# Full.net
KiCad netlist of a schematic drawn in EAGLE
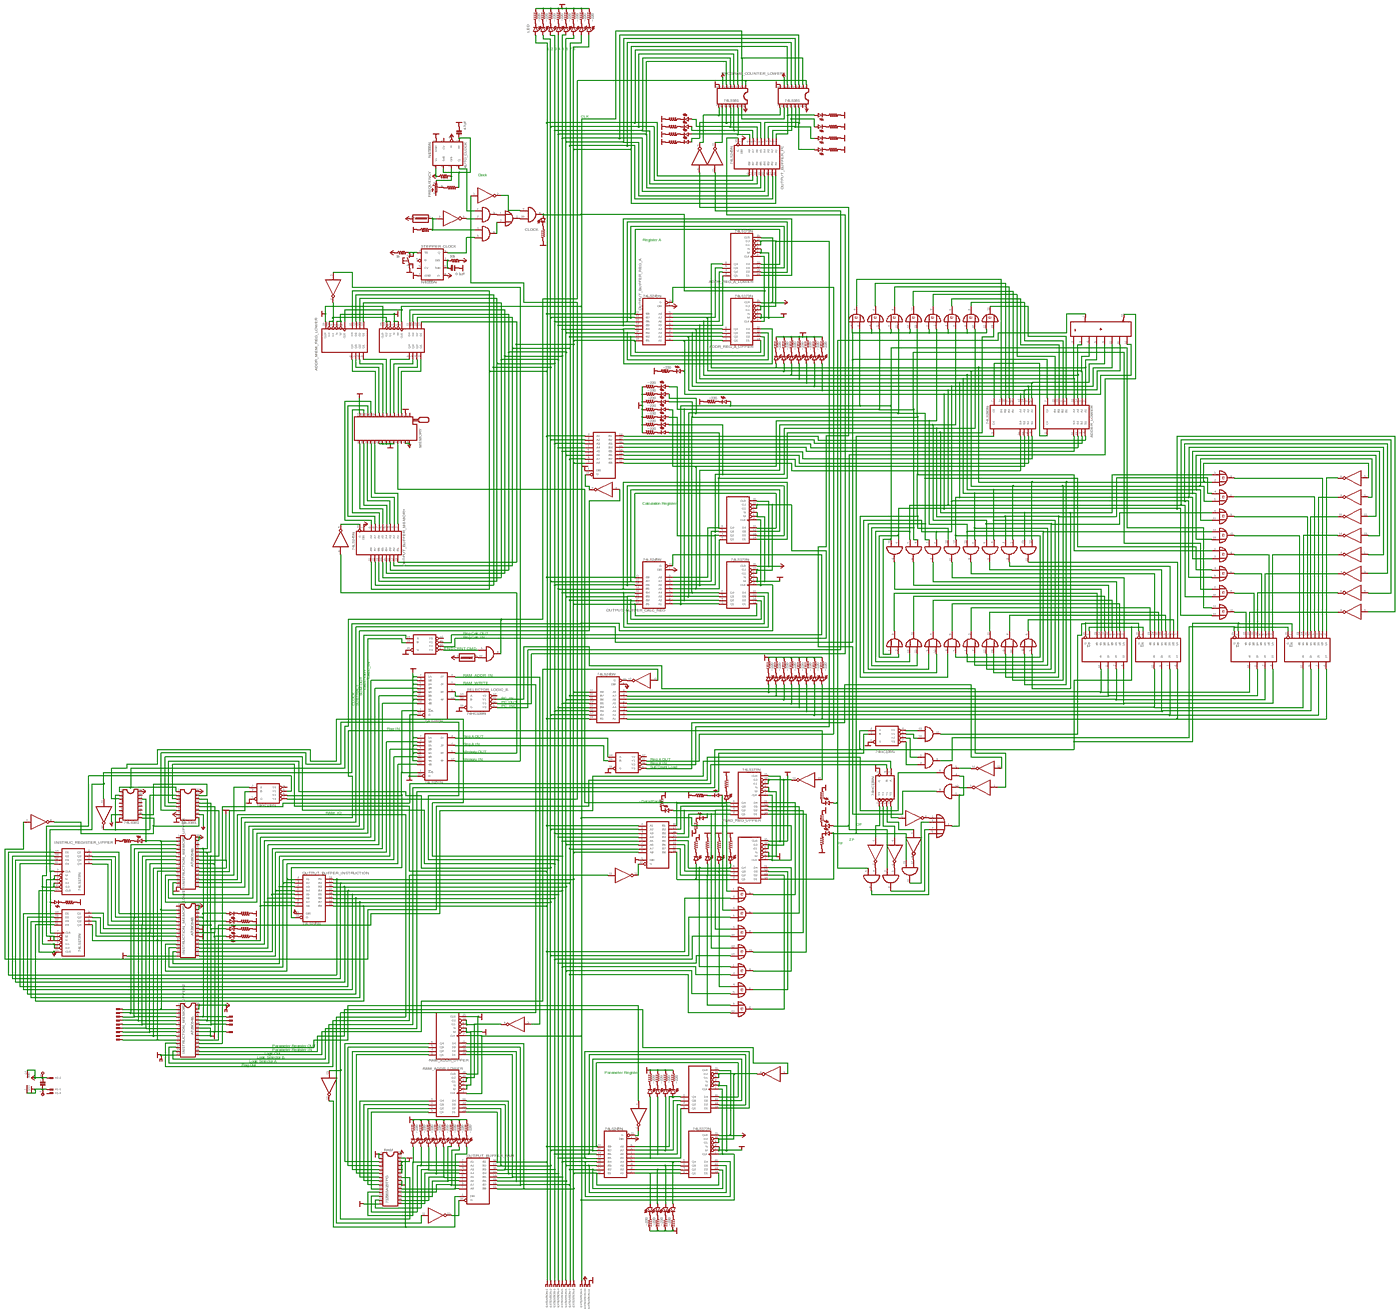
[diagram p0: schematic, sheet 1, overview]
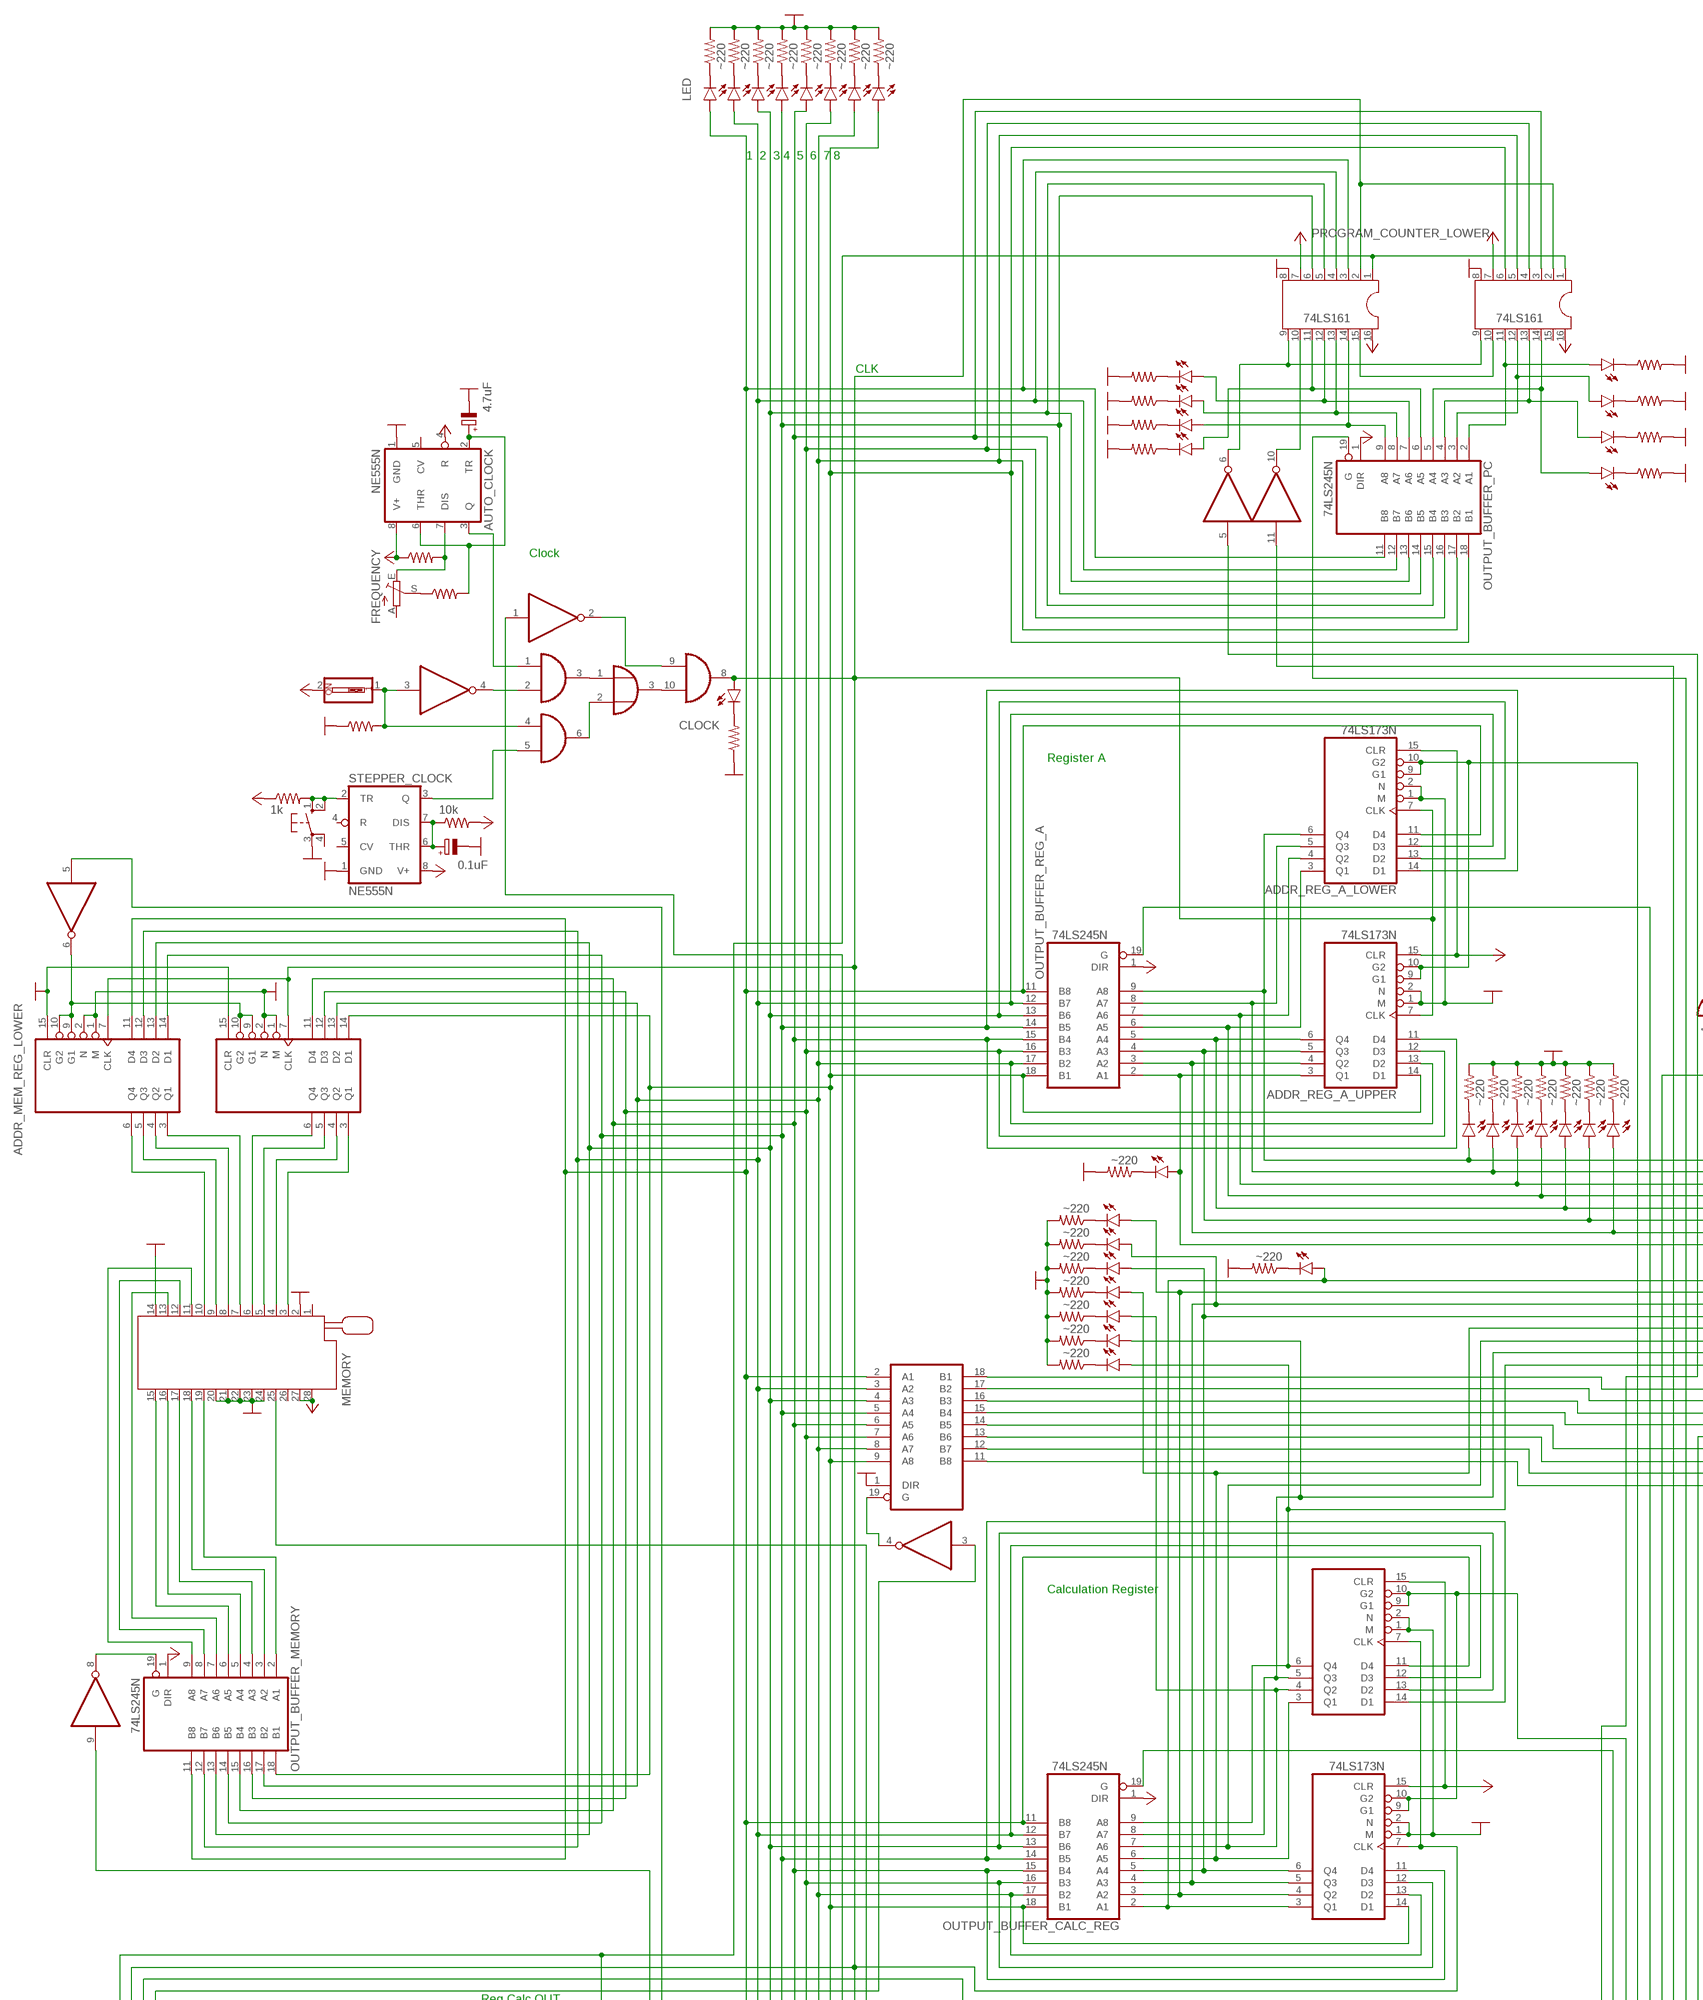
[diagram p1: schematic, sheet 1, part 1 of 4]
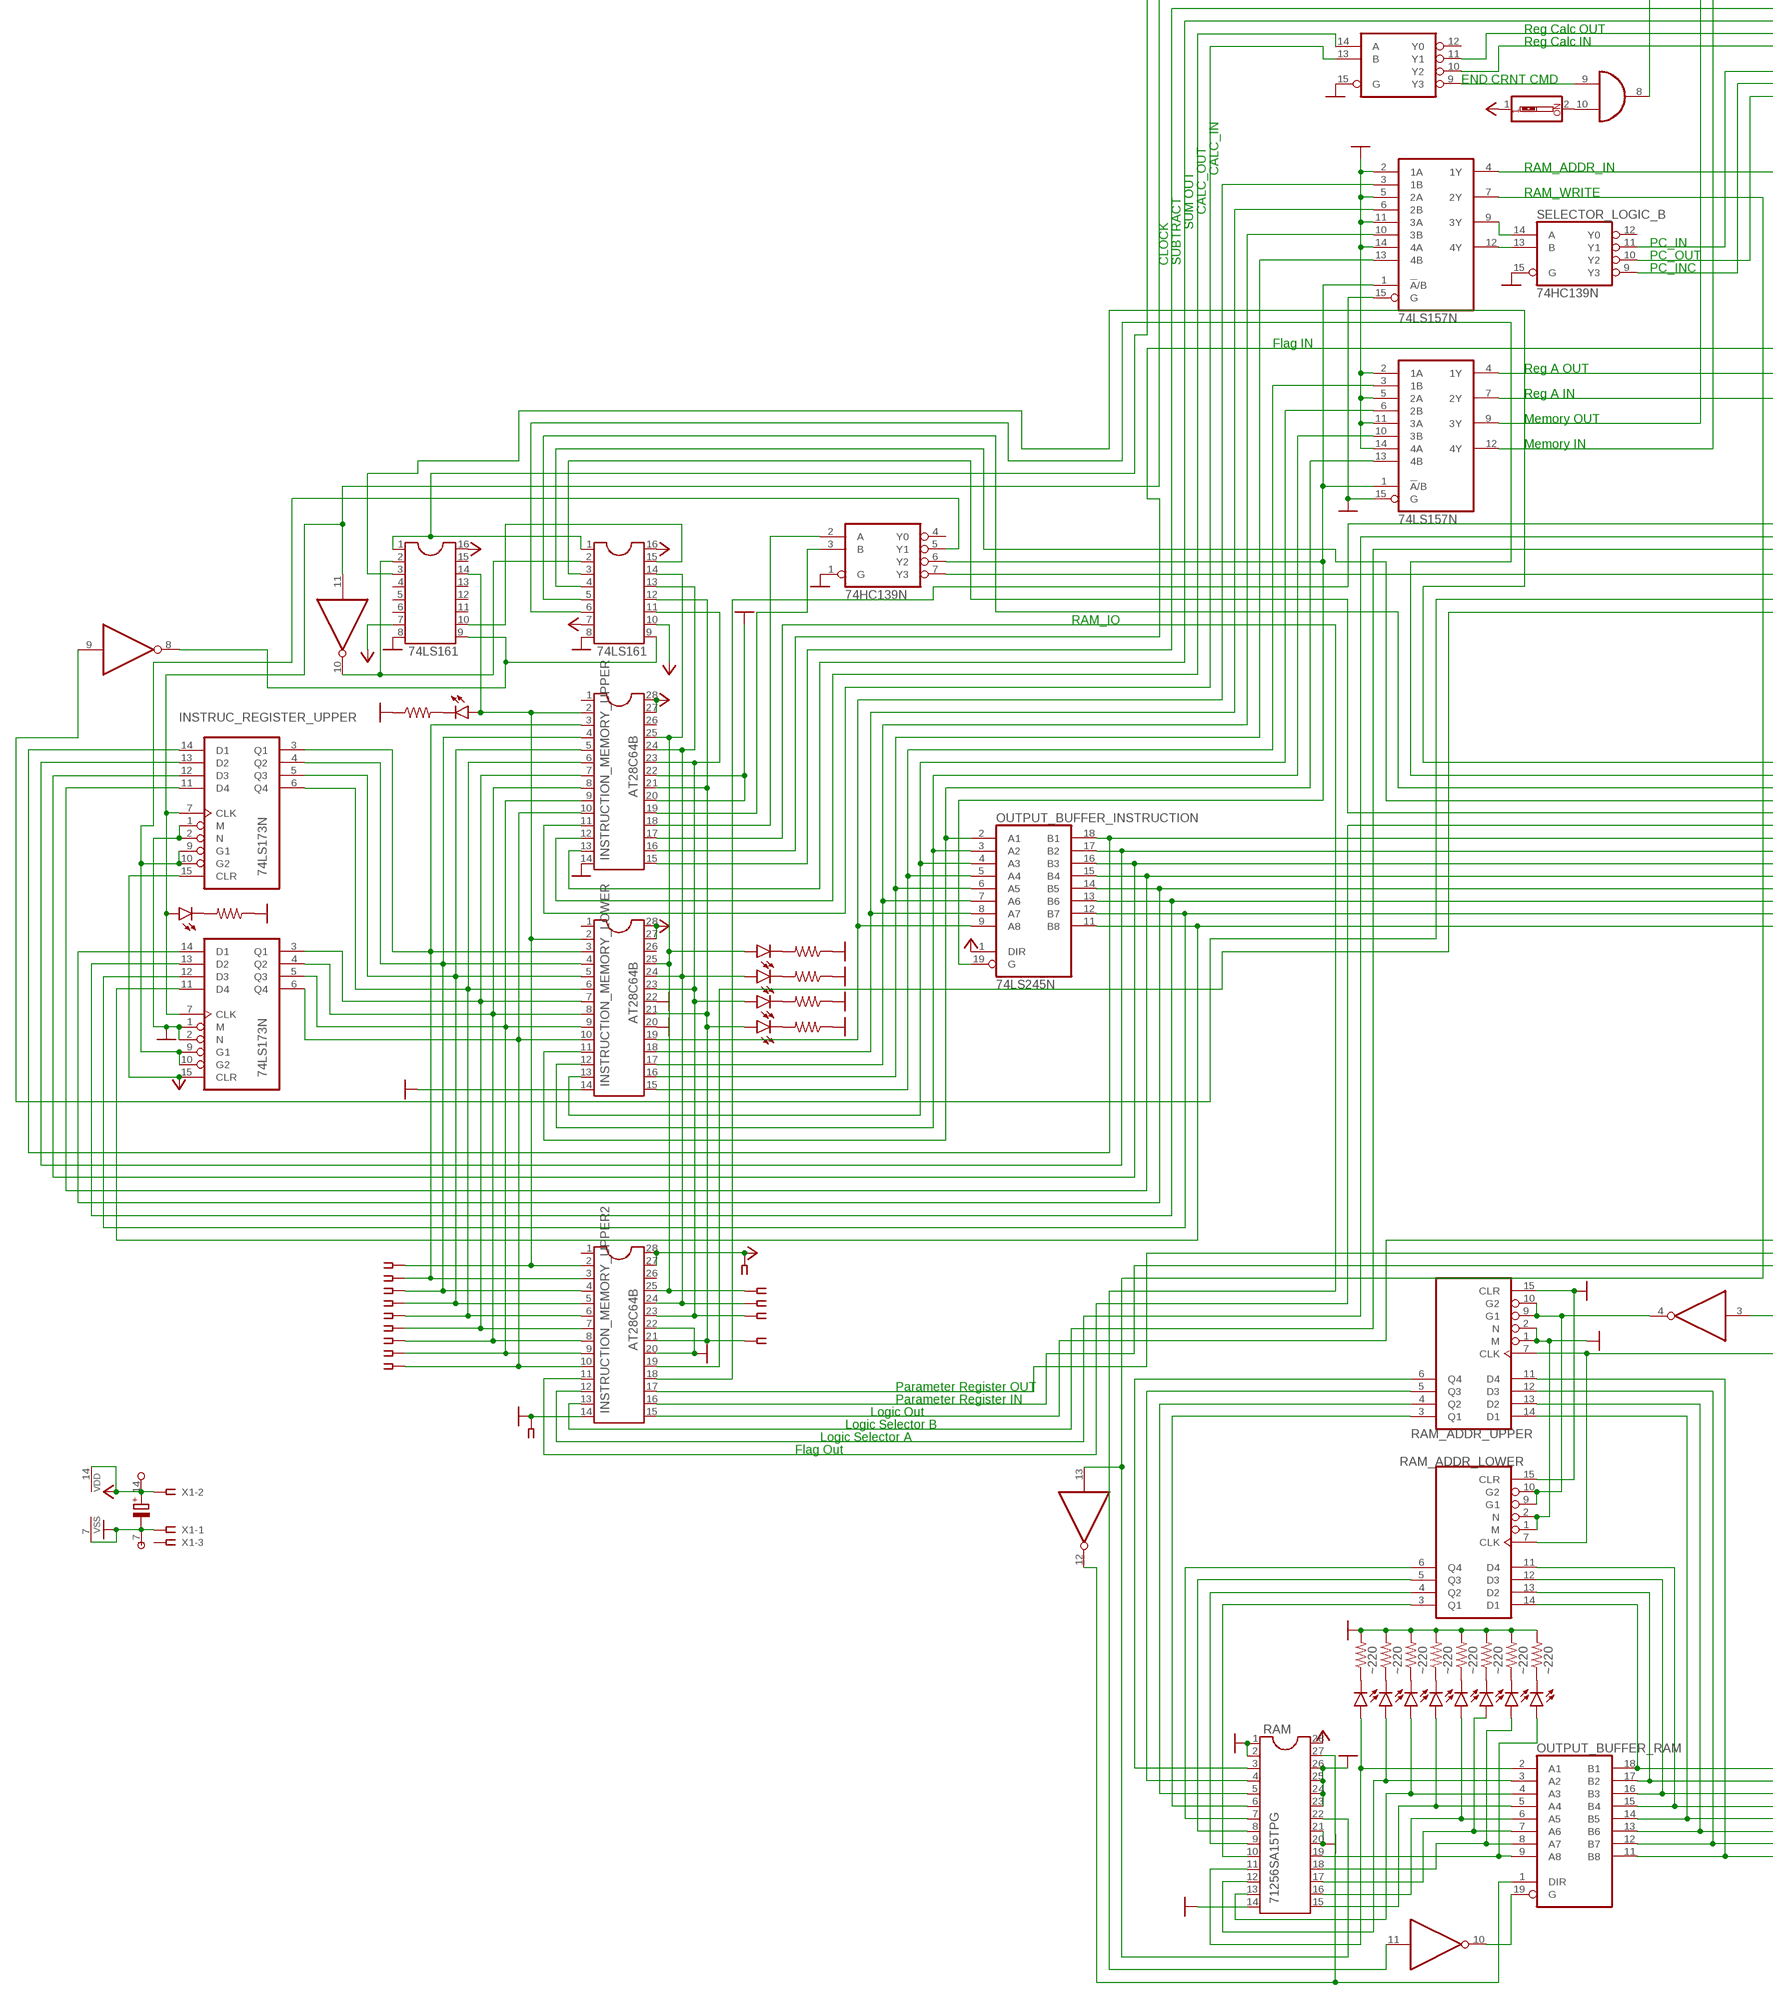
[diagram p2: schematic, sheet 1, part 2 of 4]
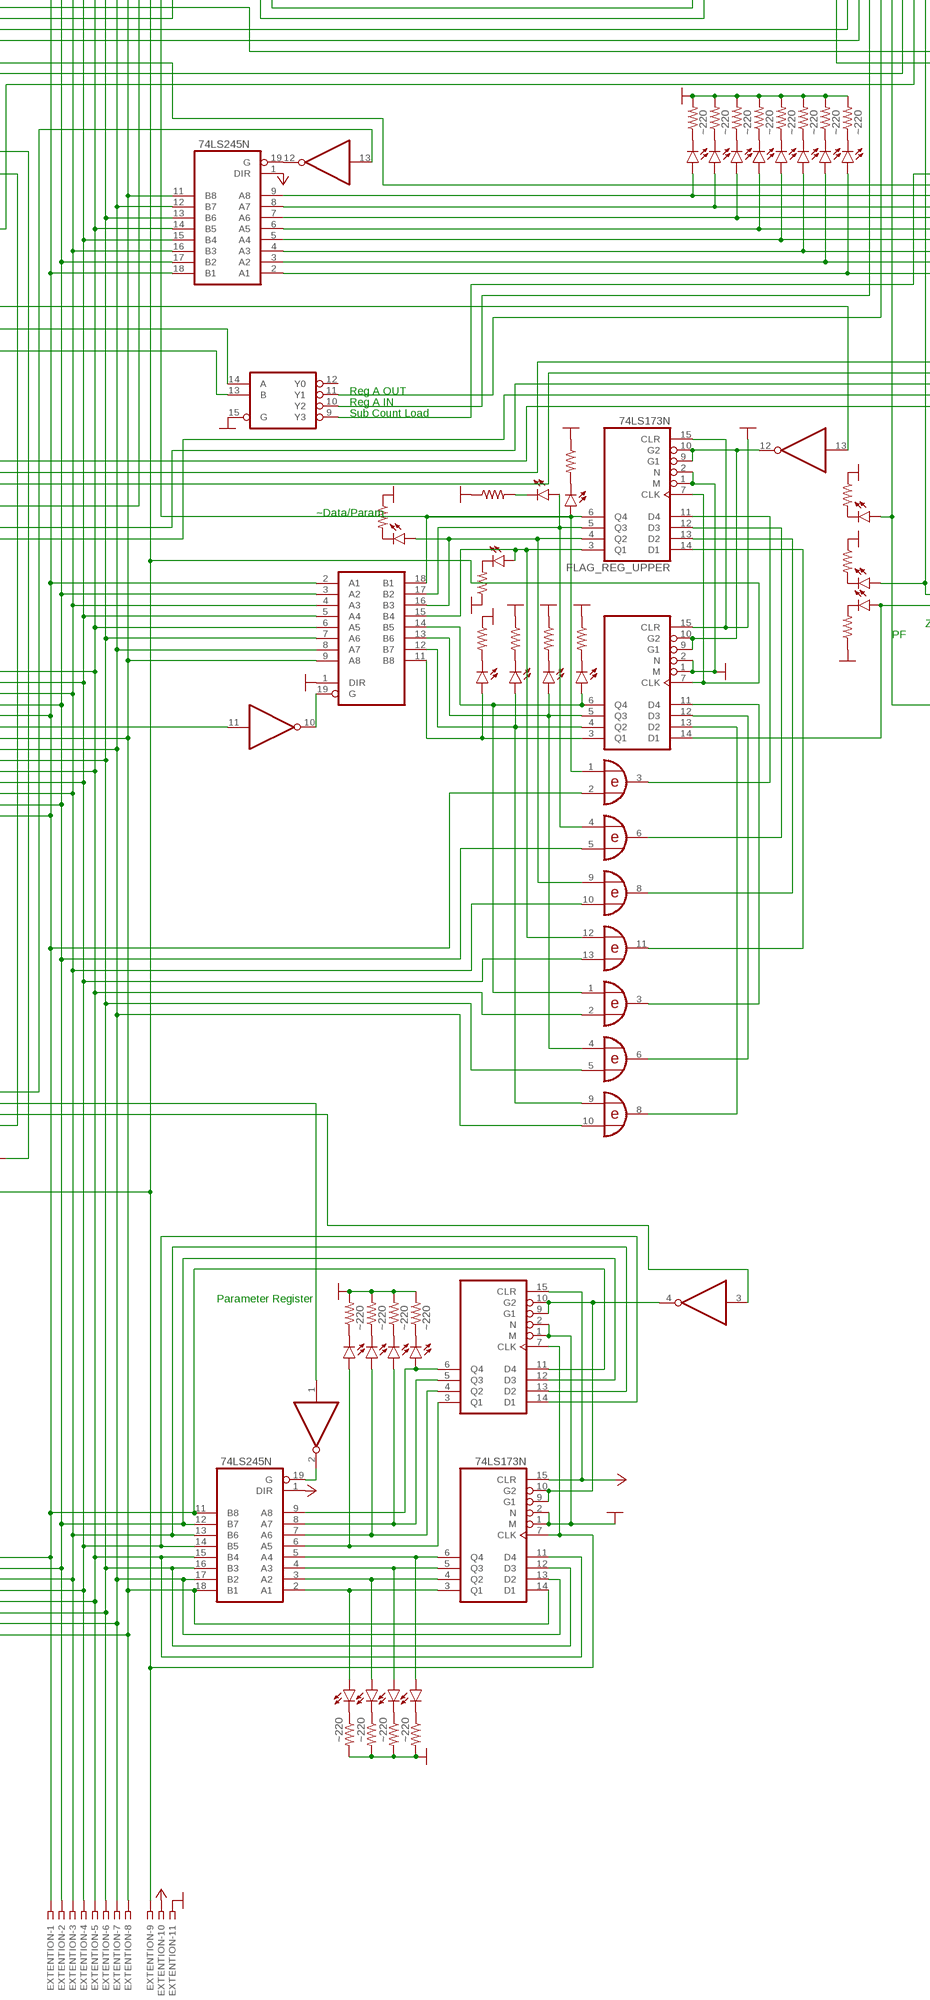
[diagram p3: schematic, sheet 1, part 3 of 4]
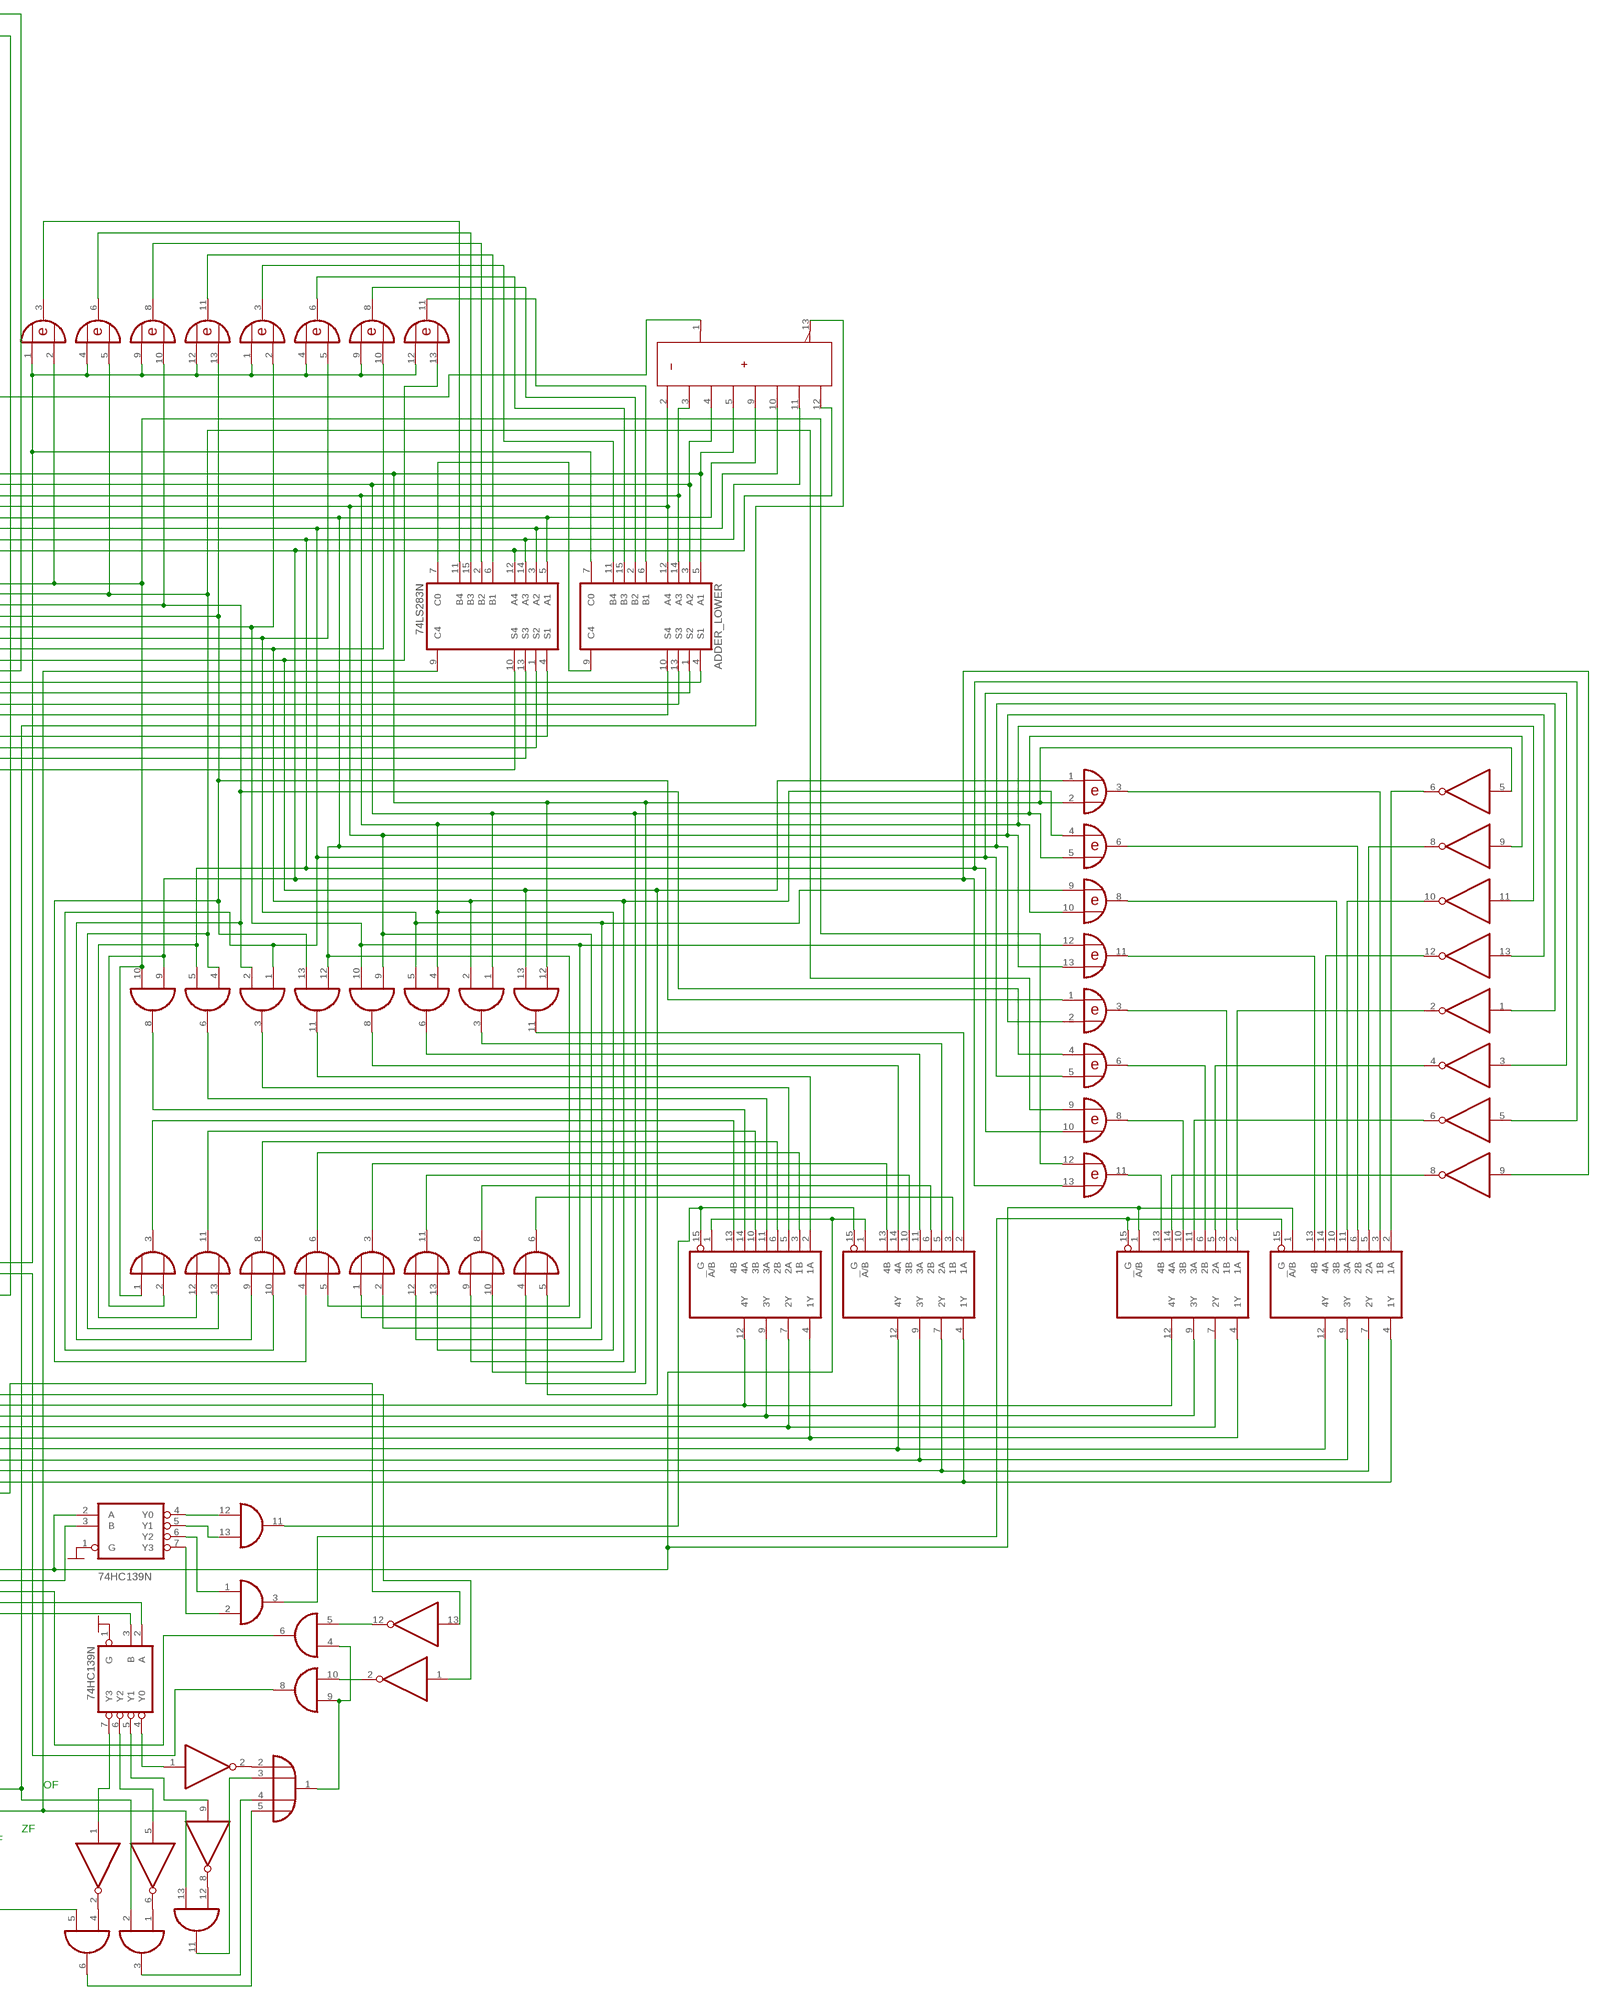
[diagram p4: schematic, sheet 1, part 4 of 4]

(export (version "E")
  (design (tool "Eeschema 10.0.6"))
  (components
    (comp (ref "4_INP_OR_GATE")
      (value "4072N")
      (footprint "eagle-import:DIL14")
      (libsource (lib "eagle-import") (part "4072N"))
    )
    (comp (ref "ADDER_LOWER")
      (value "74LS283N")
      (footprint "eagle-import:DIL16")
      (libsource (lib "eagle-import") (part "74283NLS"))
    )
    (comp (ref "ADDER_UPPER")
      (value "74LS283N")
      (footprint "eagle-import:DIL16")
      (libsource (lib "eagle-import") (part "74283NLS"))
    )
    (comp (ref "ADDR_MEM_REG_LOWER")
      (value "74LS173N")
      (footprint "eagle-import:DIL16")
      (libsource (lib "eagle-import") (part "74173NLS"))
    )
    (comp (ref "ADDR_MEM_REG_UPPER")
      (value "74LS173N")
      (footprint "eagle-import:DIL16")
      (libsource (lib "eagle-import") (part "74173NLS"))
    )
    (comp (ref "ADDR_REG_A_LOWER")
      (value "74LS173N")
      (footprint "eagle-import:DIL16")
      (libsource (lib "eagle-import") (part "74173NLS"))
    )
    (comp (ref "ADDR_REG_A_UPPER")
      (value "74LS173N")
      (footprint "eagle-import:DIL16")
      (libsource (lib "eagle-import") (part "74173NLS"))
    )
    (comp (ref "ADDR_REG_CALC_LOWER")
      (value "74LS173N")
      (footprint "eagle-import:DIL16")
      (libsource (lib "eagle-import") (part "74173NLS"))
    )
    (comp (ref "ADDR_REG_CALC_LOWER1")
      (value "74LS173N")
      (footprint "eagle-import:DIL16")
      (libsource (lib "eagle-import") (part "74173NLS"))
    )
    (comp (ref "ADDR_REG_CALC_UPPER")
      (value "74LS173N")
      (footprint "eagle-import:DIL16")
      (libsource (lib "eagle-import") (part "74173NLS"))
    )
    (comp (ref "ADDR_REG_PARAM_UPPER")
      (value "74LS173N")
      (footprint "eagle-import:DIL16")
      (libsource (lib "eagle-import") (part "74173NLS"))
    )
    (comp (ref "AND_GATE1_")
      (value "74LS08N")
      (footprint "eagle-import:DIL14")
      (libsource (lib "eagle-import") (part "7408NLS"))
    )
    (comp (ref "AND_GATE2_")
      (value "74LS08N")
      (footprint "eagle-import:DIL14")
      (libsource (lib "eagle-import") (part "7408NLS"))
    )
    (comp (ref "AND_GATE3_")
      (value "74LS08N")
      (footprint "eagle-import:DIL14")
      (libsource (lib "eagle-import") (part "7408NLS"))
    )
    (comp (ref "AND_GATE4_")
      (value "74LS08N")
      (footprint "eagle-import:DIL14")
      (libsource (lib "eagle-import") (part "7408NLS"))
    )
    (comp (ref "AND_GATE_")
      (value "74LS08N")
      (footprint "eagle-import:DIL14")
      (libsource (lib "eagle-import") (part "7408NLS"))
    )
    (comp (ref "AUTO_CLOCK")
      (value "NE555N")
      (footprint "eagle-import:DIL08")
      (libsource (lib "eagle-import") (part "555NNE"))
    )
    (comp (ref "BRANCH_SELECTOR")
      (value "74HC139N")
      (footprint "eagle-import:DIL16")
      (libsource (lib "eagle-import") (part "74139NHC"))
    )
    (comp (ref "C1")
      (value "4.7uF")
      (footprint "eagle-import:E2-5")
      (libsource (lib "eagle-import") (part "CPOL-EUE2-5"))
    )
    (comp (ref "C2")
      (value "0.1uF")
      (footprint "eagle-import:E2-5")
      (libsource (lib "eagle-import") (part "CPOL-EUE2-5"))
    )
    (comp (ref "C3")
      (value "0.1uF")
      (footprint "eagle-import:E2-5")
      (libsource (lib "eagle-import") (part "CPOL-EUE2-5"))
    )
    (comp (ref "CLK_MODE")
      (value "SW_DIP-1")
      (footprint "eagle-import:EDG-01")
      (libsource (lib "eagle-import") (part "SW_DIP-1"))
    )
    (comp (ref "CLK_TRIGGER")
      (value "10-XX")
      (footprint "eagle-import:B3F-10XX")
      (fields (field (name "MPN") "B3F-1000"))
      (libsource (lib "eagle-import") (part "10-XX"))
    )
    (comp (ref "CLOCK")
      (value "LED5MM")
      (footprint "eagle-import:LED5MM")
      (libsource (lib "eagle-import") (part "LED5MM"))
    )
    (comp (ref "DATABUS_1")
      (value "LED")
      (footprint "eagle-import:LED5MM")
      (libsource (lib "eagle-import") (part "LED5MM"))
    )
    (comp (ref "DATABUS_2")
      (value "LED5MM")
      (footprint "eagle-import:LED5MM")
      (libsource (lib "eagle-import") (part "LED5MM"))
    )
    (comp (ref "DATABUS_3")
      (value "LED5MM")
      (footprint "eagle-import:LED5MM")
      (libsource (lib "eagle-import") (part "LED5MM"))
    )
    (comp (ref "DATABUS_4")
      (value "LED5MM")
      (footprint "eagle-import:LED5MM")
      (libsource (lib "eagle-import") (part "LED5MM"))
    )
    (comp (ref "DATABUS_5")
      (value "LED5MM")
      (footprint "eagle-import:LED5MM")
      (libsource (lib "eagle-import") (part "LED5MM"))
    )
    (comp (ref "DATABUS_6")
      (value "LED5MM")
      (footprint "eagle-import:LED5MM")
      (libsource (lib "eagle-import") (part "LED5MM"))
    )
    (comp (ref "DATABUS_7")
      (value "LED5MM")
      (footprint "eagle-import:LED5MM")
      (libsource (lib "eagle-import") (part "LED5MM"))
    )
    (comp (ref "DATABUS_8")
      (value "LED5MM")
      (footprint "eagle-import:LED5MM")
      (libsource (lib "eagle-import") (part "LED5MM"))
    )
    (comp (ref "EXTENTION")
      (value "SSW-111-02-G-S")
      (footprint "eagle-import:SSW-111-02-G-S")
      (fields (field (name "MF") "Samtec Inc."))
      (libsource (lib "eagle-import") (part "SSW-111-02-G-S"))
    )
    (comp (ref "FLAG_1")
      (value "LED5MM")
      (footprint "eagle-import:LED5MM")
      (libsource (lib "eagle-import") (part "LED5MM"))
    )
    (comp (ref "FLAG_2")
      (value "LED5MM")
      (footprint "eagle-import:LED5MM")
      (libsource (lib "eagle-import") (part "LED5MM"))
    )
    (comp (ref "FLAG_3")
      (value "LED5MM")
      (footprint "eagle-import:LED5MM")
      (libsource (lib "eagle-import") (part "LED5MM"))
    )
    (comp (ref "FLAG_4")
      (value "LED5MM")
      (footprint "eagle-import:LED5MM")
      (libsource (lib "eagle-import") (part "LED5MM"))
    )
    (comp (ref "FLAG_5")
      (value "LED5MM")
      (footprint "eagle-import:LED5MM")
      (libsource (lib "eagle-import") (part "LED5MM"))
    )
    (comp (ref "FLAG_6")
      (value "LED5MM")
      (footprint "eagle-import:LED5MM")
      (libsource (lib "eagle-import") (part "LED5MM"))
    )
    (comp (ref "FLAG_7")
      (value "LED5MM")
      (footprint "eagle-import:LED5MM")
      (libsource (lib "eagle-import") (part "LED5MM"))
    )
    (comp (ref "FLAG_8")
      (value "LED5MM")
      (footprint "eagle-import:LED5MM")
      (libsource (lib "eagle-import") (part "LED5MM"))
    )
    (comp (ref "FLAG_REG_LOWER")
      (value "74LS173N")
      (footprint "eagle-import:DIL16")
      (libsource (lib "eagle-import") (part "74173NLS"))
    )
    (comp (ref "FLAG_REG_UPPER")
      (value "74LS173N")
      (footprint "eagle-import:DIL16")
      (libsource (lib "eagle-import") (part "74173NLS"))
    )
    (comp (ref "FREQUENCY")
      (value "100k")
      (footprint "eagle-import:RJ9W")
      (libsource (lib "eagle-import") (part "TRIM_EU-RJ9W"))
    )
    (comp (ref "INSRUCTION_REGISTER_SELECTOR_LOWER")
      (value "74LS157N")
      (footprint "eagle-import:DIL16")
      (libsource (lib "eagle-import") (part "74157NLS"))
    )
    (comp (ref "INSRUCTION_REGISTER_SELECTOR_UPPER")
      (value "74LS157N")
      (footprint "eagle-import:DIL16")
      (libsource (lib "eagle-import") (part "74157NLS"))
    )
    (comp (ref "INSTRUCTIONS_EXTENSION")
      (value "SSW-115-02-G-S")
      (footprint "eagle-import:SSW-115-02-G-S")
      (fields (field (name "MF") "Samtec Inc."))
      (libsource (lib "eagle-import") (part "SSW-115-02-G-S"))
    )
    (comp (ref "INSTRUCTION_MEMORY_LOWER")
      (value "AT28C64B")
      (footprint "eagle-import:DIL28-6")
      (libsource (lib "eagle-import") (part "DIL28"))
    )
    (comp (ref "INSTRUCTION_MEMORY_UPPER")
      (value "AT28C64B")
      (footprint "eagle-import:DIL28-6")
      (libsource (lib "eagle-import") (part "DIL28"))
    )
    (comp (ref "INSTRUCTION_MEMORY_UPPER2")
      (value "AT28C64B")
      (footprint "eagle-import:DIL28-6")
      (libsource (lib "eagle-import") (part "DIL28"))
    )
    (comp (ref "INSTRUC_REGISTER_LOWER")
      (value "74LS173N")
      (footprint "eagle-import:DIL16")
      (libsource (lib "eagle-import") (part "74173NLS"))
    )
    (comp (ref "INSTRUC_REGISTER_UPPER")
      (value "74LS173N")
      (footprint "eagle-import:DIL16")
      (libsource (lib "eagle-import") (part "74173NLS"))
    )
    (comp (ref "INVERTED_CLK_LED")
      (value "LED5MM")
      (footprint "eagle-import:LED5MM")
      (libsource (lib "eagle-import") (part "LED5MM"))
    )
    (comp (ref "KILL_SWITCH")
      (value "SW_DIP-1")
      (footprint "eagle-import:EDG-01")
      (libsource (lib "eagle-import") (part "SW_DIP-1"))
    )
    (comp (ref "LED_A_REG_1")
      (value "LED5MM")
      (footprint "eagle-import:LED5MM")
      (libsource (lib "eagle-import") (part "LED5MM"))
    )
    (comp (ref "LED_A_REG_2")
      (value "LED5MM")
      (footprint "eagle-import:LED5MM")
      (libsource (lib "eagle-import") (part "LED5MM"))
    )
    (comp (ref "LED_A_REG_3")
      (value "LED5MM")
      (footprint "eagle-import:LED5MM")
      (libsource (lib "eagle-import") (part "LED5MM"))
    )
    (comp (ref "LED_A_REG_4")
      (value "LED5MM")
      (footprint "eagle-import:LED5MM")
      (libsource (lib "eagle-import") (part "LED5MM"))
    )
    (comp (ref "LED_A_REG_5")
      (value "LED5MM")
      (footprint "eagle-import:LED5MM")
      (libsource (lib "eagle-import") (part "LED5MM"))
    )
    (comp (ref "LED_A_REG_6")
      (value "LED5MM")
      (footprint "eagle-import:LED5MM")
      (libsource (lib "eagle-import") (part "LED5MM"))
    )
    (comp (ref "LED_A_REG_7")
      (value "LED5MM")
      (footprint "eagle-import:LED5MM")
      (libsource (lib "eagle-import") (part "LED5MM"))
    )
    (comp (ref "LED_A_REG_8")
      (value "LED5MM")
      (footprint "eagle-import:LED5MM")
      (libsource (lib "eagle-import") (part "LED5MM"))
    )
    (comp (ref "LED_B_REG_1")
      (value "LED5MM")
      (footprint "eagle-import:LED5MM")
      (libsource (lib "eagle-import") (part "LED5MM"))
    )
    (comp (ref "LED_B_REG_2")
      (value "LED5MM")
      (footprint "eagle-import:LED5MM")
      (libsource (lib "eagle-import") (part "LED5MM"))
    )
    (comp (ref "LED_B_REG_3")
      (value "LED5MM")
      (footprint "eagle-import:LED5MM")
      (libsource (lib "eagle-import") (part "LED5MM"))
    )
    (comp (ref "LED_B_REG_4")
      (value "LED5MM")
      (footprint "eagle-import:LED5MM")
      (libsource (lib "eagle-import") (part "LED5MM"))
    )
    (comp (ref "LED_B_REG_5")
      (value "LED5MM")
      (footprint "eagle-import:LED5MM")
      (libsource (lib "eagle-import") (part "LED5MM"))
    )
    (comp (ref "LED_B_REG_6")
      (value "LED5MM")
      (footprint "eagle-import:LED5MM")
      (libsource (lib "eagle-import") (part "LED5MM"))
    )
    (comp (ref "LED_B_REG_7")
      (value "LED5MM")
      (footprint "eagle-import:LED5MM")
      (libsource (lib "eagle-import") (part "LED5MM"))
    )
    (comp (ref "LED_B_REG_8")
      (value "LED5MM")
      (footprint "eagle-import:LED5MM")
      (libsource (lib "eagle-import") (part "LED5MM"))
    )
    (comp (ref "LOGIC_LED_1")
      (value "LED3MM")
      (footprint "eagle-import:LED3MM")
      (libsource (lib "eagle-import") (part "LED3MM"))
    )
    (comp (ref "LOGIC_LED_2")
      (value "LED3MM")
      (footprint "eagle-import:LED3MM")
      (libsource (lib "eagle-import") (part "LED3MM"))
    )
    (comp (ref "LOGIC_LED_3")
      (value "LED3MM")
      (footprint "eagle-import:LED3MM")
      (libsource (lib "eagle-import") (part "LED3MM"))
    )
    (comp (ref "LOGIC_LED_4")
      (value "LED3MM")
      (footprint "eagle-import:LED3MM")
      (libsource (lib "eagle-import") (part "LED3MM"))
    )
    (comp (ref "LOGIC_LED_5")
      (value "LED3MM")
      (footprint "eagle-import:LED3MM")
      (libsource (lib "eagle-import") (part "LED3MM"))
    )
    (comp (ref "LOGIC_LED_6")
      (value "LED3MM")
      (footprint "eagle-import:LED3MM")
      (libsource (lib "eagle-import") (part "LED3MM"))
    )
    (comp (ref "LOGIC_LED_7")
      (value "LED3MM")
      (footprint "eagle-import:LED3MM")
      (libsource (lib "eagle-import") (part "LED3MM"))
    )
    (comp (ref "LOGIC_LED_8")
      (value "LED3MM")
      (footprint "eagle-import:LED3MM")
      (libsource (lib "eagle-import") (part "LED3MM"))
    )
    (comp (ref "LOGIC_SELECTOR-AND/OR_LOWER")
      (value "74LS157N")
      (footprint "eagle-import:DIL16")
      (libsource (lib "eagle-import") (part "74157NLS"))
    )
    (comp (ref "LOGIC_SELECTOR-AND/OR_UPPER")
      (value "74LS157N")
      (footprint "eagle-import:DIL16")
      (libsource (lib "eagle-import") (part "74157NLS"))
    )
    (comp (ref "LOGIC_SELECTOR-XOR/NOT_LOWER")
      (value "74LS157N")
      (footprint "eagle-import:DIL16")
      (libsource (lib "eagle-import") (part "74157NLS"))
    )
    (comp (ref "LOGIC_SELECTOR-XOR/NOT_UPPER")
      (value "74LS157N")
      (footprint "eagle-import:DIL16")
      (libsource (lib "eagle-import") (part "74157NLS"))
    )
    (comp (ref "MEMORY")
      (value "228-1277-00-0602J")
      (footprint "eagle-import:228-1277-00-0602J")
      (fields (field (name "MF") "3M"))
      (libsource (lib "eagle-import") (part "228-?00-0602J1277-"))
    )
    (comp (ref "MICRO_COUNTER_LOWER")
      (value "74LS161")
      (footprint "eagle-import:DIL16")
      (libsource (lib "eagle-import") (part "DIL16"))
    )
    (comp (ref "MICRO_COUNTER_UPPER")
      (value "74LS161")
      (footprint "eagle-import:DIL16")
      (libsource (lib "eagle-import") (part "DIL16"))
    )
    (comp (ref "NOT_GATE1")
      (value "74LS04N")
      (footprint "eagle-import:DIL14")
      (libsource (lib "eagle-import") (part "7404NLS"))
    )
    (comp (ref "NOT_GATE2_")
      (value "74LS04N")
      (footprint "eagle-import:DIL14")
      (libsource (lib "eagle-import") (part "7404NLS"))
    )
    (comp (ref "NOT_GATE3_")
      (value "74LS04N")
      (footprint "eagle-import:DIL14")
      (libsource (lib "eagle-import") (part "7404NLS"))
    )
    (comp (ref "NOT_GATE4_")
      (value "74LS04N")
      (footprint "eagle-import:DIL14")
      (fields (field (name "SPICEPREFIX") "B"))
      (libsource (lib "eagle-import") (part "7404NLS"))
    )
    (comp (ref "NOT_GATE5_")
      (value "74LS04N")
      (footprint "eagle-import:DIL14")
      (libsource (lib "eagle-import") (part "7404NLS"))
    )
    (comp (ref "NOT_GATE_")
      (value "74LS04N")
      (footprint "eagle-import:DIL14")
      (libsource (lib "eagle-import") (part "7404NLS"))
    )
    (comp (ref "OR_GATE")
      (value "74LS32N")
      (footprint "eagle-import:DIL14")
      (libsource (lib "eagle-import") (part "7432NLS"))
    )
    (comp (ref "OR_GATE1")
      (value "74LS32N")
      (footprint "eagle-import:DIL14")
      (libsource (lib "eagle-import") (part "7432NLS"))
    )
    (comp (ref "OR_GATE_2")
      (value "74LS32N")
      (footprint "eagle-import:DIL14")
      (libsource (lib "eagle-import") (part "7432NLS"))
    )
    (comp (ref "OUTPUT_BUFFER_ALU")
      (value "74LS245N")
      (footprint "eagle-import:DIL20")
      (libsource (lib "eagle-import") (part "74245NLS"))
    )
    (comp (ref "OUTPUT_BUFFER_CALC_REG")
      (value "74LS245N")
      (footprint "eagle-import:DIL20")
      (libsource (lib "eagle-import") (part "74245NLS"))
    )
    (comp (ref "OUTPUT_BUFFER_FLAGS")
      (value "74HC245N")
      (footprint "eagle-import:DIL20")
      (libsource (lib "eagle-import") (part "74245NHC"))
    )
    (comp (ref "OUTPUT_BUFFER_INSTRUCTION")
      (value "74LS245N")
      (footprint "eagle-import:DIL20")
      (libsource (lib "eagle-import") (part "74xx-us_88_74245NLS"))
    )
    (comp (ref "OUTPUT_BUFFER_LOGIC")
      (value "74LS245N")
      (footprint "eagle-import:DIL20")
      (libsource (lib "eagle-import") (part "74245NLS"))
    )
    (comp (ref "OUTPUT_BUFFER_MEMORY")
      (value "74LS245N")
      (footprint "eagle-import:DIL20")
      (libsource (lib "eagle-import") (part "74245NLS"))
    )
    (comp (ref "OUTPUT_BUFFER_PARAM_REG")
      (value "74LS245N")
      (footprint "eagle-import:DIL20")
      (libsource (lib "eagle-import") (part "74245NLS"))
    )
    (comp (ref "OUTPUT_BUFFER_PC")
      (value "74LS245N")
      (footprint "eagle-import:DIL20")
      (libsource (lib "eagle-import") (part "74245NLS"))
    )
    (comp (ref "OUTPUT_BUFFER_RAM")
      (value "74HC245N")
      (footprint "eagle-import:DIL20")
      (libsource (lib "eagle-import") (part "74245NHC"))
    )
    (comp (ref "OUTPUT_BUFFER_REG_A")
      (value "74LS245N")
      (footprint "eagle-import:DIL20")
      (libsource (lib "eagle-import") (part "74245NLS"))
    )
    (comp (ref "OVERFLOW_FLAG")
      (value "LED5MM")
      (footprint "eagle-import:LED5MM")
      (libsource (lib "eagle-import") (part "LED5MM"))
    )
    (comp (ref "PARAM_LED_1")
      (value "LED3MM")
      (footprint "eagle-import:LED3MM")
      (libsource (lib "eagle-import") (part "LED3MM"))
    )
    (comp (ref "PARAM_LED_2")
      (value "LED3MM")
      (footprint "eagle-import:LED3MM")
      (libsource (lib "eagle-import") (part "LED3MM"))
    )
    (comp (ref "PARAM_LED_3")
      (value "LED3MM")
      (footprint "eagle-import:LED3MM")
      (libsource (lib "eagle-import") (part "LED3MM"))
    )
    (comp (ref "PARAM_LED_4")
      (value "LED3MM")
      (footprint "eagle-import:LED3MM")
      (libsource (lib "eagle-import") (part "LED3MM"))
    )
    (comp (ref "PARAM_LED_5")
      (value "LED3MM")
      (footprint "eagle-import:LED3MM")
      (libsource (lib "eagle-import") (part "LED3MM"))
    )
    (comp (ref "PARAM_LED_6")
      (value "LED3MM")
      (footprint "eagle-import:LED3MM")
      (libsource (lib "eagle-import") (part "LED3MM"))
    )
    (comp (ref "PARAM_LED_7")
      (value "LED3MM")
      (footprint "eagle-import:LED3MM")
      (libsource (lib "eagle-import") (part "LED3MM"))
    )
    (comp (ref "PARAM_LED_8")
      (value "LED3MM")
      (footprint "eagle-import:LED3MM")
      (libsource (lib "eagle-import") (part "LED3MM"))
    )
    (comp (ref "PC_1")
      (value "LED5MM")
      (footprint "eagle-import:LED5MM")
      (libsource (lib "eagle-import") (part "LED5MM"))
    )
    (comp (ref "PC_2")
      (value "LED5MM")
      (footprint "eagle-import:LED5MM")
      (libsource (lib "eagle-import") (part "LED5MM"))
    )
    (comp (ref "PC_3")
      (value "LED5MM")
      (footprint "eagle-import:LED5MM")
      (libsource (lib "eagle-import") (part "LED5MM"))
    )
    (comp (ref "PC_4")
      (value "LED5MM")
      (footprint "eagle-import:LED5MM")
      (libsource (lib "eagle-import") (part "LED5MM"))
    )
    (comp (ref "PC_5")
      (value "LED5MM")
      (footprint "eagle-import:LED5MM")
      (libsource (lib "eagle-import") (part "LED5MM"))
    )
    (comp (ref "PC_6")
      (value "LED5MM")
      (footprint "eagle-import:LED5MM")
      (libsource (lib "eagle-import") (part "LED5MM"))
    )
    (comp (ref "PC_7")
      (value "LED5MM")
      (footprint "eagle-import:LED5MM")
      (libsource (lib "eagle-import") (part "LED5MM"))
    )
    (comp (ref "PC_8")
      (value "LED5MM")
      (footprint "eagle-import:LED5MM")
      (libsource (lib "eagle-import") (part "LED5MM"))
    )
    (comp (ref "POSITIVE_FLAG")
      (value "LED5MM")
      (footprint "eagle-import:LED5MM")
      (libsource (lib "eagle-import") (part "LED5MM"))
    )
    (comp (ref "PROGRAM_COUNTER_LOWER")
      (value "74LS161")
      (footprint "eagle-import:DIL16")
      (libsource (lib "eagle-import") (part "DIL16"))
    )
    (comp (ref "PROGRAM_COUNTER_UPPER")
      (value "74LS161")
      (footprint "eagle-import:DIL16")
      (libsource (lib "eagle-import") (part "DIL16"))
    )
    (comp (ref "R1")
      (value "1k")
      (footprint "eagle-import:0204_7")
      (libsource (lib "eagle-import") (part "R-US_0204/7"))
    )
    (comp (ref "R2")
      (value "1k")
      (footprint "eagle-import:0204_7")
      (libsource (lib "eagle-import") (part "R-US_0204/7"))
    )
    (comp (ref "R3")
      (value "10k")
      (footprint "eagle-import:0204_7")
      (libsource (lib "eagle-import") (part "R-US_0204/7"))
    )
    (comp (ref "R4")
      (value "220")
      (footprint "eagle-import:0204_7")
      (libsource (lib "eagle-import") (part "R-US_0204/7"))
    )
    (comp (ref "R5")
      (value "~220")
      (footprint "eagle-import:0204_7")
      (libsource (lib "eagle-import") (part "R-US_0204/7"))
    )
    (comp (ref "R6")
      (value "~220")
      (footprint "eagle-import:0204_7")
      (libsource (lib "eagle-import") (part "R-US_0204/7"))
    )
    (comp (ref "R7")
      (value "220")
      (footprint "eagle-import:0204_7")
      (libsource (lib "eagle-import") (part "R-US_0204/7"))
    )
    (comp (ref "R8")
      (value "~220")
      (footprint "eagle-import:0204_7")
      (libsource (lib "eagle-import") (part "R-US_0204/7"))
    )
    (comp (ref "R9")
      (value "~220")
      (footprint "eagle-import:0204_7")
      (libsource (lib "eagle-import") (part "R-US_0204/7"))
    )
    (comp (ref "R10")
      (value "~220")
      (footprint "eagle-import:0204_7")
      (libsource (lib "eagle-import") (part "R-US_0204/7"))
    )
    (comp (ref "R11")
      (value "~220")
      (footprint "eagle-import:0204_7")
      (libsource (lib "eagle-import") (part "R-US_0204/7"))
    )
    (comp (ref "R12")
      (value "~220")
      (footprint "eagle-import:0204_7")
      (libsource (lib "eagle-import") (part "R-US_0204/7"))
    )
    (comp (ref "R13")
      (value "~220")
      (footprint "eagle-import:0204_7")
      (libsource (lib "eagle-import") (part "R-US_0204/7"))
    )
    (comp (ref "R14")
      (value "~220")
      (footprint "eagle-import:0204_7")
      (libsource (lib "eagle-import") (part "R-US_0204/7"))
    )
    (comp (ref "R15")
      (value "~220")
      (footprint "eagle-import:0204_7")
      (libsource (lib "eagle-import") (part "R-US_0204/7"))
    )
    (comp (ref "R16")
      (value "~220")
      (footprint "eagle-import:0204_7")
      (libsource (lib "eagle-import") (part "R-US_0204/7"))
    )
    (comp (ref "R17")
      (value "~220")
      (footprint "eagle-import:0204_7")
      (libsource (lib "eagle-import") (part "R-US_0204/7"))
    )
    (comp (ref "R18")
      (value "~220")
      (footprint "eagle-import:0204_7")
      (libsource (lib "eagle-import") (part "R-US_0204/7"))
    )
    (comp (ref "R19")
      (value "~220")
      (footprint "eagle-import:0204_7")
      (libsource (lib "eagle-import") (part "R-US_0204/7"))
    )
    (comp (ref "R20")
      (value "~220")
      (footprint "eagle-import:0204_7")
      (libsource (lib "eagle-import") (part "R-US_0204/7"))
    )
    (comp (ref "R21")
      (value "~220")
      (footprint "eagle-import:0204_7")
      (libsource (lib "eagle-import") (part "R-US_0204/7"))
    )
    (comp (ref "R22")
      (value "~220")
      (footprint "eagle-import:0204_7")
      (libsource (lib "eagle-import") (part "R-US_0204/7"))
    )
    (comp (ref "R23")
      (value "~220")
      (footprint "eagle-import:0204_7")
      (libsource (lib "eagle-import") (part "R-US_0204/7"))
    )
    (comp (ref "R24")
      (value "~220")
      (footprint "eagle-import:0204_7")
      (libsource (lib "eagle-import") (part "R-US_0204/7"))
    )
    (comp (ref "R25")
      (value "~220")
      (footprint "eagle-import:0204_7")
      (libsource (lib "eagle-import") (part "R-US_0204/7"))
    )
    (comp (ref "R26")
      (value "~220")
      (footprint "eagle-import:0204_7")
      (libsource (lib "eagle-import") (part "R-US_0204/7"))
    )
    (comp (ref "R27")
      (value "~220")
      (footprint "eagle-import:0204_7")
      (libsource (lib "eagle-import") (part "R-US_0204/7"))
    )
    (comp (ref "R28")
      (value "~220")
      (footprint "eagle-import:0204_7")
      (libsource (lib "eagle-import") (part "R-US_0204/7"))
    )
    (comp (ref "R29")
      (value "~220")
      (footprint "eagle-import:0204_7")
      (libsource (lib "eagle-import") (part "R-US_0204/7"))
    )
    (comp (ref "R30")
      (value "~220")
      (footprint "eagle-import:0204_7")
      (libsource (lib "eagle-import") (part "R-US_0204/7"))
    )
    (comp (ref "R31")
      (value "~220")
      (footprint "eagle-import:0204_7")
      (libsource (lib "eagle-import") (part "R-US_0204/7"))
    )
    (comp (ref "R32")
      (value "~220")
      (footprint "eagle-import:0204_7")
      (libsource (lib "eagle-import") (part "R-US_0204/7"))
    )
    (comp (ref "R33")
      (value "~220")
      (footprint "eagle-import:0204_7")
      (libsource (lib "eagle-import") (part "R-US_0204/7"))
    )
    (comp (ref "R34")
      (value "~220")
      (footprint "eagle-import:0204_7")
      (libsource (lib "eagle-import") (part "R-US_0204/7"))
    )
    (comp (ref "R35")
      (value "~220")
      (footprint "eagle-import:0204_7")
      (libsource (lib "eagle-import") (part "R-US_0204/7"))
    )
    (comp (ref "R36")
      (value "~220")
      (footprint "eagle-import:0204_7")
      (libsource (lib "eagle-import") (part "R-US_0204/7"))
    )
    (comp (ref "R37")
      (value "~220")
      (footprint "eagle-import:0204_7")
      (libsource (lib "eagle-import") (part "R-US_0204/7"))
    )
    (comp (ref "R38")
      (value "~220")
      (footprint "eagle-import:0204_7")
      (libsource (lib "eagle-import") (part "R-US_0204/7"))
    )
    (comp (ref "R39")
      (value "~220")
      (footprint "eagle-import:0204_7")
      (libsource (lib "eagle-import") (part "R-US_0204/7"))
    )
    (comp (ref "R40")
      (value "~220")
      (footprint "eagle-import:0204_7")
      (libsource (lib "eagle-import") (part "R-US_0204/7"))
    )
    (comp (ref "R41")
      (value "~220")
      (footprint "eagle-import:0204_7")
      (libsource (lib "eagle-import") (part "R-US_0204/7"))
    )
    (comp (ref "R42")
      (value "~220")
      (footprint "eagle-import:0204_7")
      (libsource (lib "eagle-import") (part "R-US_0204/7"))
    )
    (comp (ref "R43")
      (value "~220")
      (footprint "eagle-import:0204_7")
      (libsource (lib "eagle-import") (part "R-US_0204/7"))
    )
    (comp (ref "R44")
      (value "~220")
      (footprint "eagle-import:0204_7")
      (libsource (lib "eagle-import") (part "R-US_0204/7"))
    )
    (comp (ref "R45")
      (value "~220")
      (footprint "eagle-import:0204_7")
      (libsource (lib "eagle-import") (part "R-US_0204/7"))
    )
    (comp (ref "R46")
      (value "~220")
      (footprint "eagle-import:0204_7")
      (libsource (lib "eagle-import") (part "R-US_0204/7"))
    )
    (comp (ref "R47")
      (value "~220")
      (footprint "eagle-import:0204_7")
      (libsource (lib "eagle-import") (part "R-US_0204/7"))
    )
    (comp (ref "R48")
      (value "~220")
      (footprint "eagle-import:0204_7")
      (libsource (lib "eagle-import") (part "R-US_0204/7"))
    )
    (comp (ref "R49")
      (value "~220")
      (footprint "eagle-import:0204_7")
      (libsource (lib "eagle-import") (part "R-US_0204/7"))
    )
    (comp (ref "R50")
      (value "~220")
      (footprint "eagle-import:0204_7")
      (libsource (lib "eagle-import") (part "R-US_0204/7"))
    )
    (comp (ref "R51")
      (value "~220")
      (footprint "eagle-import:0204_7")
      (libsource (lib "eagle-import") (part "R-US_0204/7"))
    )
    (comp (ref "R52")
      (value "~220")
      (footprint "eagle-import:0204_7")
      (libsource (lib "eagle-import") (part "R-US_0204/7"))
    )
    (comp (ref "R53")
      (value "~220")
      (footprint "eagle-import:0204_7")
      (libsource (lib "eagle-import") (part "R-US_0204/7"))
    )
    (comp (ref "R54")
      (value "~220")
      (footprint "eagle-import:0204_7")
      (libsource (lib "eagle-import") (part "R-US_0204/7"))
    )
    (comp (ref "R55")
      (value "~220")
      (footprint "eagle-import:0204_7")
      (libsource (lib "eagle-import") (part "R-US_0204/7"))
    )
    (comp (ref "R56")
      (value "~220")
      (footprint "eagle-import:0204_7")
      (libsource (lib "eagle-import") (part "R-US_0204/7"))
    )
    (comp (ref "R57")
      (value "~220")
      (footprint "eagle-import:0204_7")
      (libsource (lib "eagle-import") (part "R-US_0204/7"))
    )
    (comp (ref "R58")
      (value "~220")
      (footprint "eagle-import:0204_7")
      (libsource (lib "eagle-import") (part "R-US_0204/7"))
    )
    (comp (ref "R59")
      (value "~220")
      (footprint "eagle-import:0204_7")
      (libsource (lib "eagle-import") (part "R-US_0204/7"))
    )
    (comp (ref "R60")
      (value "~220")
      (footprint "eagle-import:0204_7")
      (libsource (lib "eagle-import") (part "R-US_0204/7"))
    )
    (comp (ref "R61")
      (value "~220")
      (footprint "eagle-import:0204_7")
      (libsource (lib "eagle-import") (part "R-US_0204/7"))
    )
    (comp (ref "R62")
      (value "~220")
      (footprint "eagle-import:0204_7")
      (libsource (lib "eagle-import") (part "R-US_0204/7"))
    )
    (comp (ref "R63")
      (value "~220")
      (footprint "eagle-import:0204_7")
      (libsource (lib "eagle-import") (part "R-US_0204/7"))
    )
    (comp (ref "R64")
      (value "~220")
      (footprint "eagle-import:0204_7")
      (libsource (lib "eagle-import") (part "R-US_0204/7"))
    )
    (comp (ref "R65")
      (value "~220")
      (footprint "eagle-import:0204_7")
      (libsource (lib "eagle-import") (part "R-US_0204/7"))
    )
    (comp (ref "R66")
      (value "~220")
      (footprint "eagle-import:0204_7")
      (libsource (lib "eagle-import") (part "R-US_0204/7"))
    )
    (comp (ref "R67")
      (value "~220")
      (footprint "eagle-import:0204_7")
      (libsource (lib "eagle-import") (part "R-US_0204/7"))
    )
    (comp (ref "R68")
      (value "~220")
      (footprint "eagle-import:0204_7")
      (libsource (lib "eagle-import") (part "R-US_0204/7"))
    )
    (comp (ref "R69")
      (value "~220")
      (footprint "eagle-import:0204_7")
      (libsource (lib "eagle-import") (part "R-US_0204/7"))
    )
    (comp (ref "R70")
      (value "~220")
      (footprint "eagle-import:0204_7")
      (libsource (lib "eagle-import") (part "R-US_0204/7"))
    )
    (comp (ref "R71")
      (value "~220")
      (footprint "eagle-import:0204_7")
      (libsource (lib "eagle-import") (part "R-US_0204/7"))
    )
    (comp (ref "R72")
      (value "~220")
      (footprint "eagle-import:0204_7")
      (libsource (lib "eagle-import") (part "R-US_0204/7"))
    )
    (comp (ref "R73")
      (value "~220")
      (footprint "eagle-import:0204_7")
      (libsource (lib "eagle-import") (part "R-US_0204/7"))
    )
    (comp (ref "R74")
      (value "~220")
      (footprint "eagle-import:0204_7")
      (libsource (lib "eagle-import") (part "R-US_0204/7"))
    )
    (comp (ref "R75")
      (value "~220")
      (footprint "eagle-import:0204_7")
      (libsource (lib "eagle-import") (part "R-US_0204/7"))
    )
    (comp (ref "R76")
      (value "~220")
      (footprint "eagle-import:0204_7")
      (libsource (lib "eagle-import") (part "R-US_0204/7"))
    )
    (comp (ref "R77")
      (value "~220")
      (footprint "eagle-import:0204_7")
      (libsource (lib "eagle-import") (part "R-US_0204/7"))
    )
    (comp (ref "R78")
      (value "~220")
      (footprint "eagle-import:0204_7")
      (libsource (lib "eagle-import") (part "R-US_0204/7"))
    )
    (comp (ref "R79")
      (value "~220")
      (footprint "eagle-import:0204_7")
      (libsource (lib "eagle-import") (part "R-US_0204/7"))
    )
    (comp (ref "RAM")
      (value "71256SA15TPG")
      (footprint "eagle-import:DIL28-4")
      (libsource (lib "eagle-import") (part "DIL28-4"))
    )
    (comp (ref "RAM_ADDR_LOWER")
      (value "74LS173N")
      (footprint "eagle-import:DIL16")
      (libsource (lib "eagle-import") (part "74173NLS"))
    )
    (comp (ref "RAM_ADDR_UPPER")
      (value "74LS173N")
      (footprint "eagle-import:DIL16")
      (libsource (lib "eagle-import") (part "74173NLS"))
    )
    (comp (ref "RAM_LED_1")
      (value "LED3MM")
      (footprint "eagle-import:LED3MM")
      (libsource (lib "eagle-import") (part "LED3MM"))
    )
    (comp (ref "RAM_LED_2")
      (value "LED3MM")
      (footprint "eagle-import:LED3MM")
      (libsource (lib "eagle-import") (part "LED3MM"))
    )
    (comp (ref "RAM_LED_3")
      (value "LED3MM")
      (footprint "eagle-import:LED3MM")
      (libsource (lib "eagle-import") (part "LED3MM"))
    )
    (comp (ref "RAM_LED_4")
      (value "LED3MM")
      (footprint "eagle-import:LED3MM")
      (libsource (lib "eagle-import") (part "LED3MM"))
    )
    (comp (ref "RAM_LED_5")
      (value "LED3MM")
      (footprint "eagle-import:LED3MM")
      (libsource (lib "eagle-import") (part "LED3MM"))
    )
    (comp (ref "RAM_LED_6")
      (value "LED3MM")
      (footprint "eagle-import:LED3MM")
      (libsource (lib "eagle-import") (part "LED3MM"))
    )
    (comp (ref "RAM_LED_7")
      (value "LED3MM")
      (footprint "eagle-import:LED3MM")
      (libsource (lib "eagle-import") (part "LED3MM"))
    )
    (comp (ref "RAM_LED_8")
      (value "LED3MM")
      (footprint "eagle-import:LED3MM")
      (libsource (lib "eagle-import") (part "LED3MM"))
    )
    (comp (ref "SELECTOR_LOGIC2_")
      (value "74HC139N")
      (footprint "eagle-import:DIL16")
      (libsource (lib "eagle-import") (part "74139NHC"))
    )
    (comp (ref "SELECTOR_LOGIC_")
      (value "74HC139N")
      (footprint "eagle-import:DIL16")
      (libsource (lib "eagle-import") (part "74139NHC"))
    )
    (comp (ref "STEPPER_CLOCK")
      (value "NE555N")
      (footprint "eagle-import:DIL08")
      (libsource (lib "eagle-import") (part "555NNE"))
    )
    (comp (ref "SUBTRACT_INVRTR_LOWER_")
      (value "74LS86N")
      (footprint "eagle-import:DIL14")
      (libsource (lib "eagle-import") (part "7486NLS"))
    )
    (comp (ref "SUBTRACT_INVRTR_LOWER_1")
      (value "74LS86N")
      (footprint "eagle-import:DIL14")
      (libsource (lib "eagle-import") (part "7486NLS"))
    )
    (comp (ref "SUBTRACT_INVRTR_UPPER_")
      (value "74LS86N")
      (footprint "eagle-import:DIL14")
      (libsource (lib "eagle-import") (part "7486NLS"))
    )
    (comp (ref "SUBTRACT_INVRTR_UPPER_1")
      (value "74LS86N")
      (footprint "eagle-import:DIL14")
      (libsource (lib "eagle-import") (part "7486NLS"))
    )
    (comp (ref "USTEP_1")
      (value "LED5MM")
      (footprint "eagle-import:LED5MM")
      (libsource (lib "eagle-import") (part "LED5MM"))
    )
    (comp (ref "USTEP_2")
      (value "LED5MM")
      (footprint "eagle-import:LED5MM")
      (libsource (lib "eagle-import") (part "LED5MM"))
    )
    (comp (ref "USTEP_3")
      (value "LED5MM")
      (footprint "eagle-import:LED5MM")
      (libsource (lib "eagle-import") (part "LED5MM"))
    )
    (comp (ref "USTEP_4")
      (value "LED5MM")
      (footprint "eagle-import:LED5MM")
      (libsource (lib "eagle-import") (part "LED5MM"))
    )
    (comp (ref "USTEP_5")
      (value "LED5MM")
      (footprint "eagle-import:LED5MM")
      (libsource (lib "eagle-import") (part "LED5MM"))
    )
    (comp (ref "X1")
      (value "SSW-103-02-G-S")
      (footprint "eagle-import:SSW-103-02-G-S")
      (fields (field (name "MF") "Samtec Inc."))
      (libsource (lib "eagle-import") (part "SSW-103-02-G-S"))
    )
    (comp (ref "XOR_GATE_1")
      (value "74LS86N")
      (footprint "eagle-import:DIL14")
      (libsource (lib "eagle-import") (part "7486NLS"))
    )
    (comp (ref "XOR_GATE_2")
      (value "74LS86N")
      (footprint "eagle-import:DIL14")
      (libsource (lib "eagle-import") (part "7486NLS"))
    )
    (comp (ref "ZERO_FLAG")
      (value "LED5MM")
      (footprint "eagle-import:LED5MM")
      (libsource (lib "eagle-import") (part "LED5MM"))
    )
    (comp (ref "ZERO_POS_FLAG_IDENTIFIER")
      (value "744078N")
      (footprint "eagle-import:DIL14")
      (libsource (lib "eagle-import") (part "744078N"))
    )
  )
  (nets
    (net (code "1") (name "GND") (class "Default")
      (node (ref "4_INP_OR_GATE") (pin "7") (pinfunction "VSS_7") (pintype "power_in"))
      (node (ref "ADDR_MEM_REG_LOWER") (pin "1") (pinfunction "M_1") (pintype "input"))
      (node (ref "ADDR_MEM_REG_LOWER") (pin "15") (pinfunction "CLR_15") (pintype "input"))
      (node (ref "ADDR_MEM_REG_LOWER") (pin "2") (pinfunction "N_2") (pintype "input"))
      (node (ref "ADDR_MEM_REG_UPPER") (pin "1") (pinfunction "M_1") (pintype "input"))
      (node (ref "ADDR_MEM_REG_UPPER") (pin "15") (pinfunction "CLR_15") (pintype "input"))
      (node (ref "ADDR_MEM_REG_UPPER") (pin "2") (pinfunction "N_2") (pintype "input"))
      (node (ref "ADDR_REG_A_LOWER") (pin "1") (pinfunction "M_1") (pintype "input"))
      (node (ref "ADDR_REG_A_LOWER") (pin "2") (pinfunction "N_2") (pintype "input"))
      (node (ref "ADDR_REG_A_UPPER") (pin "1") (pinfunction "M_1") (pintype "input"))
      (node (ref "ADDR_REG_A_UPPER") (pin "2") (pinfunction "N_2") (pintype "input"))
      (node (ref "ADDR_REG_CALC_LOWER") (pin "1") (pinfunction "M_1") (pintype "input"))
      (node (ref "ADDR_REG_CALC_LOWER") (pin "2") (pinfunction "N_2") (pintype "input"))
      (node (ref "ADDR_REG_CALC_LOWER1") (pin "1") (pinfunction "M_1") (pintype "input"))
      (node (ref "ADDR_REG_CALC_LOWER1") (pin "2") (pinfunction "N_2") (pintype "input"))
      (node (ref "ADDR_REG_CALC_UPPER") (pin "1") (pinfunction "M_1") (pintype "input"))
      (node (ref "ADDR_REG_CALC_UPPER") (pin "2") (pinfunction "N_2") (pintype "input"))
      (node (ref "ADDR_REG_PARAM_UPPER") (pin "1") (pinfunction "M_1") (pintype "input"))
      (node (ref "ADDR_REG_PARAM_UPPER") (pin "2") (pinfunction "N_2") (pintype "input"))
      (node (ref "AUTO_CLOCK") (pin "1") (pinfunction "GND_1") (pintype "power_in"))
      (node (ref "BRANCH_SELECTOR") (pin "1") (pinfunction "G_1") (pintype "input"))
      (node (ref "BRANCH_SELECTOR") (pin "15") (pinfunction "G_15") (pintype "input"))
      (node (ref "C1") (pin "-") (pinfunction "-_-") (pintype "passive"))
      (node (ref "C2") (pin "-") (pinfunction "-_-") (pintype "passive"))
      (node (ref "C3") (pin "-") (pinfunction "-_-") (pintype "passive"))
      (node (ref "CLK_TRIGGER") (pin "3") (pinfunction "P_3") (pintype "passive"))
      (node (ref "EXTENTION") (pin "11") (pinfunction "1_11") (pintype "passive"))
      (node (ref "FLAG_REG_LOWER") (pin "1") (pinfunction "M_1") (pintype "input"))
      (node (ref "FLAG_REG_LOWER") (pin "15") (pinfunction "CLR_15") (pintype "input"))
      (node (ref "FLAG_REG_LOWER") (pin "2") (pinfunction "N_2") (pintype "input"))
      (node (ref "FLAG_REG_UPPER") (pin "1") (pinfunction "M_1") (pintype "input"))
      (node (ref "FLAG_REG_UPPER") (pin "15") (pinfunction "CLR_15") (pintype "input"))
      (node (ref "FLAG_REG_UPPER") (pin "2") (pinfunction "N_2") (pintype "input"))
      (node (ref "INSRUCTION_REGISTER_SELECTOR_LOWER") (pin "11") (pinfunction "3A_11") (pintype "input"))
      (node (ref "INSRUCTION_REGISTER_SELECTOR_LOWER") (pin "14") (pinfunction "4A_14") (pintype "input"))
      (node (ref "INSRUCTION_REGISTER_SELECTOR_LOWER") (pin "15") (pinfunction "G_15") (pintype "input"))
      (node (ref "INSRUCTION_REGISTER_SELECTOR_LOWER") (pin "2") (pinfunction "1A_2") (pintype "input"))
      (node (ref "INSRUCTION_REGISTER_SELECTOR_LOWER") (pin "5") (pinfunction "2A_5") (pintype "input"))
      (node (ref "INSRUCTION_REGISTER_SELECTOR_UPPER") (pin "11") (pinfunction "3A_11") (pintype "input"))
      (node (ref "INSRUCTION_REGISTER_SELECTOR_UPPER") (pin "14") (pinfunction "4A_14") (pintype "input"))
      (node (ref "INSRUCTION_REGISTER_SELECTOR_UPPER") (pin "15") (pinfunction "G_15") (pintype "input"))
      (node (ref "INSRUCTION_REGISTER_SELECTOR_UPPER") (pin "2") (pinfunction "1A_2") (pintype "input"))
      (node (ref "INSRUCTION_REGISTER_SELECTOR_UPPER") (pin "5") (pinfunction "2A_5") (pintype "input"))
      (node (ref "INSTRUCTIONS_EXTENSION") (pin "15") (pinfunction "1_15") (pintype "passive"))
      (node (ref "INSTRUCTION_MEMORY_LOWER") (pin "14") (pinfunction "14_14") (pintype "passive"))
      (node (ref "INSTRUCTION_MEMORY_LOWER") (pin "20") (pinfunction "20_20") (pintype "passive"))
      (node (ref "INSTRUCTION_MEMORY_LOWER") (pin "22") (pinfunction "22_22") (pintype "passive"))
      (node (ref "INSTRUCTION_MEMORY_UPPER") (pin "14") (pinfunction "14_14") (pintype "passive"))
      (node (ref "INSTRUCTION_MEMORY_UPPER") (pin "20") (pinfunction "20_20") (pintype "passive"))
      (node (ref "INSTRUCTION_MEMORY_UPPER") (pin "22") (pinfunction "22_22") (pintype "passive"))
      (node (ref "INSTRUCTION_MEMORY_UPPER2") (pin "14") (pinfunction "14_14") (pintype "passive"))
      (node (ref "INSTRUCTION_MEMORY_UPPER2") (pin "20") (pinfunction "20_20") (pintype "passive"))
      (node (ref "INSTRUCTION_MEMORY_UPPER2") (pin "22") (pinfunction "22_22") (pintype "passive"))
      (node (ref "INSTRUC_REGISTER_LOWER") (pin "1") (pinfunction "M_1") (pintype "input"))
      (node (ref "INSTRUC_REGISTER_LOWER") (pin "2") (pinfunction "N_2") (pintype "input"))
      (node (ref "INSTRUC_REGISTER_UPPER") (pin "1") (pinfunction "M_1") (pintype "input"))
      (node (ref "INSTRUC_REGISTER_UPPER") (pin "2") (pinfunction "N_2") (pintype "input"))
      (node (ref "MEMORY") (pin "14") (pinfunction "14_14") (pintype "passive"))
      (node (ref "MEMORY") (pin "2") (pinfunction "2_2") (pintype "passive"))
      (node (ref "MEMORY") (pin "20") (pinfunction "20_20") (pintype "passive"))
      (node (ref "MEMORY") (pin "21") (pinfunction "21_21") (pintype "passive"))
      (node (ref "MEMORY") (pin "22") (pinfunction "22_22") (pintype "passive"))
      (node (ref "MEMORY") (pin "23") (pinfunction "23_23") (pintype "passive"))
      (node (ref "MEMORY") (pin "24") (pinfunction "24_24") (pintype "passive"))
      (node (ref "MICRO_COUNTER_LOWER") (pin "8") (pinfunction "8_8") (pintype "passive"))
      (node (ref "MICRO_COUNTER_UPPER") (pin "8") (pinfunction "8_8") (pintype "passive"))
      (node (ref "OUTPUT_BUFFER_ALU") (pin "1") (pinfunction "DIR_1") (pintype "input"))
      (node (ref "OUTPUT_BUFFER_FLAGS") (pin "1") (pinfunction "DIR_1") (pintype "input"))
      (node (ref "PROGRAM_COUNTER_LOWER") (pin "8") (pinfunction "8_8") (pintype "passive"))
      (node (ref "PROGRAM_COUNTER_UPPER") (pin "8") (pinfunction "8_8") (pintype "passive"))
      (node (ref "R10") (pin "1") (pinfunction "1_1") (pintype "passive"))
      (node (ref "R11") (pin "1") (pinfunction "1_1") (pintype "passive"))
      (node (ref "R12") (pin "1") (pinfunction "1_1") (pintype "passive"))
      (node (ref "R13") (pin "1") (pinfunction "1_1") (pintype "passive"))
      (node (ref "R14") (pin "1") (pinfunction "1_1") (pintype "passive"))
      (node (ref "R15") (pin "1") (pinfunction "1_1") (pintype "passive"))
      (node (ref "R16") (pin "2") (pinfunction "2_2") (pintype "passive"))
      (node (ref "R17") (pin "2") (pinfunction "2_2") (pintype "passive"))
      (node (ref "R18") (pin "2") (pinfunction "2_2") (pintype "passive"))
      (node (ref "R19") (pin "2") (pinfunction "2_2") (pintype "passive"))
      (node (ref "R20") (pin "2") (pinfunction "2_2") (pintype "passive"))
      (node (ref "R21") (pin "2") (pinfunction "2_2") (pintype "passive"))
      (node (ref "R22") (pin "2") (pinfunction "2_2") (pintype "passive"))
      (node (ref "R23") (pin "2") (pinfunction "2_2") (pintype "passive"))
      (node (ref "R24") (pin "2") (pinfunction "2_2") (pintype "passive"))
      (node (ref "R25") (pin "2") (pinfunction "2_2") (pintype "passive"))
      (node (ref "R26") (pin "2") (pinfunction "2_2") (pintype "passive"))
      (node (ref "R27") (pin "2") (pinfunction "2_2") (pintype "passive"))
      (node (ref "R28") (pin "2") (pinfunction "2_2") (pintype "passive"))
      (node (ref "R29") (pin "2") (pinfunction "2_2") (pintype "passive"))
      (node (ref "R30") (pin "2") (pinfunction "2_2") (pintype "passive"))
      (node (ref "R31") (pin "2") (pinfunction "2_2") (pintype "passive"))
      (node (ref "R32") (pin "2") (pinfunction "2_2") (pintype "passive"))
      (node (ref "R33") (pin "2") (pinfunction "2_2") (pintype "passive"))
      (node (ref "R34") (pin "2") (pinfunction "2_2") (pintype "passive"))
      (node (ref "R35") (pin "2") (pinfunction "2_2") (pintype "passive"))
      (node (ref "R36") (pin "2") (pinfunction "2_2") (pintype "passive"))
      (node (ref "R37") (pin "2") (pinfunction "2_2") (pintype "passive"))
      (node (ref "R38") (pin "2") (pinfunction "2_2") (pintype "passive"))
      (node (ref "R39") (pin "2") (pinfunction "2_2") (pintype "passive"))
      (node (ref "R4") (pin "1") (pinfunction "1_1") (pintype "passive"))
      (node (ref "R40") (pin "1") (pinfunction "1_1") (pintype "passive"))
      (node (ref "R41") (pin "1") (pinfunction "1_1") (pintype "passive"))
      (node (ref "R42") (pin "1") (pinfunction "1_1") (pintype "passive"))
      (node (ref "R43") (pin "1") (pinfunction "1_1") (pintype "passive"))
      (node (ref "R44") (pin "1") (pinfunction "1_1") (pintype "passive"))
      (node (ref "R45") (pin "1") (pinfunction "1_1") (pintype "passive"))
      (node (ref "R46") (pin "2") (pinfunction "2_2") (pintype "passive"))
      (node (ref "R47") (pin "2") (pinfunction "2_2") (pintype "passive"))
      (node (ref "R48") (pin "2") (pinfunction "2_2") (pintype "passive"))
      (node (ref "R49") (pin "2") (pinfunction "2_2") (pintype "passive"))
      (node (ref "R5") (pin "1") (pinfunction "1_1") (pintype "passive"))
      (node (ref "R50") (pin "2") (pinfunction "2_2") (pintype "passive"))
      (node (ref "R51") (pin "2") (pinfunction "2_2") (pintype "passive"))
      (node (ref "R52") (pin "2") (pinfunction "2_2") (pintype "passive"))
      (node (ref "R53") (pin "2") (pinfunction "2_2") (pintype "passive"))
      (node (ref "R54") (pin "2") (pinfunction "2_2") (pintype "passive"))
      (node (ref "R55") (pin "2") (pinfunction "2_2") (pintype "passive"))
      (node (ref "R56") (pin "2") (pinfunction "2_2") (pintype "passive"))
      (node (ref "R57") (pin "2") (pinfunction "2_2") (pintype "passive"))
      (node (ref "R58") (pin "2") (pinfunction "2_2") (pintype "passive"))
      (node (ref "R59") (pin "2") (pinfunction "2_2") (pintype "passive"))
      (node (ref "R6") (pin "2") (pinfunction "2_2") (pintype "passive"))
      (node (ref "R60") (pin "2") (pinfunction "2_2") (pintype "passive"))
      (node (ref "R61") (pin "2") (pinfunction "2_2") (pintype "passive"))
      (node (ref "R62") (pin "2") (pinfunction "2_2") (pintype "passive"))
      (node (ref "R63") (pin "2") (pinfunction "2_2") (pintype "passive"))
      (node (ref "R64") (pin "2") (pinfunction "2_2") (pintype "passive"))
      (node (ref "R65") (pin "2") (pinfunction "2_2") (pintype "passive"))
      (node (ref "R66") (pin "2") (pinfunction "2_2") (pintype "passive"))
      (node (ref "R67") (pin "2") (pinfunction "2_2") (pintype "passive"))
      (node (ref "R68") (pin "2") (pinfunction "2_2") (pintype "passive"))
      (node (ref "R69") (pin "2") (pinfunction "2_2") (pintype "passive"))
      (node (ref "R70") (pin "2") (pinfunction "2_2") (pintype "passive"))
      (node (ref "R71") (pin "2") (pinfunction "2_2") (pintype "passive"))
      (node (ref "R72") (pin "2") (pinfunction "2_2") (pintype "passive"))
      (node (ref "R73") (pin "2") (pinfunction "2_2") (pintype "passive"))
      (node (ref "R74") (pin "2") (pinfunction "2_2") (pintype "passive"))
      (node (ref "R75") (pin "2") (pinfunction "2_2") (pintype "passive"))
      (node (ref "R76") (pin "2") (pinfunction "2_2") (pintype "passive"))
      (node (ref "R77") (pin "1") (pinfunction "1_1") (pintype "passive"))
      (node (ref "R78") (pin "1") (pinfunction "1_1") (pintype "passive"))
      (node (ref "R79") (pin "1") (pinfunction "1_1") (pintype "passive"))
      (node (ref "R8") (pin "1") (pinfunction "1_1") (pintype "passive"))
      (node (ref "R9") (pin "1") (pinfunction "1_1") (pintype "passive"))
      (node (ref "RAM") (pin "1") (pinfunction "1_1") (pintype "passive"))
      (node (ref "RAM") (pin "14") (pinfunction "14_14") (pintype "passive"))
      (node (ref "RAM") (pin "2") (pinfunction "2_2") (pintype "passive"))
      (node (ref "RAM") (pin "20") (pinfunction "20_20") (pintype "passive"))
      (node (ref "RAM") (pin "21") (pinfunction "21_21") (pintype "passive"))
      (node (ref "RAM") (pin "23") (pinfunction "23_23") (pintype "passive"))
      (node (ref "RAM") (pin "24") (pinfunction "24_24") (pintype "passive"))
      (node (ref "RAM") (pin "25") (pinfunction "25_25") (pintype "passive"))
      (node (ref "RAM") (pin "26") (pinfunction "26_26") (pintype "passive"))
      (node (ref "RAM_ADDR_LOWER") (pin "1") (pinfunction "M_1") (pintype "input"))
      (node (ref "RAM_ADDR_LOWER") (pin "15") (pinfunction "CLR_15") (pintype "input"))
      (node (ref "RAM_ADDR_LOWER") (pin "2") (pinfunction "N_2") (pintype "input"))
      (node (ref "RAM_ADDR_UPPER") (pin "1") (pinfunction "M_1") (pintype "input"))
      (node (ref "RAM_ADDR_UPPER") (pin "15") (pinfunction "CLR_15") (pintype "input"))
      (node (ref "RAM_ADDR_UPPER") (pin "2") (pinfunction "N_2") (pintype "input"))
      (node (ref "SELECTOR_LOGIC2_") (pin "1") (pinfunction "G_1") (pintype "input"))
      (node (ref "SELECTOR_LOGIC2_") (pin "15") (pinfunction "G_15") (pintype "input"))
      (node (ref "SELECTOR_LOGIC_") (pin "1") (pinfunction "G_1") (pintype "input"))
      (node (ref "SELECTOR_LOGIC_") (pin "15") (pinfunction "G_15") (pintype "input"))
      (node (ref "STEPPER_CLOCK") (pin "1") (pinfunction "GND_1") (pintype "power_in"))
      (node (ref "X1") (pin "1") (pinfunction "1_1") (pintype "passive"))
      (node (ref "ZERO_POS_FLAG_IDENTIFIER") (pin "7") (pinfunction "-UB_7") (pintype "power_in"))
    )
    (net (code "2") (name "Net-(4_INP_OR_GATEA-I0)") (class "Default")
      (node (ref "4_INP_OR_GATE") (pin "2") (pinfunction "I0_2") (pintype "input"))
      (node (ref "NOT_GATE4_") (pin "2") (pinfunction "O_2") (pintype "output"))
    )
    (net (code "3") (name "Net-(4_INP_OR_GATEA-I1)") (class "Default")
      (node (ref "4_INP_OR_GATE") (pin "3") (pinfunction "I1_3") (pintype "input"))
      (node (ref "AND_GATE3_") (pin "11") (pinfunction "O_11") (pintype "output"))
    )
    (net (code "4") (name "Net-(4_INP_OR_GATEA-I2)") (class "Default")
      (node (ref "4_INP_OR_GATE") (pin "4") (pinfunction "I2_4") (pintype "input"))
      (node (ref "AND_GATE4_") (pin "3") (pinfunction "O_3") (pintype "output"))
    )
    (net (code "5") (name "Net-(4_INP_OR_GATEA-I3)") (class "Default")
      (node (ref "4_INP_OR_GATE") (pin "5") (pinfunction "I3_5") (pintype "input"))
      (node (ref "AND_GATE4_") (pin "6") (pinfunction "O_6") (pintype "output"))
    )
    (net (code "6") (name "Net-(4_INP_OR_GATEA-O)") (class "Default")
      (node (ref "4_INP_OR_GATE") (pin "1") (pinfunction "O_1") (pintype "output"))
      (node (ref "AND_GATE3_") (pin "4") (pinfunction "I0_4") (pintype "input"))
      (node (ref "AND_GATE3_") (pin "9") (pinfunction "I0_9") (pintype "input"))
    )
    (net (code "7") (name "Net-(ADDER_LOWERA-A1)") (class "Default")
      (node (ref "ADDER_LOWER") (pin "5") (pinfunction "A1_5") (pintype "input"))
      (node (ref "ADDR_REG_A_LOWER") (pin "6") (pinfunction "Q4_6") (pintype "tri_state"))
      (node (ref "AND_GATE_") (pin "12") (pinfunction "I0_12") (pintype "input"))
      (node (ref "LED_A_REG_1") (pin "A") (pinfunction "A_A") (pintype "passive"))
      (node (ref "NOT_GATE3_") (pin "5") (pinfunction "I_5") (pintype "input"))
      (node (ref "OR_GATE1") (pin "4") (pinfunction "I0_4") (pintype "input"))
      (node (ref "OUTPUT_BUFFER_REG_A") (pin "9") (pinfunction "A8_9") (pintype "bidirectional"))
      (node (ref "SUBTRACT_INVRTR_UPPER_1") (pin "2") (pinfunction "I1_2") (pintype "input"))
      (node (ref "ZERO_POS_FLAG_IDENTIFIER") (pin "5") (pinfunction "D_5") (pintype "input"))
    )
    (net (code "8") (name "Net-(ADDER_LOWERA-A2)") (class "Default")
      (node (ref "ADDER_LOWER") (pin "3") (pinfunction "A2_3") (pintype "input"))
      (node (ref "ADDR_REG_A_LOWER") (pin "5") (pinfunction "Q3_5") (pintype "tri_state"))
      (node (ref "AND_GATE1_") (pin "1") (pinfunction "I0_1") (pintype "input"))
      (node (ref "LED_A_REG_2") (pin "A") (pinfunction "A_A") (pintype "passive"))
      (node (ref "NOT_GATE3_") (pin "9") (pinfunction "I_9") (pintype "input"))
      (node (ref "OR_GATE1") (pin "10") (pinfunction "I1_10") (pintype "input"))
      (node (ref "OUTPUT_BUFFER_REG_A") (pin "8") (pinfunction "A7_8") (pintype "bidirectional"))
      (node (ref "SUBTRACT_INVRTR_UPPER_1") (pin "5") (pinfunction "I1_5") (pintype "input"))
      (node (ref "ZERO_POS_FLAG_IDENTIFIER") (pin "4") (pinfunction "C_4") (pintype "input"))
    )
    (net (code "9") (name "Net-(ADDER_LOWERA-A3)") (class "Default")
      (node (ref "ADDER_LOWER") (pin "14") (pinfunction "A3_14") (pintype "input"))
      (node (ref "ADDR_REG_A_LOWER") (pin "4") (pinfunction "Q2_4") (pintype "tri_state"))
      (node (ref "AND_GATE1_") (pin "4") (pinfunction "I0_4") (pintype "input"))
      (node (ref "LED_A_REG_3") (pin "A") (pinfunction "A_A") (pintype "passive"))
      (node (ref "NOT_GATE3_") (pin "11") (pinfunction "I_11") (pintype "input"))
      (node (ref "OR_GATE1") (pin "13") (pinfunction "I1_13") (pintype "input"))
      (node (ref "OUTPUT_BUFFER_REG_A") (pin "7") (pinfunction "A6_7") (pintype "bidirectional"))
      (node (ref "SUBTRACT_INVRTR_UPPER_1") (pin "10") (pinfunction "I1_10") (pintype "input"))
      (node (ref "ZERO_POS_FLAG_IDENTIFIER") (pin "3") (pinfunction "B_3") (pintype "input"))
    )
    (net (code "10") (name "Net-(ADDER_LOWERA-A4)") (class "Default")
      (node (ref "ADDER_LOWER") (pin "12") (pinfunction "A4_12") (pintype "input"))
      (node (ref "ADDR_REG_A_LOWER") (pin "3") (pinfunction "Q1_3") (pintype "tri_state"))
      (node (ref "AND_GATE1_") (pin "9") (pinfunction "I0_9") (pintype "input"))
      (node (ref "LED_A_REG_4") (pin "A") (pinfunction "A_A") (pintype "passive"))
      (node (ref "NOT_GATE3_") (pin "13") (pinfunction "I_13") (pintype "input"))
      (node (ref "OR_GATE") (pin "2") (pinfunction "I1_2") (pintype "input"))
      (node (ref "OUTPUT_BUFFER_REG_A") (pin "6") (pinfunction "A5_6") (pintype "bidirectional"))
      (node (ref "SUBTRACT_INVRTR_UPPER_1") (pin "13") (pinfunction "I1_13") (pintype "input"))
      (node (ref "ZERO_POS_FLAG_IDENTIFIER") (pin "2") (pinfunction "A_2") (pintype "input"))
    )
    (net (code "11") (name "Net-(ADDER_LOWERA-B1)") (class "Default")
      (node (ref "ADDER_LOWER") (pin "6") (pinfunction "B1_6") (pintype "input"))
      (node (ref "SUBTRACT_INVRTR_LOWER_") (pin "11") (pinfunction "O_11") (pintype "output"))
    )
    (net (code "12") (name "Net-(ADDER_LOWERA-B2)") (class "Default")
      (node (ref "ADDER_LOWER") (pin "2") (pinfunction "B2_2") (pintype "input"))
      (node (ref "SUBTRACT_INVRTR_LOWER_") (pin "8") (pinfunction "O_8") (pintype "output"))
    )
    (net (code "13") (name "Net-(ADDER_LOWERA-B3)") (class "Default")
      (node (ref "ADDER_LOWER") (pin "15") (pinfunction "B3_15") (pintype "input"))
      (node (ref "SUBTRACT_INVRTR_LOWER_") (pin "6") (pinfunction "O_6") (pintype "output"))
    )
    (net (code "14") (name "Net-(ADDER_LOWERA-B4)") (class "Default")
      (node (ref "ADDER_LOWER") (pin "11") (pinfunction "B4_11") (pintype "input"))
      (node (ref "SUBTRACT_INVRTR_LOWER_") (pin "3") (pinfunction "O_3") (pintype "output"))
    )
    (net (code "15") (name "Net-(ADDER_LOWERA-C0)") (class "Default")
      (node (ref "ADDER_LOWER") (pin "7") (pinfunction "C0_7") (pintype "input"))
      (node (ref "INSTRUCTION_MEMORY_UPPER") (pin "15") (pinfunction "15_15") (pintype "passive"))
      (node (ref "SUBTRACT_INVRTR_LOWER_") (pin "1") (pinfunction "I0_1") (pintype "input"))
      (node (ref "SUBTRACT_INVRTR_LOWER_") (pin "12") (pinfunction "I0_12") (pintype "input"))
      (node (ref "SUBTRACT_INVRTR_LOWER_") (pin "4") (pinfunction "I0_4") (pintype "input"))
      (node (ref "SUBTRACT_INVRTR_LOWER_") (pin "9") (pinfunction "I0_9") (pintype "input"))
      (node (ref "SUBTRACT_INVRTR_UPPER_") (pin "1") (pinfunction "I0_1") (pintype "input"))
      (node (ref "SUBTRACT_INVRTR_UPPER_") (pin "12") (pinfunction "I0_12") (pintype "input"))
      (node (ref "SUBTRACT_INVRTR_UPPER_") (pin "4") (pinfunction "I0_4") (pintype "input"))
      (node (ref "SUBTRACT_INVRTR_UPPER_") (pin "9") (pinfunction "I0_9") (pintype "input"))
    )
    (net (code "16") (name "Net-(ADDER_LOWERA-C4)") (class "Default")
      (node (ref "ADDER_LOWER") (pin "9") (pinfunction "C4_9") (pintype "output"))
      (node (ref "ADDER_UPPER") (pin "7") (pinfunction "C0_7") (pintype "input"))
    )
    (net (code "17") (name "Net-(ADDER_LOWERA-S1)") (class "Default")
      (node (ref "ADDER_LOWER") (pin "4") (pinfunction "S1_4") (pintype "output"))
      (node (ref "OUTPUT_BUFFER_ALU") (pin "18") (pinfunction "B1_18") (pintype "bidirectional"))
    )
    (net (code "18") (name "Net-(ADDER_LOWERA-S2)") (class "Default")
      (node (ref "ADDER_LOWER") (pin "1") (pinfunction "S2_1") (pintype "output"))
      (node (ref "OUTPUT_BUFFER_ALU") (pin "17") (pinfunction "B2_17") (pintype "bidirectional"))
    )
    (net (code "19") (name "Net-(ADDER_LOWERA-S3)") (class "Default")
      (node (ref "ADDER_LOWER") (pin "13") (pinfunction "S3_13") (pintype "output"))
      (node (ref "OUTPUT_BUFFER_ALU") (pin "16") (pinfunction "B3_16") (pintype "bidirectional"))
    )
    (net (code "20") (name "Net-(ADDER_LOWERA-S4)") (class "Default")
      (node (ref "ADDER_LOWER") (pin "10") (pinfunction "S4_10") (pintype "output"))
      (node (ref "OUTPUT_BUFFER_ALU") (pin "15") (pinfunction "B4_15") (pintype "bidirectional"))
    )
    (net (code "21") (name "Net-(ADDER_UPPERA-A1)") (class "Default")
      (node (ref "ADDER_UPPER") (pin "5") (pinfunction "A1_5") (pintype "input"))
      (node (ref "ADDR_REG_A_UPPER") (pin "6") (pinfunction "Q4_6") (pintype "tri_state"))
      (node (ref "AND_GATE1_") (pin "12") (pinfunction "I0_12") (pintype "input"))
      (node (ref "LED_A_REG_5") (pin "A") (pinfunction "A_A") (pintype "passive"))
      (node (ref "NOT_GATE_") (pin "1") (pinfunction "I_1") (pintype "input"))
      (node (ref "OR_GATE") (pin "5") (pinfunction "I1_5") (pintype "input"))
      (node (ref "OUTPUT_BUFFER_REG_A") (pin "5") (pinfunction "A4_5") (pintype "bidirectional"))
      (node (ref "SUBTRACT_INVRTR_LOWER_1") (pin "2") (pinfunction "I1_2") (pintype "input"))
      (node (ref "ZERO_POS_FLAG_IDENTIFIER") (pin "9") (pinfunction "E_9") (pintype "input"))
    )
    (net (code "22") (name "Net-(ADDER_UPPERA-A2)") (class "Default")
      (node (ref "ADDER_UPPER") (pin "3") (pinfunction "A2_3") (pintype "input"))
      (node (ref "ADDR_REG_A_UPPER") (pin "5") (pinfunction "Q3_5") (pintype "tri_state"))
      (node (ref "AND_GATE2_") (pin "1") (pinfunction "I0_1") (pintype "input"))
      (node (ref "LED_A_REG_6") (pin "A") (pinfunction "A_A") (pintype "passive"))
      (node (ref "NOT_GATE_") (pin "3") (pinfunction "I_3") (pintype "input"))
      (node (ref "OR_GATE") (pin "10") (pinfunction "I1_10") (pintype "input"))
      (node (ref "OUTPUT_BUFFER_REG_A") (pin "4") (pinfunction "A3_4") (pintype "bidirectional"))
      (node (ref "SUBTRACT_INVRTR_LOWER_1") (pin "5") (pinfunction "I1_5") (pintype "input"))
      (node (ref "ZERO_POS_FLAG_IDENTIFIER") (pin "10") (pinfunction "F_10") (pintype "input"))
    )
    (net (code "23") (name "Net-(ADDER_UPPERA-A3)") (class "Default")
      (node (ref "ADDER_UPPER") (pin "14") (pinfunction "A3_14") (pintype "input"))
      (node (ref "ADDR_REG_A_UPPER") (pin "4") (pinfunction "Q2_4") (pintype "tri_state"))
      (node (ref "AND_GATE2_") (pin "5") (pinfunction "I1_5") (pintype "input"))
      (node (ref "LED_A_REG_7") (pin "A") (pinfunction "A_A") (pintype "passive"))
      (node (ref "NOT_GATE_") (pin "5") (pinfunction "I_5") (pintype "input"))
      (node (ref "OR_GATE") (pin "12") (pinfunction "I0_12") (pintype "input"))
      (node (ref "OUTPUT_BUFFER_REG_A") (pin "3") (pinfunction "A2_3") (pintype "bidirectional"))
      (node (ref "SUBTRACT_INVRTR_LOWER_1") (pin "10") (pinfunction "I1_10") (pintype "input"))
      (node (ref "ZERO_POS_FLAG_IDENTIFIER") (pin "11") (pinfunction "G_11") (pintype "input"))
    )
    (net (code "24") (name "Net-(ADDER_UPPERA-A4)") (class "Default")
      (node (ref "ADDER_UPPER") (pin "12") (pinfunction "A4_12") (pintype "input"))
      (node (ref "ADDR_REG_A_UPPER") (pin "3") (pinfunction "Q1_3") (pintype "tri_state"))
      (node (ref "AND_GATE2_") (pin "9") (pinfunction "I0_9") (pintype "input"))
      (node (ref "LED_A_REG_8") (pin "A") (pinfunction "A_A") (pintype "passive"))
      (node (ref "NOT_GATE_") (pin "9") (pinfunction "I_9") (pintype "input"))
      (node (ref "OR_GATE_2") (pin "2") (pinfunction "I1_2") (pintype "input"))
      (node (ref "OUTPUT_BUFFER_REG_A") (pin "2") (pinfunction "A1_2") (pintype "bidirectional"))
      (node (ref "SUBTRACT_INVRTR_LOWER_1") (pin "13") (pinfunction "I1_13") (pintype "input"))
      (node (ref "ZERO_POS_FLAG_IDENTIFIER") (pin "12") (pinfunction "H_12") (pintype "input"))
    )
    (net (code "25") (name "Net-(ADDER_UPPERA-B1)") (class "Default")
      (node (ref "ADDER_UPPER") (pin "6") (pinfunction "B1_6") (pintype "input"))
      (node (ref "SUBTRACT_INVRTR_UPPER_") (pin "11") (pinfunction "O_11") (pintype "output"))
    )
    (net (code "26") (name "Net-(ADDER_UPPERA-B2)") (class "Default")
      (node (ref "ADDER_UPPER") (pin "2") (pinfunction "B2_2") (pintype "input"))
      (node (ref "SUBTRACT_INVRTR_UPPER_") (pin "8") (pinfunction "O_8") (pintype "output"))
    )
    (net (code "27") (name "Net-(ADDER_UPPERA-B3)") (class "Default")
      (node (ref "ADDER_UPPER") (pin "15") (pinfunction "B3_15") (pintype "input"))
      (node (ref "SUBTRACT_INVRTR_UPPER_") (pin "6") (pinfunction "O_6") (pintype "output"))
    )
    (net (code "28") (name "Net-(ADDER_UPPERA-B4)") (class "Default")
      (node (ref "ADDER_UPPER") (pin "11") (pinfunction "B4_11") (pintype "input"))
      (node (ref "SUBTRACT_INVRTR_UPPER_") (pin "3") (pinfunction "O_3") (pintype "output"))
    )
    (net (code "29") (name "Net-(ADDER_UPPERA-C4)") (class "Default")
      (node (ref "ADDER_UPPER") (pin "9") (pinfunction "C4_9") (pintype "output"))
      (node (ref "AND_GATE3_") (pin "13") (pinfunction "I1_13") (pintype "input"))
      (node (ref "FLAG_REG_LOWER") (pin "14") (pinfunction "D1_14") (pintype "input"))
      (node (ref "OVERFLOW_FLAG") (pin "A") (pinfunction "A_A") (pintype "passive"))
    )
    (net (code "30") (name "Net-(ADDER_UPPERA-S1)") (class "Default")
      (node (ref "ADDER_UPPER") (pin "4") (pinfunction "S1_4") (pintype "output"))
      (node (ref "OUTPUT_BUFFER_ALU") (pin "14") (pinfunction "B5_14") (pintype "bidirectional"))
    )
    (net (code "31") (name "Net-(ADDER_UPPERA-S2)") (class "Default")
      (node (ref "ADDER_UPPER") (pin "1") (pinfunction "S2_1") (pintype "output"))
      (node (ref "OUTPUT_BUFFER_ALU") (pin "13") (pinfunction "B6_13") (pintype "bidirectional"))
    )
    (net (code "32") (name "Net-(ADDER_UPPERA-S3)") (class "Default")
      (node (ref "ADDER_UPPER") (pin "13") (pinfunction "S3_13") (pintype "output"))
      (node (ref "OUTPUT_BUFFER_ALU") (pin "12") (pinfunction "B7_12") (pintype "bidirectional"))
    )
    (net (code "33") (name "Net-(ADDER_UPPERA-S4)") (class "Default")
      (node (ref "ADDER_UPPER") (pin "10") (pinfunction "S4_10") (pintype "output"))
      (node (ref "OUTPUT_BUFFER_ALU") (pin "11") (pinfunction "B8_11") (pintype "bidirectional"))
    )
    (net (code "34") (name "Net-(ADDR_MEM_REG_LOWERA-CLK)") (class "Default")
      (node (ref "ADDR_MEM_REG_LOWER") (pin "7") (pinfunction "CLK_7") (pintype "input"))
      (node (ref "ADDR_MEM_REG_UPPER") (pin "7") (pinfunction "CLK_7") (pintype "input"))
      (node (ref "ADDR_REG_A_LOWER") (pin "7") (pinfunction "CLK_7") (pintype "input"))
      (node (ref "ADDR_REG_A_UPPER") (pin "7") (pinfunction "CLK_7") (pintype "input"))
      (node (ref "ADDR_REG_CALC_LOWER") (pin "7") (pinfunction "CLK_7") (pintype "input"))
      (node (ref "ADDR_REG_CALC_LOWER1") (pin "7") (pinfunction "CLK_7") (pintype "input"))
      (node (ref "ADDR_REG_CALC_UPPER") (pin "7") (pinfunction "CLK_7") (pintype "input"))
      (node (ref "ADDR_REG_PARAM_UPPER") (pin "7") (pinfunction "CLK_7") (pintype "input"))
      (node (ref "AND_GATE_") (pin "8") (pinfunction "O_8") (pintype "output"))
      (node (ref "CLOCK") (pin "A") (pinfunction "A_A") (pintype "passive"))
      (node (ref "EXTENTION") (pin "9") (pinfunction "1_9") (pintype "passive"))
      (node (ref "FLAG_REG_LOWER") (pin "7") (pinfunction "CLK_7") (pintype "input"))
      (node (ref "FLAG_REG_UPPER") (pin "7") (pinfunction "CLK_7") (pintype "input"))
      (node (ref "INSTRUC_REGISTER_LOWER") (pin "7") (pinfunction "CLK_7") (pintype "input"))
      (node (ref "INSTRUC_REGISTER_UPPER") (pin "7") (pinfunction "CLK_7") (pintype "input"))
      (node (ref "INVERTED_CLK_LED") (pin "A") (pinfunction "A_A") (pintype "passive"))
      (node (ref "NOT_GATE1") (pin "11") (pinfunction "I_11") (pintype "input"))
      (node (ref "PROGRAM_COUNTER_LOWER") (pin "2") (pinfunction "2_2") (pintype "passive"))
      (node (ref "PROGRAM_COUNTER_UPPER") (pin "2") (pinfunction "2_2") (pintype "passive"))
      (node (ref "RAM_ADDR_LOWER") (pin "7") (pinfunction "CLK_7") (pintype "input"))
      (node (ref "RAM_ADDR_UPPER") (pin "7") (pinfunction "CLK_7") (pintype "input"))
    )
    (net (code "35") (name "Net-(ADDR_MEM_REG_LOWERA-D1)") (class "Default")
      (node (ref "ADDR_MEM_REG_LOWER") (pin "14") (pinfunction "D1_14") (pintype "input"))
      (node (ref "ADDR_REG_A_LOWER") (pin "14") (pinfunction "D1_14") (pintype "input"))
      (node (ref "ADDR_REG_CALC_LOWER") (pin "14") (pinfunction "D1_14") (pintype "input"))
      (node (ref "ADDR_REG_CALC_LOWER1") (pin "14") (pinfunction "D1_14") (pintype "input"))
      (node (ref "DATABUS_4") (pin "A") (pinfunction "A_A") (pintype "passive"))
      (node (ref "EXTENTION") (pin "4") (pinfunction "1_4") (pintype "passive"))
      (node (ref "INSTRUC_REGISTER_LOWER") (pin "14") (pinfunction "D1_14") (pintype "input"))
      (node (ref "MICRO_COUNTER_LOWER") (pin "6") (pinfunction "6_6") (pintype "passive"))
      (node (ref "OUTPUT_BUFFER_ALU") (pin "5") (pinfunction "A4_5") (pintype "bidirectional"))
      (node (ref "OUTPUT_BUFFER_CALC_REG") (pin "14") (pinfunction "B5_14") (pintype "bidirectional"))
      (node (ref "OUTPUT_BUFFER_FLAGS") (pin "5") (pinfunction "A4_5") (pintype "bidirectional"))
      (node (ref "OUTPUT_BUFFER_INSTRUCTION") (pin "14") (pinfunction "B5_14") (pintype "bidirectional"))
      (node (ref "OUTPUT_BUFFER_LOGIC") (pin "15") (pinfunction "B4_15") (pintype "bidirectional"))
      (node (ref "OUTPUT_BUFFER_MEMORY") (pin "14") (pinfunction "B5_14") (pintype "bidirectional"))
      (node (ref "OUTPUT_BUFFER_PARAM_REG") (pin "14") (pinfunction "B5_14") (pintype "bidirectional"))
      (node (ref "OUTPUT_BUFFER_PC") (pin "14") (pinfunction "B5_14") (pintype "bidirectional"))
      (node (ref "OUTPUT_BUFFER_RAM") (pin "15") (pinfunction "B4_15") (pintype "bidirectional"))
      (node (ref "OUTPUT_BUFFER_REG_A") (pin "14") (pinfunction "B5_14") (pintype "bidirectional"))
      (node (ref "PROGRAM_COUNTER_LOWER") (pin "6") (pinfunction "6_6") (pintype "passive"))
      (node (ref "RAM_ADDR_LOWER") (pin "11") (pinfunction "D4_11") (pintype "input"))
      (node (ref "XOR_GATE_1") (pin "13") (pinfunction "I1_13") (pintype "input"))
    )
    (net (code "36") (name "Net-(ADDR_MEM_REG_LOWERA-D2)") (class "Default")
      (node (ref "ADDR_MEM_REG_LOWER") (pin "13") (pinfunction "D2_13") (pintype "input"))
      (node (ref "ADDR_REG_A_LOWER") (pin "13") (pinfunction "D2_13") (pintype "input"))
      (node (ref "ADDR_REG_CALC_LOWER") (pin "13") (pinfunction "D2_13") (pintype "input"))
      (node (ref "ADDR_REG_CALC_LOWER1") (pin "13") (pinfunction "D2_13") (pintype "input"))
      (node (ref "DATABUS_3") (pin "A") (pinfunction "A_A") (pintype "passive"))
      (node (ref "EXTENTION") (pin "3") (pinfunction "1_3") (pintype "passive"))
      (node (ref "INSTRUC_REGISTER_LOWER") (pin "13") (pinfunction "D2_13") (pintype "input"))
      (node (ref "MICRO_COUNTER_LOWER") (pin "5") (pinfunction "5_5") (pintype "passive"))
      (node (ref "OUTPUT_BUFFER_ALU") (pin "4") (pinfunction "A3_4") (pintype "bidirectional"))
      (node (ref "OUTPUT_BUFFER_CALC_REG") (pin "13") (pinfunction "B6_13") (pintype "bidirectional"))
      (node (ref "OUTPUT_BUFFER_FLAGS") (pin "4") (pinfunction "A3_4") (pintype "bidirectional"))
      (node (ref "OUTPUT_BUFFER_INSTRUCTION") (pin "13") (pinfunction "B6_13") (pintype "bidirectional"))
      (node (ref "OUTPUT_BUFFER_LOGIC") (pin "16") (pinfunction "B3_16") (pintype "bidirectional"))
      (node (ref "OUTPUT_BUFFER_MEMORY") (pin "13") (pinfunction "B6_13") (pintype "bidirectional"))
      (node (ref "OUTPUT_BUFFER_PARAM_REG") (pin "13") (pinfunction "B6_13") (pintype "bidirectional"))
      (node (ref "OUTPUT_BUFFER_PC") (pin "13") (pinfunction "B6_13") (pintype "bidirectional"))
      (node (ref "OUTPUT_BUFFER_RAM") (pin "16") (pinfunction "B3_16") (pintype "bidirectional"))
      (node (ref "OUTPUT_BUFFER_REG_A") (pin "13") (pinfunction "B6_13") (pintype "bidirectional"))
      (node (ref "PROGRAM_COUNTER_LOWER") (pin "5") (pinfunction "5_5") (pintype "passive"))
      (node (ref "RAM_ADDR_LOWER") (pin "12") (pinfunction "D3_12") (pintype "input"))
      (node (ref "XOR_GATE_1") (pin "10") (pinfunction "I1_10") (pintype "input"))
    )
    (net (code "37") (name "Net-(ADDR_MEM_REG_LOWERA-D3)") (class "Default")
      (node (ref "ADDR_MEM_REG_LOWER") (pin "12") (pinfunction "D3_12") (pintype "input"))
      (node (ref "ADDR_REG_A_LOWER") (pin "12") (pinfunction "D3_12") (pintype "input"))
      (node (ref "ADDR_REG_CALC_LOWER") (pin "12") (pinfunction "D3_12") (pintype "input"))
      (node (ref "ADDR_REG_CALC_LOWER1") (pin "12") (pinfunction "D3_12") (pintype "input"))
      (node (ref "DATABUS_2") (pin "A") (pinfunction "A_A") (pintype "passive"))
      (node (ref "EXTENTION") (pin "2") (pinfunction "1_2") (pintype "passive"))
      (node (ref "INSTRUC_REGISTER_LOWER") (pin "12") (pinfunction "D3_12") (pintype "input"))
      (node (ref "MICRO_COUNTER_LOWER") (pin "4") (pinfunction "4_4") (pintype "passive"))
      (node (ref "OUTPUT_BUFFER_ALU") (pin "3") (pinfunction "A2_3") (pintype "bidirectional"))
      (node (ref "OUTPUT_BUFFER_CALC_REG") (pin "12") (pinfunction "B7_12") (pintype "bidirectional"))
      (node (ref "OUTPUT_BUFFER_FLAGS") (pin "3") (pinfunction "A2_3") (pintype "bidirectional"))
      (node (ref "OUTPUT_BUFFER_INSTRUCTION") (pin "12") (pinfunction "B7_12") (pintype "bidirectional"))
      (node (ref "OUTPUT_BUFFER_LOGIC") (pin "17") (pinfunction "B2_17") (pintype "bidirectional"))
      (node (ref "OUTPUT_BUFFER_MEMORY") (pin "12") (pinfunction "B7_12") (pintype "bidirectional"))
      (node (ref "OUTPUT_BUFFER_PARAM_REG") (pin "12") (pinfunction "B7_12") (pintype "bidirectional"))
      (node (ref "OUTPUT_BUFFER_PC") (pin "12") (pinfunction "B7_12") (pintype "bidirectional"))
      (node (ref "OUTPUT_BUFFER_RAM") (pin "17") (pinfunction "B2_17") (pintype "bidirectional"))
      (node (ref "OUTPUT_BUFFER_REG_A") (pin "12") (pinfunction "B7_12") (pintype "bidirectional"))
      (node (ref "PROGRAM_COUNTER_LOWER") (pin "4") (pinfunction "4_4") (pintype "passive"))
      (node (ref "RAM_ADDR_LOWER") (pin "13") (pinfunction "D2_13") (pintype "input"))
      (node (ref "XOR_GATE_1") (pin "5") (pinfunction "I1_5") (pintype "input"))
    )
    (net (code "38") (name "Net-(ADDR_MEM_REG_LOWERA-D4)") (class "Default")
      (node (ref "ADDR_MEM_REG_LOWER") (pin "11") (pinfunction "D4_11") (pintype "input"))
      (node (ref "ADDR_REG_A_LOWER") (pin "11") (pinfunction "D4_11") (pintype "input"))
      (node (ref "ADDR_REG_CALC_LOWER") (pin "11") (pinfunction "D4_11") (pintype "input"))
      (node (ref "ADDR_REG_CALC_LOWER1") (pin "11") (pinfunction "D4_11") (pintype "input"))
      (node (ref "DATABUS_1") (pin "A") (pinfunction "A_A") (pintype "passive"))
      (node (ref "EXTENTION") (pin "1") (pinfunction "1_1") (pintype "passive"))
      (node (ref "INSTRUC_REGISTER_LOWER") (pin "11") (pinfunction "D4_11") (pintype "input"))
      (node (ref "MICRO_COUNTER_LOWER") (pin "3") (pinfunction "3_3") (pintype "passive"))
      (node (ref "OUTPUT_BUFFER_ALU") (pin "2") (pinfunction "A1_2") (pintype "bidirectional"))
      (node (ref "OUTPUT_BUFFER_CALC_REG") (pin "11") (pinfunction "B8_11") (pintype "bidirectional"))
      (node (ref "OUTPUT_BUFFER_FLAGS") (pin "2") (pinfunction "A1_2") (pintype "bidirectional"))
      (node (ref "OUTPUT_BUFFER_INSTRUCTION") (pin "11") (pinfunction "B8_11") (pintype "bidirectional"))
      (node (ref "OUTPUT_BUFFER_LOGIC") (pin "18") (pinfunction "B1_18") (pintype "bidirectional"))
      (node (ref "OUTPUT_BUFFER_MEMORY") (pin "11") (pinfunction "B8_11") (pintype "bidirectional"))
      (node (ref "OUTPUT_BUFFER_PARAM_REG") (pin "11") (pinfunction "B8_11") (pintype "bidirectional"))
      (node (ref "OUTPUT_BUFFER_PC") (pin "11") (pinfunction "B8_11") (pintype "bidirectional"))
      (node (ref "OUTPUT_BUFFER_RAM") (pin "18") (pinfunction "B1_18") (pintype "bidirectional"))
      (node (ref "OUTPUT_BUFFER_REG_A") (pin "11") (pinfunction "B8_11") (pintype "bidirectional"))
      (node (ref "PROGRAM_COUNTER_LOWER") (pin "3") (pinfunction "3_3") (pintype "passive"))
      (node (ref "RAM_ADDR_LOWER") (pin "14") (pinfunction "D1_14") (pintype "input"))
      (node (ref "XOR_GATE_1") (pin "2") (pinfunction "I1_2") (pintype "input"))
    )
    (net (code "39") (name "Net-(ADDR_MEM_REG_LOWERA-G1)") (class "Default")
      (node (ref "ADDR_MEM_REG_LOWER") (pin "10") (pinfunction "G2_10") (pintype "input"))
      (node (ref "ADDR_MEM_REG_LOWER") (pin "9") (pinfunction "G1_9") (pintype "input"))
      (node (ref "ADDR_MEM_REG_UPPER") (pin "10") (pinfunction "G2_10") (pintype "input"))
      (node (ref "ADDR_MEM_REG_UPPER") (pin "9") (pinfunction "G1_9") (pintype "input"))
      (node (ref "NOT_GATE1") (pin "6") (pinfunction "O_6") (pintype "output"))
    )
    (net (code "40") (name "Net-(ADDR_MEM_REG_LOWERA-Q1)") (class "Default")
      (node (ref "ADDR_MEM_REG_LOWER") (pin "3") (pinfunction "Q1_3") (pintype "tri_state"))
      (node (ref "MEMORY") (pin "7") (pinfunction "7_7") (pintype "passive"))
    )
    (net (code "41") (name "Net-(ADDR_MEM_REG_LOWERA-Q2)") (class "Default")
      (node (ref "ADDR_MEM_REG_LOWER") (pin "4") (pinfunction "Q2_4") (pintype "tri_state"))
      (node (ref "MEMORY") (pin "8") (pinfunction "8_8") (pintype "passive"))
    )
    (net (code "42") (name "Net-(ADDR_MEM_REG_LOWERA-Q3)") (class "Default")
      (node (ref "ADDR_MEM_REG_LOWER") (pin "5") (pinfunction "Q3_5") (pintype "tri_state"))
      (node (ref "MEMORY") (pin "9") (pinfunction "9_9") (pintype "passive"))
    )
    (net (code "43") (name "Net-(ADDR_MEM_REG_LOWERA-Q4)") (class "Default")
      (node (ref "ADDR_MEM_REG_LOWER") (pin "6") (pinfunction "Q4_6") (pintype "tri_state"))
      (node (ref "MEMORY") (pin "10") (pinfunction "10_10") (pintype "passive"))
    )
    (net (code "44") (name "Net-(ADDR_MEM_REG_UPPERA-D1)") (class "Default")
      (node (ref "ADDR_MEM_REG_UPPER") (pin "14") (pinfunction "D1_14") (pintype "input"))
      (node (ref "ADDR_REG_A_UPPER") (pin "14") (pinfunction "D1_14") (pintype "input"))
      (node (ref "ADDR_REG_CALC_UPPER") (pin "14") (pinfunction "D1_14") (pintype "input"))
      (node (ref "ADDR_REG_PARAM_UPPER") (pin "14") (pinfunction "D1_14") (pintype "input"))
      (node (ref "DATABUS_8") (pin "A") (pinfunction "A_A") (pintype "passive"))
      (node (ref "EXTENTION") (pin "8") (pinfunction "1_8") (pintype "passive"))
      (node (ref "INSTRUC_REGISTER_UPPER") (pin "14") (pinfunction "D1_14") (pintype "input"))
      (node (ref "OUTPUT_BUFFER_ALU") (pin "9") (pinfunction "A8_9") (pintype "bidirectional"))
      (node (ref "OUTPUT_BUFFER_CALC_REG") (pin "18") (pinfunction "B1_18") (pintype "bidirectional"))
      (node (ref "OUTPUT_BUFFER_FLAGS") (pin "9") (pinfunction "A8_9") (pintype "bidirectional"))
      (node (ref "OUTPUT_BUFFER_INSTRUCTION") (pin "18") (pinfunction "B1_18") (pintype "bidirectional"))
      (node (ref "OUTPUT_BUFFER_LOGIC") (pin "11") (pinfunction "B8_11") (pintype "bidirectional"))
      (node (ref "OUTPUT_BUFFER_MEMORY") (pin "18") (pinfunction "B1_18") (pintype "bidirectional"))
      (node (ref "OUTPUT_BUFFER_PARAM_REG") (pin "18") (pinfunction "B1_18") (pintype "bidirectional"))
      (node (ref "OUTPUT_BUFFER_PC") (pin "18") (pinfunction "B1_18") (pintype "bidirectional"))
      (node (ref "OUTPUT_BUFFER_RAM") (pin "11") (pinfunction "B8_11") (pintype "bidirectional"))
      (node (ref "OUTPUT_BUFFER_REG_A") (pin "18") (pinfunction "B1_18") (pintype "bidirectional"))
      (node (ref "PROGRAM_COUNTER_UPPER") (pin "6") (pinfunction "6_6") (pintype "passive"))
      (node (ref "RAM_ADDR_UPPER") (pin "11") (pinfunction "D4_11") (pintype "input"))
    )
    (net (code "45") (name "Net-(ADDR_MEM_REG_UPPERA-D2)") (class "Default")
      (node (ref "ADDR_MEM_REG_UPPER") (pin "13") (pinfunction "D2_13") (pintype "input"))
      (node (ref "ADDR_REG_A_UPPER") (pin "13") (pinfunction "D2_13") (pintype "input"))
      (node (ref "ADDR_REG_CALC_UPPER") (pin "13") (pinfunction "D2_13") (pintype "input"))
      (node (ref "ADDR_REG_PARAM_UPPER") (pin "13") (pinfunction "D2_13") (pintype "input"))
      (node (ref "DATABUS_7") (pin "A") (pinfunction "A_A") (pintype "passive"))
      (node (ref "EXTENTION") (pin "7") (pinfunction "1_7") (pintype "passive"))
      (node (ref "INSTRUC_REGISTER_UPPER") (pin "13") (pinfunction "D2_13") (pintype "input"))
      (node (ref "OUTPUT_BUFFER_ALU") (pin "8") (pinfunction "A7_8") (pintype "bidirectional"))
      (node (ref "OUTPUT_BUFFER_CALC_REG") (pin "17") (pinfunction "B2_17") (pintype "bidirectional"))
      (node (ref "OUTPUT_BUFFER_FLAGS") (pin "8") (pinfunction "A7_8") (pintype "bidirectional"))
      (node (ref "OUTPUT_BUFFER_INSTRUCTION") (pin "17") (pinfunction "B2_17") (pintype "bidirectional"))
      (node (ref "OUTPUT_BUFFER_LOGIC") (pin "12") (pinfunction "B7_12") (pintype "bidirectional"))
      (node (ref "OUTPUT_BUFFER_MEMORY") (pin "17") (pinfunction "B2_17") (pintype "bidirectional"))
      (node (ref "OUTPUT_BUFFER_PARAM_REG") (pin "17") (pinfunction "B2_17") (pintype "bidirectional"))
      (node (ref "OUTPUT_BUFFER_PC") (pin "17") (pinfunction "B2_17") (pintype "bidirectional"))
      (node (ref "OUTPUT_BUFFER_RAM") (pin "12") (pinfunction "B7_12") (pintype "bidirectional"))
      (node (ref "OUTPUT_BUFFER_REG_A") (pin "17") (pinfunction "B2_17") (pintype "bidirectional"))
      (node (ref "PROGRAM_COUNTER_UPPER") (pin "5") (pinfunction "5_5") (pintype "passive"))
      (node (ref "RAM_ADDR_UPPER") (pin "12") (pinfunction "D3_12") (pintype "input"))
      (node (ref "XOR_GATE_2") (pin "10") (pinfunction "I1_10") (pintype "input"))
    )
    (net (code "46") (name "Net-(ADDR_MEM_REG_UPPERA-D3)") (class "Default")
      (node (ref "ADDR_MEM_REG_UPPER") (pin "12") (pinfunction "D3_12") (pintype "input"))
      (node (ref "ADDR_REG_A_UPPER") (pin "12") (pinfunction "D3_12") (pintype "input"))
      (node (ref "ADDR_REG_CALC_UPPER") (pin "12") (pinfunction "D3_12") (pintype "input"))
      (node (ref "ADDR_REG_PARAM_UPPER") (pin "12") (pinfunction "D3_12") (pintype "input"))
      (node (ref "DATABUS_6") (pin "A") (pinfunction "A_A") (pintype "passive"))
      (node (ref "EXTENTION") (pin "6") (pinfunction "1_6") (pintype "passive"))
      (node (ref "INSTRUC_REGISTER_UPPER") (pin "12") (pinfunction "D3_12") (pintype "input"))
      (node (ref "OUTPUT_BUFFER_ALU") (pin "7") (pinfunction "A6_7") (pintype "bidirectional"))
      (node (ref "OUTPUT_BUFFER_CALC_REG") (pin "16") (pinfunction "B3_16") (pintype "bidirectional"))
      (node (ref "OUTPUT_BUFFER_FLAGS") (pin "7") (pinfunction "A6_7") (pintype "bidirectional"))
      (node (ref "OUTPUT_BUFFER_INSTRUCTION") (pin "16") (pinfunction "B3_16") (pintype "bidirectional"))
      (node (ref "OUTPUT_BUFFER_LOGIC") (pin "13") (pinfunction "B6_13") (pintype "bidirectional"))
      (node (ref "OUTPUT_BUFFER_MEMORY") (pin "16") (pinfunction "B3_16") (pintype "bidirectional"))
      (node (ref "OUTPUT_BUFFER_PARAM_REG") (pin "16") (pinfunction "B3_16") (pintype "bidirectional"))
      (node (ref "OUTPUT_BUFFER_PC") (pin "16") (pinfunction "B3_16") (pintype "bidirectional"))
      (node (ref "OUTPUT_BUFFER_RAM") (pin "13") (pinfunction "B6_13") (pintype "bidirectional"))
      (node (ref "OUTPUT_BUFFER_REG_A") (pin "16") (pinfunction "B3_16") (pintype "bidirectional"))
      (node (ref "PROGRAM_COUNTER_UPPER") (pin "4") (pinfunction "4_4") (pintype "passive"))
      (node (ref "RAM_ADDR_UPPER") (pin "13") (pinfunction "D2_13") (pintype "input"))
      (node (ref "XOR_GATE_2") (pin "5") (pinfunction "I1_5") (pintype "input"))
    )
    (net (code "47") (name "Net-(ADDR_MEM_REG_UPPERA-D4)") (class "Default")
      (node (ref "ADDR_MEM_REG_UPPER") (pin "11") (pinfunction "D4_11") (pintype "input"))
      (node (ref "ADDR_REG_A_UPPER") (pin "11") (pinfunction "D4_11") (pintype "input"))
      (node (ref "ADDR_REG_CALC_UPPER") (pin "11") (pinfunction "D4_11") (pintype "input"))
      (node (ref "ADDR_REG_PARAM_UPPER") (pin "11") (pinfunction "D4_11") (pintype "input"))
      (node (ref "DATABUS_5") (pin "A") (pinfunction "A_A") (pintype "passive"))
      (node (ref "EXTENTION") (pin "5") (pinfunction "1_5") (pintype "passive"))
      (node (ref "INSTRUC_REGISTER_UPPER") (pin "11") (pinfunction "D4_11") (pintype "input"))
      (node (ref "MICRO_COUNTER_UPPER") (pin "3") (pinfunction "3_3") (pintype "passive"))
      (node (ref "OUTPUT_BUFFER_ALU") (pin "6") (pinfunction "A5_6") (pintype "bidirectional"))
      (node (ref "OUTPUT_BUFFER_CALC_REG") (pin "15") (pinfunction "B4_15") (pintype "bidirectional"))
      (node (ref "OUTPUT_BUFFER_FLAGS") (pin "6") (pinfunction "A5_6") (pintype "bidirectional"))
      (node (ref "OUTPUT_BUFFER_INSTRUCTION") (pin "15") (pinfunction "B4_15") (pintype "bidirectional"))
      (node (ref "OUTPUT_BUFFER_LOGIC") (pin "14") (pinfunction "B5_14") (pintype "bidirectional"))
      (node (ref "OUTPUT_BUFFER_MEMORY") (pin "15") (pinfunction "B4_15") (pintype "bidirectional"))
      (node (ref "OUTPUT_BUFFER_PARAM_REG") (pin "15") (pinfunction "B4_15") (pintype "bidirectional"))
      (node (ref "OUTPUT_BUFFER_PC") (pin "15") (pinfunction "B4_15") (pintype "bidirectional"))
      (node (ref "OUTPUT_BUFFER_RAM") (pin "14") (pinfunction "B5_14") (pintype "bidirectional"))
      (node (ref "OUTPUT_BUFFER_REG_A") (pin "15") (pinfunction "B4_15") (pintype "bidirectional"))
      (node (ref "PROGRAM_COUNTER_UPPER") (pin "3") (pinfunction "3_3") (pintype "passive"))
      (node (ref "RAM_ADDR_UPPER") (pin "14") (pinfunction "D1_14") (pintype "input"))
      (node (ref "XOR_GATE_2") (pin "2") (pinfunction "I1_2") (pintype "input"))
    )
    (net (code "48") (name "Net-(ADDR_MEM_REG_UPPERA-Q1)") (class "Default")
      (node (ref "ADDR_MEM_REG_UPPER") (pin "3") (pinfunction "Q1_3") (pintype "tri_state"))
      (node (ref "MEMORY") (pin "3") (pinfunction "3_3") (pintype "passive"))
    )
    (net (code "49") (name "Net-(ADDR_MEM_REG_UPPERA-Q2)") (class "Default")
      (node (ref "ADDR_MEM_REG_UPPER") (pin "4") (pinfunction "Q2_4") (pintype "tri_state"))
      (node (ref "MEMORY") (pin "4") (pinfunction "4_4") (pintype "passive"))
    )
    (net (code "50") (name "Net-(ADDR_MEM_REG_UPPERA-Q3)") (class "Default")
      (node (ref "ADDR_MEM_REG_UPPER") (pin "5") (pinfunction "Q3_5") (pintype "tri_state"))
      (node (ref "MEMORY") (pin "5") (pinfunction "5_5") (pintype "passive"))
    )
    (net (code "51") (name "Net-(ADDR_MEM_REG_UPPERA-Q4)") (class "Default")
      (node (ref "ADDR_MEM_REG_UPPER") (pin "6") (pinfunction "Q4_6") (pintype "tri_state"))
      (node (ref "MEMORY") (pin "6") (pinfunction "6_6") (pintype "passive"))
    )
    (net (code "52") (name "Net-(ADDR_REG_A_LOWERA-G1)") (class "Default")
      (node (ref "ADDR_REG_A_LOWER") (pin "10") (pinfunction "G2_10") (pintype "input"))
      (node (ref "ADDR_REG_A_LOWER") (pin "9") (pinfunction "G1_9") (pintype "input"))
      (node (ref "ADDR_REG_A_UPPER") (pin "10") (pinfunction "G2_10") (pintype "input"))
      (node (ref "ADDR_REG_A_UPPER") (pin "9") (pinfunction "G1_9") (pintype "input"))
      (node (ref "BRANCH_SELECTOR") (pin "10") (pinfunction "Y2_10") (pintype "output"))
    )
    (net (code "53") (name "Net-(ADDR_REG_CALC_LOWER1A-G1)") (class "Default")
      (node (ref "ADDR_REG_CALC_LOWER1") (pin "10") (pinfunction "G2_10") (pintype "input"))
      (node (ref "ADDR_REG_CALC_LOWER1") (pin "9") (pinfunction "G1_9") (pintype "input"))
      (node (ref "ADDR_REG_PARAM_UPPER") (pin "10") (pinfunction "G2_10") (pintype "input"))
      (node (ref "ADDR_REG_PARAM_UPPER") (pin "9") (pinfunction "G1_9") (pintype "input"))
      (node (ref "NOT_GATE2_") (pin "4") (pinfunction "O_4") (pintype "output"))
    )
    (net (code "54") (name "Net-(ADDR_REG_CALC_LOWER1A-Q1)") (class "Default")
      (node (ref "ADDR_REG_CALC_LOWER1") (pin "3") (pinfunction "Q1_3") (pintype "tri_state"))
      (node (ref "OUTPUT_BUFFER_PARAM_REG") (pin "6") (pinfunction "A5_6") (pintype "bidirectional"))
      (node (ref "PARAM_LED_4") (pin "A") (pinfunction "A_A") (pintype "passive"))
    )
    (net (code "55") (name "Net-(ADDR_REG_CALC_LOWER1A-Q2)") (class "Default")
      (node (ref "ADDR_REG_CALC_LOWER1") (pin "4") (pinfunction "Q2_4") (pintype "tri_state"))
      (node (ref "OUTPUT_BUFFER_PARAM_REG") (pin "7") (pinfunction "A6_7") (pintype "bidirectional"))
      (node (ref "PARAM_LED_3") (pin "A") (pinfunction "A_A") (pintype "passive"))
    )
    (net (code "56") (name "Net-(ADDR_REG_CALC_LOWER1A-Q3)") (class "Default")
      (node (ref "ADDR_REG_CALC_LOWER1") (pin "5") (pinfunction "Q3_5") (pintype "tri_state"))
      (node (ref "OUTPUT_BUFFER_PARAM_REG") (pin "8") (pinfunction "A7_8") (pintype "bidirectional"))
      (node (ref "PARAM_LED_2") (pin "A") (pinfunction "A_A") (pintype "passive"))
    )
    (net (code "57") (name "Net-(ADDR_REG_CALC_LOWER1A-Q4)") (class "Default")
      (node (ref "ADDR_REG_CALC_LOWER1") (pin "6") (pinfunction "Q4_6") (pintype "tri_state"))
      (node (ref "OUTPUT_BUFFER_PARAM_REG") (pin "9") (pinfunction "A8_9") (pintype "bidirectional"))
      (node (ref "PARAM_LED_1") (pin "A") (pinfunction "A_A") (pintype "passive"))
    )
    (net (code "58") (name "Net-(ADDR_REG_CALC_LOWERA-G1)") (class "Default")
      (node (ref "ADDR_REG_CALC_LOWER") (pin "10") (pinfunction "G2_10") (pintype "input"))
      (node (ref "ADDR_REG_CALC_LOWER") (pin "9") (pinfunction "G1_9") (pintype "input"))
      (node (ref "ADDR_REG_CALC_UPPER") (pin "10") (pinfunction "G2_10") (pintype "input"))
      (node (ref "ADDR_REG_CALC_UPPER") (pin "9") (pinfunction "G1_9") (pintype "input"))
      (node (ref "SELECTOR_LOGIC2_") (pin "10") (pinfunction "Y2_10") (pintype "output"))
    )
    (net (code "59") (name "Net-(ADDR_REG_CALC_LOWERA-Q1)") (class "Default")
      (node (ref "ADDR_REG_CALC_LOWER") (pin "3") (pinfunction "Q1_3") (pintype "tri_state"))
      (node (ref "AND_GATE1_") (pin "10") (pinfunction "I1_10") (pintype "input"))
      (node (ref "LED_B_REG_4") (pin "A") (pinfunction "A_A") (pintype "passive"))
      (node (ref "OR_GATE") (pin "1") (pinfunction "I0_1") (pintype "input"))
      (node (ref "OUTPUT_BUFFER_CALC_REG") (pin "6") (pinfunction "A5_6") (pintype "bidirectional"))
      (node (ref "SUBTRACT_INVRTR_LOWER_") (pin "2") (pinfunction "I1_2") (pintype "input"))
      (node (ref "SUBTRACT_INVRTR_UPPER_1") (pin "12") (pinfunction "I0_12") (pintype "input"))
    )
    (net (code "60") (name "Net-(ADDR_REG_CALC_LOWERA-Q2)") (class "Default")
      (node (ref "ADDR_REG_CALC_LOWER") (pin "4") (pinfunction "Q2_4") (pintype "tri_state"))
      (node (ref "AND_GATE1_") (pin "5") (pinfunction "I1_5") (pintype "input"))
      (node (ref "LED_B_REG_3") (pin "A") (pinfunction "A_A") (pintype "passive"))
      (node (ref "OR_GATE1") (pin "12") (pinfunction "I0_12") (pintype "input"))
      (node (ref "OUTPUT_BUFFER_CALC_REG") (pin "7") (pinfunction "A6_7") (pintype "bidirectional"))
      (node (ref "SUBTRACT_INVRTR_LOWER_") (pin "5") (pinfunction "I1_5") (pintype "input"))
      (node (ref "SUBTRACT_INVRTR_UPPER_1") (pin "9") (pinfunction "I0_9") (pintype "input"))
    )
    (net (code "61") (name "Net-(ADDR_REG_CALC_LOWERA-Q3)") (class "Default")
      (node (ref "ADDR_REG_CALC_LOWER") (pin "5") (pinfunction "Q3_5") (pintype "tri_state"))
      (node (ref "AND_GATE1_") (pin "2") (pinfunction "I1_2") (pintype "input"))
      (node (ref "LED_B_REG_2") (pin "A") (pinfunction "A_A") (pintype "passive"))
      (node (ref "OR_GATE1") (pin "9") (pinfunction "I0_9") (pintype "input"))
      (node (ref "OUTPUT_BUFFER_CALC_REG") (pin "8") (pinfunction "A7_8") (pintype "bidirectional"))
      (node (ref "SUBTRACT_INVRTR_LOWER_") (pin "10") (pinfunction "I1_10") (pintype "input"))
      (node (ref "SUBTRACT_INVRTR_UPPER_1") (pin "4") (pinfunction "I0_4") (pintype "input"))
    )
    (net (code "62") (name "Net-(ADDR_REG_CALC_LOWERA-Q4)") (class "Default")
      (node (ref "ADDR_REG_CALC_LOWER") (pin "6") (pinfunction "Q4_6") (pintype "tri_state"))
      (node (ref "AND_GATE_") (pin "13") (pinfunction "I1_13") (pintype "input"))
      (node (ref "LED_B_REG_1") (pin "A") (pinfunction "A_A") (pintype "passive"))
      (node (ref "OR_GATE1") (pin "5") (pinfunction "I1_5") (pintype "input"))
      (node (ref "OUTPUT_BUFFER_CALC_REG") (pin "9") (pinfunction "A8_9") (pintype "bidirectional"))
      (node (ref "SUBTRACT_INVRTR_LOWER_") (pin "13") (pinfunction "I1_13") (pintype "input"))
      (node (ref "SUBTRACT_INVRTR_UPPER_1") (pin "1") (pinfunction "I0_1") (pintype "input"))
    )
    (net (code "63") (name "Net-(ADDR_REG_CALC_UPPERA-Q1)") (class "Default")
      (node (ref "ADDR_REG_CALC_UPPER") (pin "3") (pinfunction "Q1_3") (pintype "tri_state"))
      (node (ref "AND_GATE2_") (pin "10") (pinfunction "I1_10") (pintype "input"))
      (node (ref "LED_B_REG_8") (pin "A") (pinfunction "A_A") (pintype "passive"))
      (node (ref "OR_GATE_2") (pin "1") (pinfunction "I0_1") (pintype "input"))
      (node (ref "OUTPUT_BUFFER_CALC_REG") (pin "2") (pinfunction "A1_2") (pintype "bidirectional"))
      (node (ref "SUBTRACT_INVRTR_LOWER_1") (pin "12") (pinfunction "I0_12") (pintype "input"))
      (node (ref "SUBTRACT_INVRTR_UPPER_") (pin "2") (pinfunction "I1_2") (pintype "input"))
    )
    (net (code "64") (name "Net-(ADDR_REG_CALC_UPPERA-Q2)") (class "Default")
      (node (ref "ADDR_REG_CALC_UPPER") (pin "4") (pinfunction "Q2_4") (pintype "tri_state"))
      (node (ref "AND_GATE2_") (pin "4") (pinfunction "I0_4") (pintype "input"))
      (node (ref "LED_B_REG_7") (pin "A") (pinfunction "A_A") (pintype "passive"))
      (node (ref "OR_GATE") (pin "13") (pinfunction "I1_13") (pintype "input"))
      (node (ref "OUTPUT_BUFFER_CALC_REG") (pin "3") (pinfunction "A2_3") (pintype "bidirectional"))
      (node (ref "SUBTRACT_INVRTR_LOWER_1") (pin "9") (pinfunction "I0_9") (pintype "input"))
      (node (ref "SUBTRACT_INVRTR_UPPER_") (pin "5") (pinfunction "I1_5") (pintype "input"))
    )
    (net (code "65") (name "Net-(ADDR_REG_CALC_UPPERA-Q3)") (class "Default")
      (node (ref "ADDR_REG_CALC_UPPER") (pin "5") (pinfunction "Q3_5") (pintype "tri_state"))
      (node (ref "AND_GATE2_") (pin "2") (pinfunction "I1_2") (pintype "input"))
      (node (ref "LED_B_REG_6") (pin "A") (pinfunction "A_A") (pintype "passive"))
      (node (ref "OR_GATE") (pin "9") (pinfunction "I0_9") (pintype "input"))
      (node (ref "OUTPUT_BUFFER_CALC_REG") (pin "4") (pinfunction "A3_4") (pintype "bidirectional"))
      (node (ref "SUBTRACT_INVRTR_LOWER_1") (pin "4") (pinfunction "I0_4") (pintype "input"))
      (node (ref "SUBTRACT_INVRTR_UPPER_") (pin "10") (pinfunction "I1_10") (pintype "input"))
    )
    (net (code "66") (name "Net-(ADDR_REG_CALC_UPPERA-Q4)") (class "Default")
      (node (ref "ADDR_REG_CALC_UPPER") (pin "6") (pinfunction "Q4_6") (pintype "tri_state"))
      (node (ref "AND_GATE1_") (pin "13") (pinfunction "I1_13") (pintype "input"))
      (node (ref "LED_B_REG_5") (pin "A") (pinfunction "A_A") (pintype "passive"))
      (node (ref "OR_GATE") (pin "4") (pinfunction "I0_4") (pintype "input"))
      (node (ref "OUTPUT_BUFFER_CALC_REG") (pin "5") (pinfunction "A4_5") (pintype "bidirectional"))
      (node (ref "SUBTRACT_INVRTR_LOWER_1") (pin "1") (pinfunction "I0_1") (pintype "input"))
      (node (ref "SUBTRACT_INVRTR_UPPER_") (pin "13") (pinfunction "I1_13") (pintype "input"))
    )
    (net (code "67") (name "Net-(ADDR_REG_PARAM_UPPERA-Q1)") (class "Default")
      (node (ref "ADDR_REG_PARAM_UPPER") (pin "3") (pinfunction "Q1_3") (pintype "tri_state"))
      (node (ref "OUTPUT_BUFFER_PARAM_REG") (pin "2") (pinfunction "A1_2") (pintype "bidirectional"))
      (node (ref "PARAM_LED_8") (pin "A") (pinfunction "A_A") (pintype "passive"))
    )
    (net (code "68") (name "Net-(ADDR_REG_PARAM_UPPERA-Q2)") (class "Default")
      (node (ref "ADDR_REG_PARAM_UPPER") (pin "4") (pinfunction "Q2_4") (pintype "tri_state"))
      (node (ref "OUTPUT_BUFFER_PARAM_REG") (pin "3") (pinfunction "A2_3") (pintype "bidirectional"))
      (node (ref "PARAM_LED_7") (pin "A") (pinfunction "A_A") (pintype "passive"))
    )
    (net (code "69") (name "Net-(ADDR_REG_PARAM_UPPERA-Q3)") (class "Default")
      (node (ref "ADDR_REG_PARAM_UPPER") (pin "5") (pinfunction "Q3_5") (pintype "tri_state"))
      (node (ref "OUTPUT_BUFFER_PARAM_REG") (pin "4") (pinfunction "A3_4") (pintype "bidirectional"))
      (node (ref "PARAM_LED_6") (pin "A") (pinfunction "A_A") (pintype "passive"))
    )
    (net (code "70") (name "Net-(ADDR_REG_PARAM_UPPERA-Q4)") (class "Default")
      (node (ref "ADDR_REG_PARAM_UPPER") (pin "6") (pinfunction "Q4_6") (pintype "tri_state"))
      (node (ref "OUTPUT_BUFFER_PARAM_REG") (pin "5") (pinfunction "A4_5") (pintype "bidirectional"))
      (node (ref "PARAM_LED_5") (pin "A") (pinfunction "A_A") (pintype "passive"))
    )
    (net (code "71") (name "Net-(AND_GATE1_A-O)") (class "Default")
      (node (ref "AND_GATE1_") (pin "3") (pinfunction "O_3") (pintype "output"))
      (node (ref "LOGIC_SELECTOR-AND/OR_LOWER") (pin "5") (pinfunction "2A_5") (pintype "input"))
    )
    (net (code "72") (name "Net-(AND_GATE1_B-O)") (class "Default")
      (node (ref "AND_GATE1_") (pin "6") (pinfunction "O_6") (pintype "output"))
      (node (ref "LOGIC_SELECTOR-AND/OR_LOWER") (pin "11") (pinfunction "3A_11") (pintype "input"))
    )
    (net (code "73") (name "Net-(AND_GATE1_C-O)") (class "Default")
      (node (ref "AND_GATE1_") (pin "8") (pinfunction "O_8") (pintype "output"))
      (node (ref "LOGIC_SELECTOR-AND/OR_LOWER") (pin "14") (pinfunction "4A_14") (pintype "input"))
    )
    (net (code "74") (name "Net-(AND_GATE1_D-O)") (class "Default")
      (node (ref "AND_GATE1_") (pin "11") (pinfunction "O_11") (pintype "output"))
      (node (ref "LOGIC_SELECTOR-AND/OR_UPPER") (pin "2") (pinfunction "1A_2") (pintype "input"))
    )
    (net (code "75") (name "Net-(AND_GATE2_A-O)") (class "Default")
      (node (ref "AND_GATE2_") (pin "3") (pinfunction "O_3") (pintype "output"))
      (node (ref "LOGIC_SELECTOR-AND/OR_UPPER") (pin "5") (pinfunction "2A_5") (pintype "input"))
    )
    (net (code "76") (name "Net-(AND_GATE2_B-O)") (class "Default")
      (node (ref "AND_GATE2_") (pin "6") (pinfunction "O_6") (pintype "output"))
      (node (ref "LOGIC_SELECTOR-AND/OR_UPPER") (pin "11") (pinfunction "3A_11") (pintype "input"))
    )
    (net (code "77") (name "Net-(AND_GATE2_C-O)") (class "Default")
      (node (ref "AND_GATE2_") (pin "8") (pinfunction "O_8") (pintype "output"))
      (node (ref "LOGIC_SELECTOR-AND/OR_UPPER") (pin "14") (pinfunction "4A_14") (pintype "input"))
    )
    (net (code "78") (name "Net-(AND_GATE2_D-I0)") (class "Default")
      (node (ref "AND_GATE2_") (pin "12") (pinfunction "I0_12") (pintype "input"))
      (node (ref "SELECTOR_LOGIC_") (pin "4") (pinfunction "Y0_4") (pintype "output"))
    )
    (net (code "79") (name "Net-(AND_GATE2_D-I1)") (class "Default")
      (node (ref "AND_GATE2_") (pin "13") (pinfunction "I1_13") (pintype "input"))
      (node (ref "SELECTOR_LOGIC_") (pin "5") (pinfunction "Y1_5") (pintype "output"))
    )
    (net (code "80") (name "Net-(AND_GATE2_D-O)") (class "Default")
      (node (ref "AND_GATE2_") (pin "11") (pinfunction "O_11") (pintype "output"))
      (node (ref "LOGIC_SELECTOR-AND/OR_LOWER") (pin "15") (pinfunction "G_15") (pintype "input"))
      (node (ref "LOGIC_SELECTOR-AND/OR_UPPER") (pin "15") (pinfunction "G_15") (pintype "input"))
    )
    (net (code "81") (name "Net-(AND_GATE3_A-I0)") (class "Default")
      (node (ref "AND_GATE3_") (pin "1") (pinfunction "I0_1") (pintype "input"))
      (node (ref "SELECTOR_LOGIC_") (pin "6") (pinfunction "Y2_6") (pintype "output"))
    )
    (net (code "82") (name "Net-(AND_GATE3_A-I1)") (class "Default")
      (node (ref "AND_GATE3_") (pin "2") (pinfunction "I1_2") (pintype "input"))
      (node (ref "SELECTOR_LOGIC_") (pin "7") (pinfunction "Y3_7") (pintype "output"))
    )
    (net (code "83") (name "Net-(AND_GATE3_A-O)") (class "Default")
      (node (ref "AND_GATE3_") (pin "3") (pinfunction "O_3") (pintype "output"))
      (node (ref "LOGIC_SELECTOR-XOR/NOT_LOWER") (pin "15") (pinfunction "G_15") (pintype "input"))
      (node (ref "LOGIC_SELECTOR-XOR/NOT_UPPER") (pin "15") (pinfunction "G_15") (pintype "input"))
    )
    (net (code "84") (name "Net-(AND_GATE3_B-I1)") (class "Default")
      (node (ref "AND_GATE3_") (pin "5") (pinfunction "I1_5") (pintype "input"))
      (node (ref "NOT_GATE4_") (pin "12") (pinfunction "O_12") (pintype "output"))
    )
    (net (code "85") (name "Net-(AND_GATE3_B-O)") (class "Default")
      (node (ref "AND_GATE3_") (pin "6") (pinfunction "O_6") (pintype "output"))
      (node (ref "NOT_GATE4_") (pin "9") (pinfunction "I_9") (pintype "input"))
    )
    (net (code "86") (name "Net-(AND_GATE3_C-I1)") (class "Default")
      (node (ref "AND_GATE3_") (pin "10") (pinfunction "I1_10") (pintype "input"))
      (node (ref "NOT_GATE5_") (pin "2") (pinfunction "O_2") (pintype "output"))
    )
    (net (code "87") (name "Net-(AND_GATE3_C-O)") (class "Default")
      (node (ref "AND_GATE3_") (pin "8") (pinfunction "O_8") (pintype "output"))
      (node (ref "NOT_GATE4_") (pin "5") (pinfunction "I_5") (pintype "input"))
    )
    (net (code "88") (name "Net-(AND_GATE3_D-I0)") (class "Default")
      (node (ref "AND_GATE3_") (pin "12") (pinfunction "I0_12") (pintype "input"))
      (node (ref "NOT_GATE2_") (pin "8") (pinfunction "O_8") (pintype "output"))
    )
    (net (code "89") (name "Net-(AND_GATE4_A-I0)") (class "Default")
      (node (ref "AND_GATE4_") (pin "1") (pinfunction "I0_1") (pintype "input"))
      (node (ref "NOT_GATE2_") (pin "6") (pinfunction "O_6") (pintype "output"))
    )
    (net (code "90") (name "Net-(AND_GATE4_A-I1)") (class "Default")
      (node (ref "AND_GATE4_") (pin "2") (pinfunction "I1_2") (pintype "input"))
      (node (ref "ZERO_FLAG") (pin "A") (pinfunction "A_A") (pintype "passive"))
      (node (ref "ZERO_POS_FLAG_IDENTIFIER") (pin "13") (pinfunction "W_13") (pintype "output"))
    )
    (net (code "91") (name "Net-(AND_GATE4_B-I0)") (class "Default")
      (node (ref "AND_GATE4_") (pin "4") (pinfunction "I0_4") (pintype "input"))
      (node (ref "NOT_GATE3_") (pin "2") (pinfunction "O_2") (pintype "output"))
    )
    (net (code "92") (name "Net-(AND_GATE4_B-I1)") (class "Default")
      (node (ref "AND_GATE4_") (pin "5") (pinfunction "I1_5") (pintype "input"))
      (node (ref "POSITIVE_FLAG") (pin "A") (pinfunction "A_A") (pintype "passive"))
      (node (ref "ZERO_POS_FLAG_IDENTIFIER") (pin "1") (pinfunction "Y_1") (pintype "output"))
    )
    (net (code "93") (name "Net-(AND_GATE4_C-I0)") (class "Default")
      (node (ref "AND_GATE4_") (pin "9") (pinfunction "I0_9") (pintype "input"))
      (node (ref "SELECTOR_LOGIC2_") (pin "9") (pinfunction "Y3_9") (pintype "output"))
    )
    (net (code "94") (name "Net-(AND_GATE4_C-I1)") (class "Default")
      (node (ref "AND_GATE4_") (pin "10") (pinfunction "I1_10") (pintype "input"))
      (node (ref "KILL_SWITCH") (pin "2") (pinfunction "2_2") (pintype "passive"))
    )
    (net (code "95") (name "Net-(AND_GATE4_C-O)") (class "Default")
      (node (ref "AND_GATE4_") (pin "8") (pinfunction "O_8") (pintype "output"))
      (node (ref "MICRO_COUNTER_LOWER") (pin "1") (pinfunction "1_1") (pintype "passive"))
      (node (ref "MICRO_COUNTER_UPPER") (pin "1") (pinfunction "1_1") (pintype "passive"))
      (node (ref "PROGRAM_COUNTER_LOWER") (pin "1") (pinfunction "1_1") (pintype "passive"))
      (node (ref "PROGRAM_COUNTER_UPPER") (pin "1") (pinfunction "1_1") (pintype "passive"))
    )
    (net (code "96") (name "Net-(AND_GATE_A-I0)") (class "Default")
      (node (ref "AND_GATE_") (pin "1") (pinfunction "I0_1") (pintype "input"))
      (node (ref "AUTO_CLOCK") (pin "3") (pinfunction "Q_3") (pintype "output"))
    )
    (net (code "97") (name "Net-(AND_GATE_A-I1)") (class "Default")
      (node (ref "AND_GATE_") (pin "2") (pinfunction "I1_2") (pintype "input"))
      (node (ref "NOT_GATE1") (pin "4") (pinfunction "O_4") (pintype "output"))
    )
    (net (code "98") (name "Net-(AND_GATE_A-O)") (class "Default")
      (node (ref "AND_GATE_") (pin "3") (pinfunction "O_3") (pintype "output"))
      (node (ref "OR_GATE1") (pin "1") (pinfunction "I0_1") (pintype "input"))
    )
    (net (code "99") (name "Net-(AND_GATE_B-I0)") (class "Default")
      (node (ref "AND_GATE_") (pin "4") (pinfunction "I0_4") (pintype "input"))
      (node (ref "CLK_MODE") (pin "1") (pinfunction "1_1") (pintype "passive"))
      (node (ref "NOT_GATE1") (pin "3") (pinfunction "I_3") (pintype "input"))
      (node (ref "R4") (pin "2") (pinfunction "2_2") (pintype "passive"))
    )
    (net (code "100") (name "Net-(AND_GATE_B-I1)") (class "Default")
      (node (ref "AND_GATE_") (pin "5") (pinfunction "I1_5") (pintype "input"))
      (node (ref "STEPPER_CLOCK") (pin "3") (pinfunction "Q_3") (pintype "output"))
    )
    (net (code "101") (name "Net-(AND_GATE_B-O)") (class "Default")
      (node (ref "AND_GATE_") (pin "6") (pinfunction "O_6") (pintype "output"))
      (node (ref "OR_GATE1") (pin "2") (pinfunction "I1_2") (pintype "input"))
    )
    (net (code "102") (name "Net-(AND_GATE_C-I0)") (class "Default")
      (node (ref "AND_GATE_") (pin "9") (pinfunction "I0_9") (pintype "input"))
      (node (ref "NOT_GATE1") (pin "2") (pinfunction "O_2") (pintype "output"))
    )
    (net (code "103") (name "Net-(AND_GATE_C-I1)") (class "Default")
      (node (ref "AND_GATE_") (pin "10") (pinfunction "I1_10") (pintype "input"))
      (node (ref "OR_GATE1") (pin "3") (pinfunction "O_3") (pintype "output"))
    )
    (net (code "104") (name "Net-(AND_GATE_D-O)") (class "Default")
      (node (ref "AND_GATE_") (pin "11") (pinfunction "O_11") (pintype "output"))
      (node (ref "LOGIC_SELECTOR-AND/OR_LOWER") (pin "2") (pinfunction "1A_2") (pintype "input"))
    )
    (net (code "105") (name "Net-(AUTO_CLOCK-DIS)") (class "Default")
      (node (ref "AUTO_CLOCK") (pin "7") (pinfunction "DIS_7") (pintype "input"))
      (node (ref "FREQUENCY") (pin "E") (pinfunction "E_E") (pintype "passive"))
      (node (ref "R1") (pin "2") (pinfunction "2_2") (pintype "passive"))
    )
    (net (code "106") (name "Net-(AUTO_CLOCK-THR)") (class "Default")
      (node (ref "AUTO_CLOCK") (pin "2") (pinfunction "TR_2") (pintype "input"))
      (node (ref "AUTO_CLOCK") (pin "6") (pinfunction "THR_6") (pintype "input"))
      (node (ref "C1") (pin "+") (pinfunction "+_+") (pintype "passive"))
      (node (ref "R7") (pin "2") (pinfunction "2_2") (pintype "passive"))
    )
    (net (code "107") (name "Net-(BRANCH_SELECTORA-A)") (class "Default")
      (node (ref "BRANCH_SELECTOR") (pin "2") (pinfunction "A_2") (pintype "input"))
      (node (ref "INSTRUCTION_MEMORY_UPPER2") (pin "19") (pinfunction "19_19") (pintype "passive"))
    )
    (net (code "108") (name "Net-(BRANCH_SELECTORA-B)") (class "Default")
      (node (ref "BRANCH_SELECTOR") (pin "3") (pinfunction "B_3") (pintype "input"))
      (node (ref "INSTRUCTION_MEMORY_UPPER2") (pin "18") (pinfunction "18_18") (pintype "passive"))
    )
    (net (code "109") (name "Net-(BRANCH_SELECTORA-Y0)") (class "Default")
      (node (ref "BRANCH_SELECTOR") (pin "4") (pinfunction "Y0_4") (pintype "output"))
      (node (ref "NOT_GATE4_") (pin "1") (pinfunction "I_1") (pintype "input"))
    )
    (net (code "110") (name "Net-(BRANCH_SELECTORA-Y1)") (class "Default")
      (node (ref "BRANCH_SELECTOR") (pin "5") (pinfunction "Y1_5") (pintype "output"))
      (node (ref "NOT_GATE2_") (pin "9") (pinfunction "I_9") (pintype "input"))
    )
    (net (code "111") (name "Net-(BRANCH_SELECTORA-Y2)") (class "Default")
      (node (ref "BRANCH_SELECTOR") (pin "6") (pinfunction "Y2_6") (pintype "output"))
      (node (ref "NOT_GATE2_") (pin "5") (pinfunction "I_5") (pintype "input"))
    )
    (net (code "112") (name "Net-(BRANCH_SELECTORA-Y3)") (class "Default")
      (node (ref "BRANCH_SELECTOR") (pin "7") (pinfunction "Y3_7") (pintype "output"))
      (node (ref "NOT_GATE3_") (pin "1") (pinfunction "I_1") (pintype "input"))
    )
    (net (code "113") (name "Net-(BRANCH_SELECTORB-A)") (class "Default")
      (node (ref "BRANCH_SELECTOR") (pin "14") (pinfunction "A_14") (pintype "input"))
      (node (ref "INSRUCTION_REGISTER_SELECTOR_LOWER") (pin "4") (pinfunction "1Y_4") (pintype "output"))
    )
    (net (code "114") (name "Net-(BRANCH_SELECTORB-B)") (class "Default")
      (node (ref "BRANCH_SELECTOR") (pin "13") (pinfunction "B_13") (pintype "input"))
      (node (ref "INSRUCTION_REGISTER_SELECTOR_LOWER") (pin "7") (pinfunction "2Y_7") (pintype "output"))
    )
    (net (code "115") (name "Net-(BRANCH_SELECTORB-Y1)") (class "Default")
      (node (ref "BRANCH_SELECTOR") (pin "11") (pinfunction "Y1_11") (pintype "output"))
      (node (ref "OUTPUT_BUFFER_REG_A") (pin "19") (pinfunction "G_19") (pintype "input"))
    )
    (net (code "116") (name "Net-(BRANCH_SELECTORB-Y3)") (class "Default")
      (node (ref "BRANCH_SELECTOR") (pin "9") (pinfunction "Y3_9") (pintype "output"))
      (node (ref "NOT_GATE4_") (pin "13") (pinfunction "I_13") (pintype "input"))
    )
    (net (code "117") (name "Net-(CLK_TRIGGER-S)") (class "Default")
      (node (ref "CLK_TRIGGER") (pin "1") (pinfunction "S_1") (pintype "passive"))
      (node (ref "CLK_TRIGGER") (pin "2") (pinfunction "S1_2") (pintype "passive"))
      (node (ref "R2") (pin "2") (pinfunction "2_2") (pintype "passive"))
      (node (ref "STEPPER_CLOCK") (pin "2") (pinfunction "TR_2") (pintype "input"))
    )
    (net (code "118") (name "Net-(CLOCK-C)") (class "Default")
      (node (ref "CLOCK") (pin "K") (pinfunction "C_K") (pintype "passive"))
      (node (ref "R5") (pin "2") (pinfunction "2_2") (pintype "passive"))
    )
    (net (code "119") (name "Net-(DATABUS_1-C)") (class "Default")
      (node (ref "DATABUS_1") (pin "K") (pinfunction "C_K") (pintype "passive"))
      (node (ref "R24") (pin "1") (pinfunction "1_1") (pintype "passive"))
    )
    (net (code "120") (name "Net-(DATABUS_2-C)") (class "Default")
      (node (ref "DATABUS_2") (pin "K") (pinfunction "C_K") (pintype "passive"))
      (node (ref "R25") (pin "1") (pinfunction "1_1") (pintype "passive"))
    )
    (net (code "121") (name "Net-(DATABUS_3-C)") (class "Default")
      (node (ref "DATABUS_3") (pin "K") (pinfunction "C_K") (pintype "passive"))
      (node (ref "R26") (pin "1") (pinfunction "1_1") (pintype "passive"))
    )
    (net (code "122") (name "Net-(DATABUS_4-C)") (class "Default")
      (node (ref "DATABUS_4") (pin "K") (pinfunction "C_K") (pintype "passive"))
      (node (ref "R27") (pin "1") (pinfunction "1_1") (pintype "passive"))
    )
    (net (code "123") (name "Net-(DATABUS_5-C)") (class "Default")
      (node (ref "DATABUS_5") (pin "K") (pinfunction "C_K") (pintype "passive"))
      (node (ref "R28") (pin "1") (pinfunction "1_1") (pintype "passive"))
    )
    (net (code "124") (name "Net-(DATABUS_6-C)") (class "Default")
      (node (ref "DATABUS_6") (pin "K") (pinfunction "C_K") (pintype "passive"))
      (node (ref "R29") (pin "1") (pinfunction "1_1") (pintype "passive"))
    )
    (net (code "125") (name "Net-(DATABUS_7-C)") (class "Default")
      (node (ref "DATABUS_7") (pin "K") (pinfunction "C_K") (pintype "passive"))
      (node (ref "R30") (pin "1") (pinfunction "1_1") (pintype "passive"))
    )
    (net (code "126") (name "Net-(DATABUS_8-C)") (class "Default")
      (node (ref "DATABUS_8") (pin "K") (pinfunction "C_K") (pintype "passive"))
      (node (ref "R31") (pin "1") (pinfunction "1_1") (pintype "passive"))
    )
    (net (code "127") (name "Net-(FLAG_1-C)") (class "Default")
      (node (ref "FLAG_1") (pin "K") (pinfunction "C_K") (pintype "passive"))
      (node (ref "R15") (pin "2") (pinfunction "2_2") (pintype "passive"))
    )
    (net (code "128") (name "Net-(FLAG_2-C)") (class "Default")
      (node (ref "FLAG_2") (pin "K") (pinfunction "C_K") (pintype "passive"))
      (node (ref "R77") (pin "2") (pinfunction "2_2") (pintype "passive"))
    )
    (net (code "129") (name "Net-(FLAG_3-C)") (class "Default")
      (node (ref "FLAG_3") (pin "K") (pinfunction "C_K") (pintype "passive"))
      (node (ref "R78") (pin "2") (pinfunction "2_2") (pintype "passive"))
    )
    (net (code "130") (name "Net-(FLAG_4-C)") (class "Default")
      (node (ref "FLAG_4") (pin "K") (pinfunction "C_K") (pintype "passive"))
      (node (ref "R79") (pin "2") (pinfunction "2_2") (pintype "passive"))
    )
    (net (code "131") (name "Net-(FLAG_5-C)") (class "Default")
      (node (ref "FLAG_5") (pin "K") (pinfunction "C_K") (pintype "passive"))
      (node (ref "R11") (pin "2") (pinfunction "2_2") (pintype "passive"))
    )
    (net (code "132") (name "Net-(FLAG_6-C)") (class "Default")
      (node (ref "FLAG_6") (pin "K") (pinfunction "C_K") (pintype "passive"))
      (node (ref "R10") (pin "2") (pinfunction "2_2") (pintype "passive"))
    )
    (net (code "133") (name "Net-(FLAG_7-C)") (class "Default")
      (node (ref "FLAG_7") (pin "K") (pinfunction "C_K") (pintype "passive"))
      (node (ref "R9") (pin "2") (pinfunction "2_2") (pintype "passive"))
    )
    (net (code "134") (name "Net-(FLAG_8-C)") (class "Default")
      (node (ref "FLAG_8") (pin "K") (pinfunction "C_K") (pintype "passive"))
      (node (ref "R8") (pin "2") (pinfunction "2_2") (pintype "passive"))
    )
    (net (code "135") (name "Net-(FLAG_REG_LOWERA-D2)") (class "Default")
      (node (ref "FLAG_REG_LOWER") (pin "13") (pinfunction "D2_13") (pintype "input"))
      (node (ref "XOR_GATE_2") (pin "8") (pinfunction "O_8") (pintype "output"))
    )
    (net (code "136") (name "Net-(FLAG_REG_LOWERA-D3)") (class "Default")
      (node (ref "FLAG_REG_LOWER") (pin "12") (pinfunction "D3_12") (pintype "input"))
      (node (ref "XOR_GATE_2") (pin "6") (pinfunction "O_6") (pintype "output"))
    )
    (net (code "137") (name "Net-(FLAG_REG_LOWERA-D4)") (class "Default")
      (node (ref "FLAG_REG_LOWER") (pin "11") (pinfunction "D4_11") (pintype "input"))
      (node (ref "XOR_GATE_2") (pin "3") (pinfunction "O_3") (pintype "output"))
    )
    (net (code "138") (name "Net-(FLAG_REG_LOWERA-G1)") (class "Default")
      (node (ref "FLAG_REG_LOWER") (pin "10") (pinfunction "G2_10") (pintype "input"))
      (node (ref "FLAG_REG_LOWER") (pin "9") (pinfunction "G1_9") (pintype "input"))
      (node (ref "FLAG_REG_UPPER") (pin "10") (pinfunction "G2_10") (pintype "input"))
      (node (ref "FLAG_REG_UPPER") (pin "9") (pinfunction "G1_9") (pintype "input"))
      (node (ref "NOT_GATE1") (pin "12") (pinfunction "O_12") (pintype "output"))
    )
    (net (code "139") (name "Net-(FLAG_REG_LOWERA-Q1)") (class "Default")
      (node (ref "FLAG_8") (pin "A") (pinfunction "A_A") (pintype "passive"))
      (node (ref "FLAG_REG_LOWER") (pin "3") (pinfunction "Q1_3") (pintype "tri_state"))
      (node (ref "OUTPUT_BUFFER_FLAGS") (pin "11") (pinfunction "B8_11") (pintype "bidirectional"))
    )
    (net (code "140") (name "Net-(FLAG_REG_LOWERA-Q2)") (class "Default")
      (node (ref "FLAG_7") (pin "A") (pinfunction "A_A") (pintype "passive"))
      (node (ref "FLAG_REG_LOWER") (pin "4") (pinfunction "Q2_4") (pintype "tri_state"))
      (node (ref "OUTPUT_BUFFER_FLAGS") (pin "12") (pinfunction "B7_12") (pintype "bidirectional"))
      (node (ref "XOR_GATE_2") (pin "9") (pinfunction "I0_9") (pintype "input"))
    )
    (net (code "141") (name "Net-(FLAG_REG_LOWERA-Q3)") (class "Default")
      (node (ref "FLAG_6") (pin "A") (pinfunction "A_A") (pintype "passive"))
      (node (ref "FLAG_REG_LOWER") (pin "5") (pinfunction "Q3_5") (pintype "tri_state"))
      (node (ref "OUTPUT_BUFFER_FLAGS") (pin "13") (pinfunction "B6_13") (pintype "bidirectional"))
      (node (ref "XOR_GATE_2") (pin "4") (pinfunction "I0_4") (pintype "input"))
    )
    (net (code "142") (name "Net-(FLAG_REG_LOWERA-Q4)") (class "Default")
      (node (ref "FLAG_5") (pin "A") (pinfunction "A_A") (pintype "passive"))
      (node (ref "FLAG_REG_LOWER") (pin "6") (pinfunction "Q4_6") (pintype "tri_state"))
      (node (ref "OUTPUT_BUFFER_FLAGS") (pin "14") (pinfunction "B5_14") (pintype "bidirectional"))
      (node (ref "XOR_GATE_2") (pin "1") (pinfunction "I0_1") (pintype "input"))
    )
    (net (code "143") (name "Net-(FLAG_REG_UPPERA-D1)") (class "Default")
      (node (ref "FLAG_REG_UPPER") (pin "14") (pinfunction "D1_14") (pintype "input"))
      (node (ref "XOR_GATE_1") (pin "11") (pinfunction "O_11") (pintype "output"))
    )
    (net (code "144") (name "Net-(FLAG_REG_UPPERA-D2)") (class "Default")
      (node (ref "FLAG_REG_UPPER") (pin "13") (pinfunction "D2_13") (pintype "input"))
      (node (ref "XOR_GATE_1") (pin "8") (pinfunction "O_8") (pintype "output"))
    )
    (net (code "145") (name "Net-(FLAG_REG_UPPERA-D3)") (class "Default")
      (node (ref "FLAG_REG_UPPER") (pin "12") (pinfunction "D3_12") (pintype "input"))
      (node (ref "XOR_GATE_1") (pin "6") (pinfunction "O_6") (pintype "output"))
    )
    (net (code "146") (name "Net-(FLAG_REG_UPPERA-D4)") (class "Default")
      (node (ref "FLAG_REG_UPPER") (pin "11") (pinfunction "D4_11") (pintype "input"))
      (node (ref "XOR_GATE_1") (pin "3") (pinfunction "O_3") (pintype "output"))
    )
    (net (code "147") (name "Net-(FLAG_REG_UPPERA-Q1)") (class "Default")
      (node (ref "FLAG_4") (pin "A") (pinfunction "A_A") (pintype "passive"))
      (node (ref "FLAG_REG_UPPER") (pin "3") (pinfunction "Q1_3") (pintype "tri_state"))
      (node (ref "OUTPUT_BUFFER_FLAGS") (pin "15") (pinfunction "B4_15") (pintype "bidirectional"))
      (node (ref "XOR_GATE_1") (pin "12") (pinfunction "I0_12") (pintype "input"))
    )
    (net (code "148") (name "Net-(FLAG_REG_UPPERA-Q2)") (class "Default")
      (node (ref "FLAG_3") (pin "A") (pinfunction "A_A") (pintype "passive"))
      (node (ref "FLAG_REG_UPPER") (pin "4") (pinfunction "Q2_4") (pintype "tri_state"))
      (node (ref "OUTPUT_BUFFER_FLAGS") (pin "16") (pinfunction "B3_16") (pintype "bidirectional"))
      (node (ref "XOR_GATE_1") (pin "9") (pinfunction "I0_9") (pintype "input"))
    )
    (net (code "149") (name "Net-(FLAG_REG_UPPERA-Q3)") (class "Default")
      (node (ref "FLAG_2") (pin "A") (pinfunction "A_A") (pintype "passive"))
      (node (ref "FLAG_REG_UPPER") (pin "5") (pinfunction "Q3_5") (pintype "tri_state"))
      (node (ref "OUTPUT_BUFFER_FLAGS") (pin "17") (pinfunction "B2_17") (pintype "bidirectional"))
      (node (ref "XOR_GATE_1") (pin "4") (pinfunction "I0_4") (pintype "input"))
    )
    (net (code "150") (name "Net-(FLAG_REG_UPPERA-Q4)") (class "Default")
      (node (ref "FLAG_1") (pin "A") (pinfunction "A_A") (pintype "passive"))
      (node (ref "FLAG_REG_UPPER") (pin "6") (pinfunction "Q4_6") (pintype "tri_state"))
      (node (ref "MEMORY") (pin "25") (pinfunction "25_25") (pintype "passive"))
      (node (ref "OUTPUT_BUFFER_FLAGS") (pin "18") (pinfunction "B1_18") (pintype "bidirectional"))
      (node (ref "XOR_GATE_1") (pin "1") (pinfunction "I0_1") (pintype "input"))
    )
    (net (code "151") (name "Net-(FREQUENCY-PadS)") (class "Default")
      (node (ref "FREQUENCY") (pin "S") (pinfunction "S_S") (pintype "passive"))
      (node (ref "R7") (pin "1") (pinfunction "1_1") (pintype "passive"))
    )
    (net (code "152") (name "Net-(INSRUCTION_REGISTER_SELECTOR_LOWERA-1B)") (class "Default")
      (node (ref "INSRUCTION_REGISTER_SELECTOR_LOWER") (pin "3") (pinfunction "1B_3") (pintype "input"))
      (node (ref "INSTRUCTION_MEMORY_LOWER") (pin "15") (pinfunction "15_15") (pintype "passive"))
      (node (ref "OUTPUT_BUFFER_INSTRUCTION") (pin "5") (pinfunction "A4_5") (pintype "bidirectional"))
    )
    (net (code "153") (name "Net-(INSRUCTION_REGISTER_SELECTOR_LOWERA-2B)") (class "Default")
      (node (ref "INSRUCTION_REGISTER_SELECTOR_LOWER") (pin "6") (pinfunction "2B_6") (pintype "input"))
      (node (ref "INSTRUCTION_MEMORY_LOWER") (pin "13") (pinfunction "13_13") (pintype "passive"))
      (node (ref "OUTPUT_BUFFER_INSTRUCTION") (pin "4") (pinfunction "A3_4") (pintype "bidirectional"))
    )
    (net (code "154") (name "Net-(INSRUCTION_REGISTER_SELECTOR_LOWERA-3B)") (class "Default")
      (node (ref "INSRUCTION_REGISTER_SELECTOR_LOWER") (pin "10") (pinfunction "3B_10") (pintype "input"))
      (node (ref "INSTRUCTION_MEMORY_LOWER") (pin "12") (pinfunction "12_12") (pintype "passive"))
      (node (ref "OUTPUT_BUFFER_INSTRUCTION") (pin "3") (pinfunction "A2_3") (pintype "bidirectional"))
    )
    (net (code "155") (name "Net-(INSRUCTION_REGISTER_SELECTOR_LOWERA-3Y)") (class "Default")
      (node (ref "INSRUCTION_REGISTER_SELECTOR_LOWER") (pin "9") (pinfunction "3Y_9") (pintype "output"))
      (node (ref "NOT_GATE1") (pin "9") (pinfunction "I_9") (pintype "input"))
    )
    (net (code "156") (name "Net-(INSRUCTION_REGISTER_SELECTOR_LOWERA-4B)") (class "Default")
      (node (ref "INSRUCTION_REGISTER_SELECTOR_LOWER") (pin "13") (pinfunction "4B_13") (pintype "input"))
      (node (ref "INSTRUCTION_MEMORY_LOWER") (pin "11") (pinfunction "11_11") (pintype "passive"))
      (node (ref "OUTPUT_BUFFER_INSTRUCTION") (pin "2") (pinfunction "A1_2") (pintype "bidirectional"))
    )
    (net (code "157") (name "Net-(INSRUCTION_REGISTER_SELECTOR_LOWERA-4Y)") (class "Default")
      (node (ref "INSRUCTION_REGISTER_SELECTOR_LOWER") (pin "12") (pinfunction "4Y_12") (pintype "output"))
      (node (ref "NOT_GATE1") (pin "5") (pinfunction "I_5") (pintype "input"))
    )
    (net (code "158") (name "Net-(INSRUCTION_REGISTER_SELECTOR_LOWERA-~{A}{slash}B)") (class "Default")
      (node (ref "INSRUCTION_REGISTER_SELECTOR_LOWER") (pin "1") (pinfunction "~{A}/B_1") (pintype "input"))
      (node (ref "INSRUCTION_REGISTER_SELECTOR_UPPER") (pin "1") (pinfunction "~{A}/B_1") (pintype "input"))
      (node (ref "OUTPUT_BUFFER_INSTRUCTION") (pin "19") (pinfunction "G_19") (pintype "input"))
      (node (ref "SELECTOR_LOGIC2_") (pin "6") (pinfunction "Y2_6") (pintype "output"))
    )
    (net (code "159") (name "Net-(INSRUCTION_REGISTER_SELECTOR_UPPERA-1B)") (class "Default")
      (node (ref "INSRUCTION_REGISTER_SELECTOR_UPPER") (pin "3") (pinfunction "1B_3") (pintype "input"))
      (node (ref "INSTRUCTION_MEMORY_LOWER") (pin "19") (pinfunction "19_19") (pintype "passive"))
      (node (ref "OUTPUT_BUFFER_INSTRUCTION") (pin "9") (pinfunction "A8_9") (pintype "bidirectional"))
    )
    (net (code "160") (name "Net-(INSRUCTION_REGISTER_SELECTOR_UPPERA-1Y)") (class "Default")
      (node (ref "INSRUCTION_REGISTER_SELECTOR_UPPER") (pin "4") (pinfunction "1Y_4") (pintype "output"))
      (node (ref "NOT_GATE4_") (pin "3") (pinfunction "I_3") (pintype "input"))
    )
    (net (code "161") (name "Net-(INSRUCTION_REGISTER_SELECTOR_UPPERA-2B)") (class "Default")
      (node (ref "INSRUCTION_REGISTER_SELECTOR_UPPER") (pin "6") (pinfunction "2B_6") (pintype "input"))
      (node (ref "INSTRUCTION_MEMORY_LOWER") (pin "18") (pinfunction "18_18") (pintype "passive"))
      (node (ref "OUTPUT_BUFFER_INSTRUCTION") (pin "8") (pinfunction "A7_8") (pintype "bidirectional"))
    )
    (net (code "162") (name "Net-(INSRUCTION_REGISTER_SELECTOR_UPPERA-2Y)") (class "Default")
      (node (ref "INSRUCTION_REGISTER_SELECTOR_UPPER") (pin "7") (pinfunction "2Y_7") (pintype "output"))
      (node (ref "NOT_GATE2_") (pin "13") (pinfunction "I_13") (pintype "input"))
      (node (ref "RAM") (pin "22") (pinfunction "22_22") (pintype "passive"))
    )
    (net (code "163") (name "Net-(INSRUCTION_REGISTER_SELECTOR_UPPERA-3B)") (class "Default")
      (node (ref "INSRUCTION_REGISTER_SELECTOR_UPPER") (pin "10") (pinfunction "3B_10") (pintype "input"))
      (node (ref "INSTRUCTION_MEMORY_LOWER") (pin "17") (pinfunction "17_17") (pintype "passive"))
      (node (ref "OUTPUT_BUFFER_INSTRUCTION") (pin "7") (pinfunction "A6_7") (pintype "bidirectional"))
    )
    (net (code "164") (name "Net-(INSRUCTION_REGISTER_SELECTOR_UPPERA-3Y)") (class "Default")
      (node (ref "INSRUCTION_REGISTER_SELECTOR_UPPER") (pin "9") (pinfunction "3Y_9") (pintype "output"))
      (node (ref "SELECTOR_LOGIC_") (pin "14") (pinfunction "A_14") (pintype "input"))
    )
    (net (code "165") (name "Net-(INSRUCTION_REGISTER_SELECTOR_UPPERA-4B)") (class "Default")
      (node (ref "INSRUCTION_REGISTER_SELECTOR_UPPER") (pin "13") (pinfunction "4B_13") (pintype "input"))
      (node (ref "INSTRUCTION_MEMORY_LOWER") (pin "16") (pinfunction "16_16") (pintype "passive"))
      (node (ref "OUTPUT_BUFFER_INSTRUCTION") (pin "6") (pinfunction "A5_6") (pintype "bidirectional"))
    )
    (net (code "166") (name "Net-(INSRUCTION_REGISTER_SELECTOR_UPPERA-4Y)") (class "Default")
      (node (ref "INSRUCTION_REGISTER_SELECTOR_UPPER") (pin "12") (pinfunction "4Y_12") (pintype "output"))
      (node (ref "SELECTOR_LOGIC_") (pin "13") (pinfunction "B_13") (pintype "input"))
    )
    (net (code "167") (name "Net-(INSTRUCTIONS_EXTENSIONB-1)") (class "Default")
      (node (ref "INSTRUCTIONS_EXTENSION") (pin "10") (pinfunction "1_10") (pintype "passive"))
      (node (ref "INSTRUCTION_MEMORY_LOWER") (pin "24") (pinfunction "24_24") (pintype "passive"))
      (node (ref "INSTRUCTION_MEMORY_UPPER") (pin "24") (pinfunction "24_24") (pintype "passive"))
      (node (ref "INSTRUCTION_MEMORY_UPPER2") (pin "24") (pinfunction "24_24") (pintype "passive"))
      (node (ref "MICRO_COUNTER_LOWER") (pin "13") (pinfunction "13_13") (pintype "passive"))
      (node (ref "USTEP_2") (pin "A") (pinfunction "A_A") (pintype "passive"))
    )
    (net (code "168") (name "Net-(INSTRUCTIONS_EXTENSIONC-1)") (class "Default")
      (node (ref "INSTRUCTIONS_EXTENSION") (pin "11") (pinfunction "1_11") (pintype "passive"))
      (node (ref "INSTRUCTION_MEMORY_LOWER") (pin "21") (pinfunction "21_21") (pintype "passive"))
      (node (ref "INSTRUCTION_MEMORY_UPPER") (pin "21") (pinfunction "21_21") (pintype "passive"))
      (node (ref "INSTRUCTION_MEMORY_UPPER2") (pin "21") (pinfunction "21_21") (pintype "passive"))
      (node (ref "MICRO_COUNTER_LOWER") (pin "12") (pinfunction "12_12") (pintype "passive"))
      (node (ref "USTEP_4") (pin "A") (pinfunction "A_A") (pintype "passive"))
    )
    (net (code "169") (name "Net-(INSTRUCTIONS_EXTENSIOND-1)") (class "Default")
      (node (ref "INSTRUCTIONS_EXTENSION") (pin "12") (pinfunction "1_12") (pintype "passive"))
      (node (ref "INSTRUCTION_MEMORY_LOWER") (pin "23") (pinfunction "23_23") (pintype "passive"))
      (node (ref "INSTRUCTION_MEMORY_UPPER") (pin "23") (pinfunction "23_23") (pintype "passive"))
      (node (ref "INSTRUCTION_MEMORY_UPPER2") (pin "23") (pinfunction "23_23") (pintype "passive"))
      (node (ref "MICRO_COUNTER_LOWER") (pin "11") (pinfunction "11_11") (pintype "passive"))
      (node (ref "USTEP_3") (pin "A") (pinfunction "A_A") (pintype "passive"))
    )
    (net (code "170") (name "Net-(INSTRUCTIONS_EXTENSIONE-1)") (class "Default")
      (node (ref "INSTRUCTIONS_EXTENSION") (pin "13") (pinfunction "1_13") (pintype "passive"))
      (node (ref "INSTRUCTION_MEMORY_LOWER") (pin "2") (pinfunction "2_2") (pintype "passive"))
      (node (ref "INSTRUCTION_MEMORY_UPPER") (pin "2") (pinfunction "2_2") (pintype "passive"))
      (node (ref "INSTRUCTION_MEMORY_UPPER2") (pin "2") (pinfunction "2_2") (pintype "passive"))
      (node (ref "MICRO_COUNTER_UPPER") (pin "14") (pinfunction "14_14") (pintype "passive"))
      (node (ref "USTEP_5") (pin "A") (pinfunction "A_A") (pintype "passive"))
    )
    (net (code "171") (name "Net-(INSTRUCTIONS_EXTENSIONH-1)") (class "Default")
      (node (ref "INSTRUCTIONS_EXTENSION") (pin "2") (pinfunction "1_2") (pintype "passive"))
      (node (ref "INSTRUCTION_MEMORY_LOWER") (pin "9") (pinfunction "9_9") (pintype "passive"))
      (node (ref "INSTRUCTION_MEMORY_UPPER") (pin "9") (pinfunction "9_9") (pintype "passive"))
      (node (ref "INSTRUCTION_MEMORY_UPPER2") (pin "9") (pinfunction "9_9") (pintype "passive"))
      (node (ref "INSTRUC_REGISTER_LOWER") (pin "5") (pinfunction "Q3_5") (pintype "tri_state"))
    )
    (net (code "172") (name "Net-(INSTRUCTIONS_EXTENSIONI-1)") (class "Default")
      (node (ref "INSTRUCTIONS_EXTENSION") (pin "3") (pinfunction "1_3") (pintype "passive"))
      (node (ref "INSTRUCTION_MEMORY_LOWER") (pin "8") (pinfunction "8_8") (pintype "passive"))
      (node (ref "INSTRUCTION_MEMORY_UPPER") (pin "8") (pinfunction "8_8") (pintype "passive"))
      (node (ref "INSTRUCTION_MEMORY_UPPER2") (pin "8") (pinfunction "8_8") (pintype "passive"))
      (node (ref "INSTRUC_REGISTER_LOWER") (pin "4") (pinfunction "Q2_4") (pintype "tri_state"))
    )
    (net (code "173") (name "Net-(INSTRUCTIONS_EXTENSIONJ-1)") (class "Default")
      (node (ref "INSTRUCTIONS_EXTENSION") (pin "4") (pinfunction "1_4") (pintype "passive"))
      (node (ref "INSTRUCTION_MEMORY_LOWER") (pin "7") (pinfunction "7_7") (pintype "passive"))
      (node (ref "INSTRUCTION_MEMORY_UPPER") (pin "7") (pinfunction "7_7") (pintype "passive"))
      (node (ref "INSTRUCTION_MEMORY_UPPER2") (pin "7") (pinfunction "7_7") (pintype "passive"))
      (node (ref "INSTRUC_REGISTER_LOWER") (pin "3") (pinfunction "Q1_3") (pintype "tri_state"))
    )
    (net (code "174") (name "Net-(INSTRUCTIONS_EXTENSIONK-1)") (class "Default")
      (node (ref "INSTRUCTIONS_EXTENSION") (pin "5") (pinfunction "1_5") (pintype "passive"))
      (node (ref "INSTRUCTION_MEMORY_LOWER") (pin "6") (pinfunction "6_6") (pintype "passive"))
      (node (ref "INSTRUCTION_MEMORY_UPPER") (pin "6") (pinfunction "6_6") (pintype "passive"))
      (node (ref "INSTRUCTION_MEMORY_UPPER2") (pin "6") (pinfunction "6_6") (pintype "passive"))
      (node (ref "INSTRUC_REGISTER_UPPER") (pin "6") (pinfunction "Q4_6") (pintype "tri_state"))
    )
    (net (code "175") (name "Net-(INSTRUCTIONS_EXTENSIONL-1)") (class "Default")
      (node (ref "INSTRUCTIONS_EXTENSION") (pin "6") (pinfunction "1_6") (pintype "passive"))
      (node (ref "INSTRUCTION_MEMORY_LOWER") (pin "5") (pinfunction "5_5") (pintype "passive"))
      (node (ref "INSTRUCTION_MEMORY_UPPER") (pin "5") (pinfunction "5_5") (pintype "passive"))
      (node (ref "INSTRUCTION_MEMORY_UPPER2") (pin "5") (pinfunction "5_5") (pintype "passive"))
      (node (ref "INSTRUC_REGISTER_UPPER") (pin "5") (pinfunction "Q3_5") (pintype "tri_state"))
    )
    (net (code "176") (name "Net-(INSTRUCTIONS_EXTENSIONM-1)") (class "Default")
      (node (ref "INSTRUCTIONS_EXTENSION") (pin "7") (pinfunction "1_7") (pintype "passive"))
      (node (ref "INSTRUCTION_MEMORY_LOWER") (pin "4") (pinfunction "4_4") (pintype "passive"))
      (node (ref "INSTRUCTION_MEMORY_UPPER") (pin "4") (pinfunction "4_4") (pintype "passive"))
      (node (ref "INSTRUCTION_MEMORY_UPPER2") (pin "4") (pinfunction "4_4") (pintype "passive"))
      (node (ref "INSTRUC_REGISTER_UPPER") (pin "4") (pinfunction "Q2_4") (pintype "tri_state"))
    )
    (net (code "177") (name "Net-(INSTRUCTIONS_EXTENSIONN-1)") (class "Default")
      (node (ref "INSTRUCTIONS_EXTENSION") (pin "8") (pinfunction "1_8") (pintype "passive"))
      (node (ref "INSTRUCTION_MEMORY_LOWER") (pin "3") (pinfunction "3_3") (pintype "passive"))
      (node (ref "INSTRUCTION_MEMORY_UPPER") (pin "3") (pinfunction "3_3") (pintype "passive"))
      (node (ref "INSTRUCTION_MEMORY_UPPER2") (pin "3") (pinfunction "3_3") (pintype "passive"))
      (node (ref "INSTRUC_REGISTER_UPPER") (pin "3") (pinfunction "Q1_3") (pintype "tri_state"))
    )
    (net (code "178") (name "Net-(INSTRUCTIONS_EXTENSIONO-1)") (class "Default")
      (node (ref "INSTRUCTIONS_EXTENSION") (pin "9") (pinfunction "1_9") (pintype "passive"))
      (node (ref "INSTRUCTION_MEMORY_LOWER") (pin "25") (pinfunction "25_25") (pintype "passive"))
      (node (ref "INSTRUCTION_MEMORY_UPPER") (pin "25") (pinfunction "25_25") (pintype "passive"))
      (node (ref "INSTRUCTION_MEMORY_UPPER2") (pin "25") (pinfunction "25_25") (pintype "passive"))
      (node (ref "MICRO_COUNTER_LOWER") (pin "14") (pinfunction "14_14") (pintype "passive"))
      (node (ref "USTEP_1") (pin "A") (pinfunction "A_A") (pintype "passive"))
    )
    (net (code "179") (name "Net-(INSTRUC_REGISTER_LOWERA-G1)") (class "Default")
      (node (ref "INSTRUC_REGISTER_LOWER") (pin "10") (pinfunction "G2_10") (pintype "input"))
      (node (ref "INSTRUC_REGISTER_LOWER") (pin "9") (pinfunction "G1_9") (pintype "input"))
      (node (ref "INSTRUC_REGISTER_UPPER") (pin "10") (pinfunction "G2_10") (pintype "input"))
      (node (ref "INSTRUC_REGISTER_UPPER") (pin "9") (pinfunction "G1_9") (pintype "input"))
      (node (ref "SELECTOR_LOGIC2_") (pin "5") (pinfunction "Y1_5") (pintype "output"))
    )
    (net (code "180") (name "Net-(INSTRUC_REGISTER_LOWERA-Q4)") (class "Default")
      (node (ref "INSTRUCTIONS_EXTENSION") (pin "1") (pinfunction "1_1") (pintype "passive"))
      (node (ref "INSTRUCTION_MEMORY_LOWER") (pin "10") (pinfunction "10_10") (pintype "passive"))
      (node (ref "INSTRUCTION_MEMORY_UPPER") (pin "10") (pinfunction "10_10") (pintype "passive"))
      (node (ref "INSTRUCTION_MEMORY_UPPER2") (pin "10") (pinfunction "10_10") (pintype "passive"))
      (node (ref "INSTRUC_REGISTER_LOWER") (pin "6") (pinfunction "Q4_6") (pintype "tri_state"))
    )
    (net (code "181") (name "Net-(INVERTED_CLK_LED-C)") (class "Default")
      (node (ref "INVERTED_CLK_LED") (pin "K") (pinfunction "C_K") (pintype "passive"))
      (node (ref "R45") (pin "2") (pinfunction "2_2") (pintype "passive"))
    )
    (net (code "182") (name "Net-(LED_A_REG_1-C)") (class "Default")
      (node (ref "LED_A_REG_1") (pin "K") (pinfunction "C_K") (pintype "passive"))
      (node (ref "R53") (pin "1") (pinfunction "1_1") (pintype "passive"))
    )
    (net (code "183") (name "Net-(LED_A_REG_2-C)") (class "Default")
      (node (ref "LED_A_REG_2") (pin "K") (pinfunction "C_K") (pintype "passive"))
      (node (ref "R54") (pin "1") (pinfunction "1_1") (pintype "passive"))
    )
    (net (code "184") (name "Net-(LED_A_REG_3-C)") (class "Default")
      (node (ref "LED_A_REG_3") (pin "K") (pinfunction "C_K") (pintype "passive"))
      (node (ref "R55") (pin "1") (pinfunction "1_1") (pintype "passive"))
    )
    (net (code "185") (name "Net-(LED_A_REG_4-C)") (class "Default")
      (node (ref "LED_A_REG_4") (pin "K") (pinfunction "C_K") (pintype "passive"))
      (node (ref "R56") (pin "1") (pinfunction "1_1") (pintype "passive"))
    )
    (net (code "186") (name "Net-(LED_A_REG_5-C)") (class "Default")
      (node (ref "LED_A_REG_5") (pin "K") (pinfunction "C_K") (pintype "passive"))
      (node (ref "R57") (pin "1") (pinfunction "1_1") (pintype "passive"))
    )
    (net (code "187") (name "Net-(LED_A_REG_6-C)") (class "Default")
      (node (ref "LED_A_REG_6") (pin "K") (pinfunction "C_K") (pintype "passive"))
      (node (ref "R58") (pin "1") (pinfunction "1_1") (pintype "passive"))
    )
    (net (code "188") (name "Net-(LED_A_REG_7-C)") (class "Default")
      (node (ref "LED_A_REG_7") (pin "K") (pinfunction "C_K") (pintype "passive"))
      (node (ref "R59") (pin "1") (pinfunction "1_1") (pintype "passive"))
    )
    (net (code "189") (name "Net-(LED_A_REG_8-C)") (class "Default")
      (node (ref "LED_A_REG_8") (pin "K") (pinfunction "C_K") (pintype "passive"))
      (node (ref "R60") (pin "1") (pinfunction "1_1") (pintype "passive"))
    )
    (net (code "190") (name "Net-(LED_B_REG_1-C)") (class "Default")
      (node (ref "LED_B_REG_1") (pin "K") (pinfunction "C_K") (pintype "passive"))
      (node (ref "R61") (pin "1") (pinfunction "1_1") (pintype "passive"))
    )
    (net (code "191") (name "Net-(LED_B_REG_2-C)") (class "Default")
      (node (ref "LED_B_REG_2") (pin "K") (pinfunction "C_K") (pintype "passive"))
      (node (ref "R62") (pin "1") (pinfunction "1_1") (pintype "passive"))
    )
    (net (code "192") (name "Net-(LED_B_REG_3-C)") (class "Default")
      (node (ref "LED_B_REG_3") (pin "K") (pinfunction "C_K") (pintype "passive"))
      (node (ref "R63") (pin "1") (pinfunction "1_1") (pintype "passive"))
    )
    (net (code "193") (name "Net-(LED_B_REG_4-C)") (class "Default")
      (node (ref "LED_B_REG_4") (pin "K") (pinfunction "C_K") (pintype "passive"))
      (node (ref "R64") (pin "1") (pinfunction "1_1") (pintype "passive"))
    )
    (net (code "194") (name "Net-(LED_B_REG_5-C)") (class "Default")
      (node (ref "LED_B_REG_5") (pin "K") (pinfunction "C_K") (pintype "passive"))
      (node (ref "R65") (pin "1") (pinfunction "1_1") (pintype "passive"))
    )
    (net (code "195") (name "Net-(LED_B_REG_6-C)") (class "Default")
      (node (ref "LED_B_REG_6") (pin "K") (pinfunction "C_K") (pintype "passive"))
      (node (ref "R66") (pin "1") (pinfunction "1_1") (pintype "passive"))
    )
    (net (code "196") (name "Net-(LED_B_REG_7-C)") (class "Default")
      (node (ref "LED_B_REG_7") (pin "K") (pinfunction "C_K") (pintype "passive"))
      (node (ref "R67") (pin "1") (pinfunction "1_1") (pintype "passive"))
    )
    (net (code "197") (name "Net-(LED_B_REG_8-C)") (class "Default")
      (node (ref "LED_B_REG_8") (pin "K") (pinfunction "C_K") (pintype "passive"))
      (node (ref "R68") (pin "1") (pinfunction "1_1") (pintype "passive"))
    )
    (net (code "198") (name "Net-(LOGIC_LED_1-C)") (class "Default")
      (node (ref "LOGIC_LED_1") (pin "K") (pinfunction "C_K") (pintype "passive"))
      (node (ref "R51") (pin "1") (pinfunction "1_1") (pintype "passive"))
    )
    (net (code "199") (name "Net-(LOGIC_LED_2-C)") (class "Default")
      (node (ref "LOGIC_LED_2") (pin "K") (pinfunction "C_K") (pintype "passive"))
      (node (ref "R50") (pin "1") (pinfunction "1_1") (pintype "passive"))
    )
    (net (code "200") (name "Net-(LOGIC_LED_3-C)") (class "Default")
      (node (ref "LOGIC_LED_3") (pin "K") (pinfunction "C_K") (pintype "passive"))
      (node (ref "R49") (pin "1") (pinfunction "1_1") (pintype "passive"))
    )
    (net (code "201") (name "Net-(LOGIC_LED_4-C)") (class "Default")
      (node (ref "LOGIC_LED_4") (pin "K") (pinfunction "C_K") (pintype "passive"))
      (node (ref "R48") (pin "1") (pinfunction "1_1") (pintype "passive"))
    )
    (net (code "202") (name "Net-(LOGIC_LED_5-C)") (class "Default")
      (node (ref "LOGIC_LED_5") (pin "K") (pinfunction "C_K") (pintype "passive"))
      (node (ref "R47") (pin "1") (pinfunction "1_1") (pintype "passive"))
    )
    (net (code "203") (name "Net-(LOGIC_LED_6-C)") (class "Default")
      (node (ref "LOGIC_LED_6") (pin "K") (pinfunction "C_K") (pintype "passive"))
      (node (ref "R46") (pin "1") (pinfunction "1_1") (pintype "passive"))
    )
    (net (code "204") (name "Net-(LOGIC_LED_7-C)") (class "Default")
      (node (ref "LOGIC_LED_7") (pin "K") (pinfunction "C_K") (pintype "passive"))
      (node (ref "R6") (pin "1") (pinfunction "1_1") (pintype "passive"))
    )
    (net (code "205") (name "Net-(LOGIC_LED_8-C)") (class "Default")
      (node (ref "LOGIC_LED_8") (pin "K") (pinfunction "C_K") (pintype "passive"))
      (node (ref "R52") (pin "1") (pinfunction "1_1") (pintype "passive"))
    )
    (net (code "206") (name "Net-(LOGIC_SELECTOR-AND/OR_LOWERA-1B)") (class "Default")
      (node (ref "LOGIC_SELECTOR-AND/OR_LOWER") (pin "3") (pinfunction "1B_3") (pintype "input"))
      (node (ref "OR_GATE1") (pin "6") (pinfunction "O_6") (pintype "output"))
    )
    (net (code "207") (name "Net-(LOGIC_SELECTOR-AND/OR_LOWERA-1Y)") (class "Default")
      (node (ref "LOGIC_LED_1") (pin "A") (pinfunction "A_A") (pintype "passive"))
      (node (ref "LOGIC_SELECTOR-AND/OR_LOWER") (pin "4") (pinfunction "1Y_4") (pintype "output"))
      (node (ref "LOGIC_SELECTOR-XOR/NOT_LOWER") (pin "4") (pinfunction "1Y_4") (pintype "output"))
      (node (ref "OUTPUT_BUFFER_LOGIC") (pin "2") (pinfunction "A1_2") (pintype "bidirectional"))
    )
    (net (code "208") (name "Net-(LOGIC_SELECTOR-AND/OR_LOWERA-2B)") (class "Default")
      (node (ref "LOGIC_SELECTOR-AND/OR_LOWER") (pin "6") (pinfunction "2B_6") (pintype "input"))
      (node (ref "OR_GATE1") (pin "8") (pinfunction "O_8") (pintype "output"))
    )
    (net (code "209") (name "Net-(LOGIC_SELECTOR-AND/OR_LOWERA-2Y)") (class "Default")
      (node (ref "LOGIC_LED_2") (pin "A") (pinfunction "A_A") (pintype "passive"))
      (node (ref "LOGIC_SELECTOR-AND/OR_LOWER") (pin "7") (pinfunction "2Y_7") (pintype "output"))
      (node (ref "LOGIC_SELECTOR-XOR/NOT_LOWER") (pin "7") (pinfunction "2Y_7") (pintype "output"))
      (node (ref "OUTPUT_BUFFER_LOGIC") (pin "3") (pinfunction "A2_3") (pintype "bidirectional"))
    )
    (net (code "210") (name "Net-(LOGIC_SELECTOR-AND/OR_LOWERA-3B)") (class "Default")
      (node (ref "LOGIC_SELECTOR-AND/OR_LOWER") (pin "10") (pinfunction "3B_10") (pintype "input"))
      (node (ref "OR_GATE1") (pin "11") (pinfunction "O_11") (pintype "output"))
    )
    (net (code "211") (name "Net-(LOGIC_SELECTOR-AND/OR_LOWERA-3Y)") (class "Default")
      (node (ref "LOGIC_LED_3") (pin "A") (pinfunction "A_A") (pintype "passive"))
      (node (ref "LOGIC_SELECTOR-AND/OR_LOWER") (pin "9") (pinfunction "3Y_9") (pintype "output"))
      (node (ref "LOGIC_SELECTOR-XOR/NOT_LOWER") (pin "9") (pinfunction "3Y_9") (pintype "output"))
      (node (ref "OUTPUT_BUFFER_LOGIC") (pin "4") (pinfunction "A3_4") (pintype "bidirectional"))
    )
    (net (code "212") (name "Net-(LOGIC_SELECTOR-AND/OR_LOWERA-4B)") (class "Default")
      (node (ref "LOGIC_SELECTOR-AND/OR_LOWER") (pin "13") (pinfunction "4B_13") (pintype "input"))
      (node (ref "OR_GATE") (pin "3") (pinfunction "O_3") (pintype "output"))
    )
    (net (code "213") (name "Net-(LOGIC_SELECTOR-AND/OR_LOWERA-4Y)") (class "Default")
      (node (ref "LOGIC_LED_4") (pin "A") (pinfunction "A_A") (pintype "passive"))
      (node (ref "LOGIC_SELECTOR-AND/OR_LOWER") (pin "12") (pinfunction "4Y_12") (pintype "output"))
      (node (ref "LOGIC_SELECTOR-XOR/NOT_LOWER") (pin "12") (pinfunction "4Y_12") (pintype "output"))
      (node (ref "OUTPUT_BUFFER_LOGIC") (pin "5") (pinfunction "A4_5") (pintype "bidirectional"))
    )
    (net (code "214") (name "Net-(LOGIC_SELECTOR-AND/OR_LOWERA-~{A}{slash}B)") (class "Default")
      (node (ref "INSTRUCTION_MEMORY_UPPER2") (pin "12") (pinfunction "12_12") (pintype "passive"))
      (node (ref "LOGIC_SELECTOR-AND/OR_LOWER") (pin "1") (pinfunction "~{A}/B_1") (pintype "input"))
      (node (ref "LOGIC_SELECTOR-AND/OR_UPPER") (pin "1") (pinfunction "~{A}/B_1") (pintype "input"))
      (node (ref "LOGIC_SELECTOR-XOR/NOT_LOWER") (pin "1") (pinfunction "~{A}/B_1") (pintype "input"))
      (node (ref "LOGIC_SELECTOR-XOR/NOT_UPPER") (pin "1") (pinfunction "~{A}/B_1") (pintype "input"))
      (node (ref "SELECTOR_LOGIC_") (pin "2") (pinfunction "A_2") (pintype "input"))
    )
    (net (code "215") (name "Net-(LOGIC_SELECTOR-AND/OR_UPPERA-1B)") (class "Default")
      (node (ref "LOGIC_SELECTOR-AND/OR_UPPER") (pin "3") (pinfunction "1B_3") (pintype "input"))
      (node (ref "OR_GATE") (pin "6") (pinfunction "O_6") (pintype "output"))
    )
    (net (code "216") (name "Net-(LOGIC_SELECTOR-AND/OR_UPPERA-1Y)") (class "Default")
      (node (ref "LOGIC_LED_5") (pin "A") (pinfunction "A_A") (pintype "passive"))
      (node (ref "LOGIC_SELECTOR-AND/OR_UPPER") (pin "4") (pinfunction "1Y_4") (pintype "output"))
      (node (ref "LOGIC_SELECTOR-XOR/NOT_UPPER") (pin "4") (pinfunction "1Y_4") (pintype "output"))
      (node (ref "OUTPUT_BUFFER_LOGIC") (pin "6") (pinfunction "A5_6") (pintype "bidirectional"))
    )
    (net (code "217") (name "Net-(LOGIC_SELECTOR-AND/OR_UPPERA-2B)") (class "Default")
      (node (ref "LOGIC_SELECTOR-AND/OR_UPPER") (pin "6") (pinfunction "2B_6") (pintype "input"))
      (node (ref "OR_GATE") (pin "8") (pinfunction "O_8") (pintype "output"))
    )
    (net (code "218") (name "Net-(LOGIC_SELECTOR-AND/OR_UPPERA-2Y)") (class "Default")
      (node (ref "LOGIC_LED_6") (pin "A") (pinfunction "A_A") (pintype "passive"))
      (node (ref "LOGIC_SELECTOR-AND/OR_UPPER") (pin "7") (pinfunction "2Y_7") (pintype "output"))
      (node (ref "LOGIC_SELECTOR-XOR/NOT_UPPER") (pin "7") (pinfunction "2Y_7") (pintype "output"))
      (node (ref "OUTPUT_BUFFER_LOGIC") (pin "7") (pinfunction "A6_7") (pintype "bidirectional"))
    )
    (net (code "219") (name "Net-(LOGIC_SELECTOR-AND/OR_UPPERA-3B)") (class "Default")
      (node (ref "LOGIC_SELECTOR-AND/OR_UPPER") (pin "10") (pinfunction "3B_10") (pintype "input"))
      (node (ref "OR_GATE") (pin "11") (pinfunction "O_11") (pintype "output"))
    )
    (net (code "220") (name "Net-(LOGIC_SELECTOR-AND/OR_UPPERA-3Y)") (class "Default")
      (node (ref "LOGIC_LED_7") (pin "A") (pinfunction "A_A") (pintype "passive"))
      (node (ref "LOGIC_SELECTOR-AND/OR_UPPER") (pin "9") (pinfunction "3Y_9") (pintype "output"))
      (node (ref "LOGIC_SELECTOR-XOR/NOT_UPPER") (pin "9") (pinfunction "3Y_9") (pintype "output"))
      (node (ref "OUTPUT_BUFFER_LOGIC") (pin "8") (pinfunction "A7_8") (pintype "bidirectional"))
    )
    (net (code "221") (name "Net-(LOGIC_SELECTOR-AND/OR_UPPERA-4B)") (class "Default")
      (node (ref "LOGIC_SELECTOR-AND/OR_UPPER") (pin "13") (pinfunction "4B_13") (pintype "input"))
      (node (ref "OR_GATE_2") (pin "3") (pinfunction "O_3") (pintype "output"))
    )
    (net (code "222") (name "Net-(LOGIC_SELECTOR-AND/OR_UPPERA-4Y)") (class "Default")
      (node (ref "LOGIC_LED_8") (pin "A") (pinfunction "A_A") (pintype "passive"))
      (node (ref "LOGIC_SELECTOR-AND/OR_UPPER") (pin "12") (pinfunction "4Y_12") (pintype "output"))
      (node (ref "LOGIC_SELECTOR-XOR/NOT_UPPER") (pin "12") (pinfunction "4Y_12") (pintype "output"))
      (node (ref "OUTPUT_BUFFER_LOGIC") (pin "9") (pinfunction "A8_9") (pintype "bidirectional"))
    )
    (net (code "223") (name "Net-(LOGIC_SELECTOR-XOR/NOT_LOWERA-1A)") (class "Default")
      (node (ref "LOGIC_SELECTOR-XOR/NOT_LOWER") (pin "2") (pinfunction "1A_2") (pintype "input"))
      (node (ref "NOT_GATE3_") (pin "6") (pinfunction "O_6") (pintype "output"))
    )
    (net (code "224") (name "Net-(LOGIC_SELECTOR-XOR/NOT_LOWERA-1B)") (class "Default")
      (node (ref "LOGIC_SELECTOR-XOR/NOT_LOWER") (pin "3") (pinfunction "1B_3") (pintype "input"))
      (node (ref "SUBTRACT_INVRTR_UPPER_1") (pin "3") (pinfunction "O_3") (pintype "output"))
    )
    (net (code "225") (name "Net-(LOGIC_SELECTOR-XOR/NOT_LOWERA-2A)") (class "Default")
      (node (ref "LOGIC_SELECTOR-XOR/NOT_LOWER") (pin "5") (pinfunction "2A_5") (pintype "input"))
      (node (ref "NOT_GATE3_") (pin "8") (pinfunction "O_8") (pintype "output"))
    )
    (net (code "226") (name "Net-(LOGIC_SELECTOR-XOR/NOT_LOWERA-2B)") (class "Default")
      (node (ref "LOGIC_SELECTOR-XOR/NOT_LOWER") (pin "6") (pinfunction "2B_6") (pintype "input"))
      (node (ref "SUBTRACT_INVRTR_UPPER_1") (pin "6") (pinfunction "O_6") (pintype "output"))
    )
    (net (code "227") (name "Net-(LOGIC_SELECTOR-XOR/NOT_LOWERA-3A)") (class "Default")
      (node (ref "LOGIC_SELECTOR-XOR/NOT_LOWER") (pin "11") (pinfunction "3A_11") (pintype "input"))
      (node (ref "NOT_GATE3_") (pin "10") (pinfunction "O_10") (pintype "output"))
    )
    (net (code "228") (name "Net-(LOGIC_SELECTOR-XOR/NOT_LOWERA-3B)") (class "Default")
      (node (ref "LOGIC_SELECTOR-XOR/NOT_LOWER") (pin "10") (pinfunction "3B_10") (pintype "input"))
      (node (ref "SUBTRACT_INVRTR_UPPER_1") (pin "8") (pinfunction "O_8") (pintype "output"))
    )
    (net (code "229") (name "Net-(LOGIC_SELECTOR-XOR/NOT_LOWERA-4A)") (class "Default")
      (node (ref "LOGIC_SELECTOR-XOR/NOT_LOWER") (pin "14") (pinfunction "4A_14") (pintype "input"))
      (node (ref "NOT_GATE3_") (pin "12") (pinfunction "O_12") (pintype "output"))
    )
    (net (code "230") (name "Net-(LOGIC_SELECTOR-XOR/NOT_LOWERA-4B)") (class "Default")
      (node (ref "LOGIC_SELECTOR-XOR/NOT_LOWER") (pin "13") (pinfunction "4B_13") (pintype "input"))
      (node (ref "SUBTRACT_INVRTR_UPPER_1") (pin "11") (pinfunction "O_11") (pintype "output"))
    )
    (net (code "231") (name "Net-(LOGIC_SELECTOR-XOR/NOT_UPPERA-1A)") (class "Default")
      (node (ref "LOGIC_SELECTOR-XOR/NOT_UPPER") (pin "2") (pinfunction "1A_2") (pintype "input"))
      (node (ref "NOT_GATE_") (pin "2") (pinfunction "O_2") (pintype "output"))
    )
    (net (code "232") (name "Net-(LOGIC_SELECTOR-XOR/NOT_UPPERA-1B)") (class "Default")
      (node (ref "LOGIC_SELECTOR-XOR/NOT_UPPER") (pin "3") (pinfunction "1B_3") (pintype "input"))
      (node (ref "SUBTRACT_INVRTR_LOWER_1") (pin "3") (pinfunction "O_3") (pintype "output"))
    )
    (net (code "233") (name "Net-(LOGIC_SELECTOR-XOR/NOT_UPPERA-2A)") (class "Default")
      (node (ref "LOGIC_SELECTOR-XOR/NOT_UPPER") (pin "5") (pinfunction "2A_5") (pintype "input"))
      (node (ref "NOT_GATE_") (pin "4") (pinfunction "O_4") (pintype "output"))
    )
    (net (code "234") (name "Net-(LOGIC_SELECTOR-XOR/NOT_UPPERA-2B)") (class "Default")
      (node (ref "LOGIC_SELECTOR-XOR/NOT_UPPER") (pin "6") (pinfunction "2B_6") (pintype "input"))
      (node (ref "SUBTRACT_INVRTR_LOWER_1") (pin "6") (pinfunction "O_6") (pintype "output"))
    )
    (net (code "235") (name "Net-(LOGIC_SELECTOR-XOR/NOT_UPPERA-3A)") (class "Default")
      (node (ref "LOGIC_SELECTOR-XOR/NOT_UPPER") (pin "11") (pinfunction "3A_11") (pintype "input"))
      (node (ref "NOT_GATE_") (pin "6") (pinfunction "O_6") (pintype "output"))
    )
    (net (code "236") (name "Net-(LOGIC_SELECTOR-XOR/NOT_UPPERA-3B)") (class "Default")
      (node (ref "LOGIC_SELECTOR-XOR/NOT_UPPER") (pin "10") (pinfunction "3B_10") (pintype "input"))
      (node (ref "SUBTRACT_INVRTR_LOWER_1") (pin "8") (pinfunction "O_8") (pintype "output"))
    )
    (net (code "237") (name "Net-(LOGIC_SELECTOR-XOR/NOT_UPPERA-4A)") (class "Default")
      (node (ref "LOGIC_SELECTOR-XOR/NOT_UPPER") (pin "14") (pinfunction "4A_14") (pintype "input"))
      (node (ref "NOT_GATE_") (pin "8") (pinfunction "O_8") (pintype "output"))
    )
    (net (code "238") (name "Net-(LOGIC_SELECTOR-XOR/NOT_UPPERA-4B)") (class "Default")
      (node (ref "LOGIC_SELECTOR-XOR/NOT_UPPER") (pin "13") (pinfunction "4B_13") (pintype "input"))
      (node (ref "SUBTRACT_INVRTR_LOWER_1") (pin "11") (pinfunction "O_11") (pintype "output"))
    )
    (net (code "239") (name "Net-(MICRO_COUNTER_LOWER-Pad15)") (class "Default")
      (node (ref "MICRO_COUNTER_LOWER") (pin "15") (pinfunction "15_15") (pintype "passive"))
      (node (ref "MICRO_COUNTER_UPPER") (pin "10") (pinfunction "10_10") (pintype "passive"))
    )
    (net (code "240") (name "Net-(NOT_GATE1A-I)") (class "Default")
      (node (ref "NOT_GATE1") (pin "1") (pinfunction "I_1") (pintype "input"))
      (node (ref "SELECTOR_LOGIC2_") (pin "7") (pinfunction "Y3_7") (pintype "output"))
    )
    (net (code "241") (name "Net-(NOT_GATE1D-O)") (class "Default")
      (node (ref "NOT_GATE1") (pin "8") (pinfunction "O_8") (pintype "output"))
      (node (ref "OUTPUT_BUFFER_MEMORY") (pin "19") (pinfunction "G_19") (pintype "input"))
    )
    (net (code "242") (name "Net-(NOT_GATE1E-O)") (class "Default")
      (node (ref "MICRO_COUNTER_LOWER") (pin "2") (pinfunction "2_2") (pintype "passive"))
      (node (ref "MICRO_COUNTER_UPPER") (pin "2") (pinfunction "2_2") (pintype "passive"))
      (node (ref "NOT_GATE1") (pin "10") (pinfunction "O_10") (pintype "output"))
    )
    (net (code "243") (name "Net-(NOT_GATE1F-I)") (class "Default")
      (node (ref "INSTRUCTION_MEMORY_UPPER") (pin "16") (pinfunction "16_16") (pintype "passive"))
      (node (ref "NOT_GATE1") (pin "13") (pinfunction "I_13") (pintype "input"))
    )
    (net (code "244") (name "Net-(NOT_GATE2_A-I)") (class "Default")
      (node (ref "INSTRUCTION_MEMORY_UPPER2") (pin "17") (pinfunction "17_17") (pintype "passive"))
      (node (ref "NOT_GATE2_") (pin "1") (pinfunction "I_1") (pintype "input"))
    )
    (net (code "245") (name "Net-(NOT_GATE2_A-O)") (class "Default")
      (node (ref "NOT_GATE2_") (pin "2") (pinfunction "O_2") (pintype "output"))
      (node (ref "OUTPUT_BUFFER_PARAM_REG") (pin "19") (pinfunction "G_19") (pintype "input"))
    )
    (net (code "246") (name "Net-(NOT_GATE2_B-I)") (class "Default")
      (node (ref "INSTRUCTION_MEMORY_UPPER2") (pin "16") (pinfunction "16_16") (pintype "passive"))
      (node (ref "NOT_GATE2_") (pin "3") (pinfunction "I_3") (pintype "input"))
    )
    (net (code "247") (name "Net-(NOT_GATE2_E-I)") (class "Default")
      (node (ref "NOT_GATE2_") (pin "11") (pinfunction "I_11") (pintype "input"))
      (node (ref "SELECTOR_LOGIC_") (pin "9") (pinfunction "Y3_9") (pintype "output"))
    )
    (net (code "248") (name "Net-(NOT_GATE2_E-O)") (class "Default")
      (node (ref "NOT_GATE2_") (pin "10") (pinfunction "O_10") (pintype "output"))
      (node (ref "PROGRAM_COUNTER_LOWER") (pin "10") (pinfunction "10_10") (pintype "passive"))
    )
    (net (code "249") (name "Net-(NOT_GATE2_F-O)") (class "Default")
      (node (ref "NOT_GATE2_") (pin "12") (pinfunction "O_12") (pintype "output"))
      (node (ref "OUTPUT_BUFFER_RAM") (pin "1") (pinfunction "DIR_1") (pintype "input"))
      (node (ref "RAM") (pin "27") (pinfunction "27_27") (pintype "passive"))
    )
    (net (code "250") (name "Net-(NOT_GATE3_B-I)") (class "Default")
      (node (ref "INSTRUCTION_MEMORY_UPPER") (pin "13") (pinfunction "13_13") (pintype "passive"))
      (node (ref "NOT_GATE3_") (pin "3") (pinfunction "I_3") (pintype "input"))
    )
    (net (code "251") (name "Net-(NOT_GATE3_B-O)") (class "Default")
      (node (ref "NOT_GATE3_") (pin "4") (pinfunction "O_4") (pintype "output"))
      (node (ref "OUTPUT_BUFFER_ALU") (pin "19") (pinfunction "G_19") (pintype "input"))
    )
    (net (code "252") (name "Net-(NOT_GATE4_B-O)") (class "Default")
      (node (ref "NOT_GATE4_") (pin "4") (pinfunction "O_4") (pintype "output"))
      (node (ref "RAM_ADDR_LOWER") (pin "10") (pinfunction "G2_10") (pintype "input"))
      (node (ref "RAM_ADDR_LOWER") (pin "9") (pinfunction "G1_9") (pintype "input"))
      (node (ref "RAM_ADDR_UPPER") (pin "10") (pinfunction "G2_10") (pintype "input"))
      (node (ref "RAM_ADDR_UPPER") (pin "9") (pinfunction "G1_9") (pintype "input"))
    )
    (net (code "253") (name "Net-(NOT_GATE4_C-O)") (class "Default")
      (node (ref "NOT_GATE4_") (pin "6") (pinfunction "O_6") (pintype "output"))
      (node (ref "PROGRAM_COUNTER_LOWER") (pin "9") (pinfunction "9_9") (pintype "passive"))
      (node (ref "PROGRAM_COUNTER_UPPER") (pin "9") (pinfunction "9_9") (pintype "passive"))
    )
    (net (code "254") (name "Net-(NOT_GATE4_D-O)") (class "Default")
      (node (ref "MICRO_COUNTER_LOWER") (pin "9") (pinfunction "9_9") (pintype "passive"))
      (node (ref "MICRO_COUNTER_UPPER") (pin "9") (pinfunction "9_9") (pintype "passive"))
      (node (ref "NOT_GATE4_") (pin "8") (pinfunction "O_8") (pintype "output"))
    )
    (net (code "255") (name "Net-(NOT_GATE4_E-I)") (class "Default")
      (node (ref "INSTRUCTION_MEMORY_UPPER") (pin "17") (pinfunction "17_17") (pintype "passive"))
      (node (ref "NOT_GATE4_") (pin "11") (pinfunction "I_11") (pintype "input"))
    )
    (net (code "256") (name "Net-(NOT_GATE4_E-O)") (class "Default")
      (node (ref "NOT_GATE4_") (pin "10") (pinfunction "O_10") (pintype "output"))
      (node (ref "OUTPUT_BUFFER_RAM") (pin "19") (pinfunction "G_19") (pintype "input"))
    )
    (net (code "257") (name "Net-(NOT_GATE5_A-I)") (class "Default")
      (node (ref "NOT_GATE5_") (pin "1") (pinfunction "I_1") (pintype "input"))
      (node (ref "SELECTOR_LOGIC_") (pin "11") (pinfunction "Y1_11") (pintype "output"))
    )
    (net (code "258") (name "Net-(NOT_GATE_E-I)") (class "Default")
      (node (ref "INSTRUCTION_MEMORY_UPPER2") (pin "11") (pinfunction "11_11") (pintype "passive"))
      (node (ref "NOT_GATE_") (pin "11") (pinfunction "I_11") (pintype "input"))
    )
    (net (code "259") (name "Net-(NOT_GATE_E-O)") (class "Default")
      (node (ref "NOT_GATE_") (pin "10") (pinfunction "O_10") (pintype "output"))
      (node (ref "OUTPUT_BUFFER_FLAGS") (pin "19") (pinfunction "G_19") (pintype "input"))
    )
    (net (code "260") (name "Net-(NOT_GATE_F-I)") (class "Default")
      (node (ref "INSTRUCTION_MEMORY_UPPER2") (pin "15") (pinfunction "15_15") (pintype "passive"))
      (node (ref "NOT_GATE_") (pin "13") (pinfunction "I_13") (pintype "input"))
    )
    (net (code "261") (name "Net-(NOT_GATE_F-O)") (class "Default")
      (node (ref "NOT_GATE_") (pin "12") (pinfunction "O_12") (pintype "output"))
      (node (ref "OUTPUT_BUFFER_LOGIC") (pin "19") (pinfunction "G_19") (pintype "input"))
    )
    (net (code "262") (name "Net-(OUTPUT_BUFFER_CALC_REGA-G)") (class "Default")
      (node (ref "OUTPUT_BUFFER_CALC_REG") (pin "19") (pinfunction "G_19") (pintype "input"))
      (node (ref "SELECTOR_LOGIC2_") (pin "11") (pinfunction "Y1_11") (pintype "output"))
    )
    (net (code "263") (name "Net-(OUTPUT_BUFFER_MEMORYA-A1)") (class "Default")
      (node (ref "MEMORY") (pin "19") (pinfunction "19_19") (pintype "passive"))
      (node (ref "OUTPUT_BUFFER_MEMORY") (pin "2") (pinfunction "A1_2") (pintype "bidirectional"))
    )
    (net (code "264") (name "Net-(OUTPUT_BUFFER_MEMORYA-A2)") (class "Default")
      (node (ref "MEMORY") (pin "18") (pinfunction "18_18") (pintype "passive"))
      (node (ref "OUTPUT_BUFFER_MEMORY") (pin "3") (pinfunction "A2_3") (pintype "bidirectional"))
    )
    (net (code "265") (name "Net-(OUTPUT_BUFFER_MEMORYA-A3)") (class "Default")
      (node (ref "MEMORY") (pin "17") (pinfunction "17_17") (pintype "passive"))
      (node (ref "OUTPUT_BUFFER_MEMORY") (pin "4") (pinfunction "A3_4") (pintype "bidirectional"))
    )
    (net (code "266") (name "Net-(OUTPUT_BUFFER_MEMORYA-A4)") (class "Default")
      (node (ref "MEMORY") (pin "16") (pinfunction "16_16") (pintype "passive"))
      (node (ref "OUTPUT_BUFFER_MEMORY") (pin "5") (pinfunction "A4_5") (pintype "bidirectional"))
    )
    (net (code "267") (name "Net-(OUTPUT_BUFFER_MEMORYA-A5)") (class "Default")
      (node (ref "MEMORY") (pin "15") (pinfunction "15_15") (pintype "passive"))
      (node (ref "OUTPUT_BUFFER_MEMORY") (pin "6") (pinfunction "A5_6") (pintype "bidirectional"))
    )
    (net (code "268") (name "Net-(OUTPUT_BUFFER_MEMORYA-A6)") (class "Default")
      (node (ref "MEMORY") (pin "13") (pinfunction "13_13") (pintype "passive"))
      (node (ref "OUTPUT_BUFFER_MEMORY") (pin "7") (pinfunction "A6_7") (pintype "bidirectional"))
    )
    (net (code "269") (name "Net-(OUTPUT_BUFFER_MEMORYA-A7)") (class "Default")
      (node (ref "MEMORY") (pin "12") (pinfunction "12_12") (pintype "passive"))
      (node (ref "OUTPUT_BUFFER_MEMORY") (pin "8") (pinfunction "A7_8") (pintype "bidirectional"))
    )
    (net (code "270") (name "Net-(OUTPUT_BUFFER_MEMORYA-A8)") (class "Default")
      (node (ref "MEMORY") (pin "11") (pinfunction "11_11") (pintype "passive"))
      (node (ref "OUTPUT_BUFFER_MEMORY") (pin "9") (pinfunction "A8_9") (pintype "bidirectional"))
    )
    (net (code "271") (name "Net-(OUTPUT_BUFFER_PCA-A1)") (class "Default")
      (node (ref "OUTPUT_BUFFER_PC") (pin "2") (pinfunction "A1_2") (pintype "bidirectional"))
      (node (ref "PC_8") (pin "A") (pinfunction "A_A") (pintype "passive"))
      (node (ref "PROGRAM_COUNTER_UPPER") (pin "11") (pinfunction "11_11") (pintype "passive"))
    )
    (net (code "272") (name "Net-(OUTPUT_BUFFER_PCA-A2)") (class "Default")
      (node (ref "OUTPUT_BUFFER_PC") (pin "3") (pinfunction "A2_3") (pintype "bidirectional"))
      (node (ref "PC_7") (pin "A") (pinfunction "A_A") (pintype "passive"))
      (node (ref "PROGRAM_COUNTER_UPPER") (pin "12") (pinfunction "12_12") (pintype "passive"))
    )
    (net (code "273") (name "Net-(OUTPUT_BUFFER_PCA-A3)") (class "Default")
      (node (ref "OUTPUT_BUFFER_PC") (pin "4") (pinfunction "A3_4") (pintype "bidirectional"))
      (node (ref "PC_6") (pin "A") (pinfunction "A_A") (pintype "passive"))
      (node (ref "PROGRAM_COUNTER_UPPER") (pin "13") (pinfunction "13_13") (pintype "passive"))
    )
    (net (code "274") (name "Net-(OUTPUT_BUFFER_PCA-A4)") (class "Default")
      (node (ref "OUTPUT_BUFFER_PC") (pin "5") (pinfunction "A4_5") (pintype "bidirectional"))
      (node (ref "PC_5") (pin "A") (pinfunction "A_A") (pintype "passive"))
      (node (ref "PROGRAM_COUNTER_UPPER") (pin "14") (pinfunction "14_14") (pintype "passive"))
    )
    (net (code "275") (name "Net-(OUTPUT_BUFFER_PCA-A5)") (class "Default")
      (node (ref "OUTPUT_BUFFER_PC") (pin "6") (pinfunction "A5_6") (pintype "bidirectional"))
      (node (ref "PC_4") (pin "A") (pinfunction "A_A") (pintype "passive"))
      (node (ref "PROGRAM_COUNTER_LOWER") (pin "11") (pinfunction "11_11") (pintype "passive"))
    )
    (net (code "276") (name "Net-(OUTPUT_BUFFER_PCA-A6)") (class "Default")
      (node (ref "OUTPUT_BUFFER_PC") (pin "7") (pinfunction "A6_7") (pintype "bidirectional"))
      (node (ref "PC_3") (pin "A") (pinfunction "A_A") (pintype "passive"))
      (node (ref "PROGRAM_COUNTER_LOWER") (pin "12") (pinfunction "12_12") (pintype "passive"))
    )
    (net (code "277") (name "Net-(OUTPUT_BUFFER_PCA-A7)") (class "Default")
      (node (ref "OUTPUT_BUFFER_PC") (pin "8") (pinfunction "A7_8") (pintype "bidirectional"))
      (node (ref "PC_2") (pin "A") (pinfunction "A_A") (pintype "passive"))
      (node (ref "PROGRAM_COUNTER_LOWER") (pin "13") (pinfunction "13_13") (pintype "passive"))
    )
    (net (code "278") (name "Net-(OUTPUT_BUFFER_PCA-A8)") (class "Default")
      (node (ref "OUTPUT_BUFFER_PC") (pin "9") (pinfunction "A8_9") (pintype "bidirectional"))
      (node (ref "PC_1") (pin "A") (pinfunction "A_A") (pintype "passive"))
      (node (ref "PROGRAM_COUNTER_LOWER") (pin "14") (pinfunction "14_14") (pintype "passive"))
    )
    (net (code "279") (name "Net-(OUTPUT_BUFFER_PCA-G)") (class "Default")
      (node (ref "OUTPUT_BUFFER_PC") (pin "19") (pinfunction "G_19") (pintype "input"))
      (node (ref "SELECTOR_LOGIC_") (pin "10") (pinfunction "Y2_10") (pintype "output"))
    )
    (net (code "280") (name "Net-(OUTPUT_BUFFER_RAMA-A1)") (class "Default")
      (node (ref "OUTPUT_BUFFER_RAM") (pin "2") (pinfunction "A1_2") (pintype "bidirectional"))
      (node (ref "RAM") (pin "11") (pinfunction "11_11") (pintype "passive"))
      (node (ref "RAM_LED_1") (pin "A") (pinfunction "A_A") (pintype "passive"))
    )
    (net (code "281") (name "Net-(OUTPUT_BUFFER_RAMA-A2)") (class "Default")
      (node (ref "OUTPUT_BUFFER_RAM") (pin "3") (pinfunction "A2_3") (pintype "bidirectional"))
      (node (ref "RAM") (pin "12") (pinfunction "12_12") (pintype "passive"))
      (node (ref "RAM_LED_2") (pin "A") (pinfunction "A_A") (pintype "passive"))
    )
    (net (code "282") (name "Net-(OUTPUT_BUFFER_RAMA-A3)") (class "Default")
      (node (ref "OUTPUT_BUFFER_RAM") (pin "4") (pinfunction "A3_4") (pintype "bidirectional"))
      (node (ref "RAM") (pin "13") (pinfunction "13_13") (pintype "passive"))
      (node (ref "RAM_LED_3") (pin "A") (pinfunction "A_A") (pintype "passive"))
    )
    (net (code "283") (name "Net-(OUTPUT_BUFFER_RAMA-A4)") (class "Default")
      (node (ref "OUTPUT_BUFFER_RAM") (pin "5") (pinfunction "A4_5") (pintype "bidirectional"))
      (node (ref "RAM") (pin "15") (pinfunction "15_15") (pintype "passive"))
      (node (ref "RAM_LED_4") (pin "A") (pinfunction "A_A") (pintype "passive"))
    )
    (net (code "284") (name "Net-(OUTPUT_BUFFER_RAMA-A5)") (class "Default")
      (node (ref "OUTPUT_BUFFER_RAM") (pin "6") (pinfunction "A5_6") (pintype "bidirectional"))
      (node (ref "RAM") (pin "16") (pinfunction "16_16") (pintype "passive"))
      (node (ref "RAM_LED_5") (pin "A") (pinfunction "A_A") (pintype "passive"))
    )
    (net (code "285") (name "Net-(OUTPUT_BUFFER_RAMA-A6)") (class "Default")
      (node (ref "OUTPUT_BUFFER_RAM") (pin "7") (pinfunction "A6_7") (pintype "bidirectional"))
      (node (ref "RAM") (pin "17") (pinfunction "17_17") (pintype "passive"))
      (node (ref "RAM_LED_6") (pin "A") (pinfunction "A_A") (pintype "passive"))
    )
    (net (code "286") (name "Net-(OUTPUT_BUFFER_RAMA-A7)") (class "Default")
      (node (ref "OUTPUT_BUFFER_RAM") (pin "8") (pinfunction "A7_8") (pintype "bidirectional"))
      (node (ref "RAM") (pin "18") (pinfunction "18_18") (pintype "passive"))
      (node (ref "RAM_LED_7") (pin "A") (pinfunction "A_A") (pintype "passive"))
    )
    (net (code "287") (name "Net-(OUTPUT_BUFFER_RAMA-A8)") (class "Default")
      (node (ref "OUTPUT_BUFFER_RAM") (pin "9") (pinfunction "A8_9") (pintype "bidirectional"))
      (node (ref "RAM") (pin "19") (pinfunction "19_19") (pintype "passive"))
      (node (ref "RAM_LED_8") (pin "A") (pinfunction "A_A") (pintype "passive"))
    )
    (net (code "288") (name "Net-(OVERFLOW_FLAG-C)") (class "Default")
      (node (ref "OVERFLOW_FLAG") (pin "K") (pinfunction "C_K") (pintype "passive"))
      (node (ref "R13") (pin "2") (pinfunction "2_2") (pintype "passive"))
    )
    (net (code "289") (name "Net-(PARAM_LED_1-C)") (class "Default")
      (node (ref "PARAM_LED_1") (pin "K") (pinfunction "C_K") (pintype "passive"))
      (node (ref "R71") (pin "1") (pinfunction "1_1") (pintype "passive"))
    )
    (net (code "290") (name "Net-(PARAM_LED_2-C)") (class "Default")
      (node (ref "PARAM_LED_2") (pin "K") (pinfunction "C_K") (pintype "passive"))
      (node (ref "R70") (pin "1") (pinfunction "1_1") (pintype "passive"))
    )
    (net (code "291") (name "Net-(PARAM_LED_3-C)") (class "Default")
      (node (ref "PARAM_LED_3") (pin "K") (pinfunction "C_K") (pintype "passive"))
      (node (ref "R69") (pin "1") (pinfunction "1_1") (pintype "passive"))
    )
    (net (code "292") (name "Net-(PARAM_LED_4-C)") (class "Default")
      (node (ref "PARAM_LED_4") (pin "K") (pinfunction "C_K") (pintype "passive"))
      (node (ref "R76") (pin "1") (pinfunction "1_1") (pintype "passive"))
    )
    (net (code "293") (name "Net-(PARAM_LED_5-C)") (class "Default")
      (node (ref "PARAM_LED_5") (pin "K") (pinfunction "C_K") (pintype "passive"))
      (node (ref "R72") (pin "1") (pinfunction "1_1") (pintype "passive"))
    )
    (net (code "294") (name "Net-(PARAM_LED_6-C)") (class "Default")
      (node (ref "PARAM_LED_6") (pin "K") (pinfunction "C_K") (pintype "passive"))
      (node (ref "R73") (pin "1") (pinfunction "1_1") (pintype "passive"))
    )
    (net (code "295") (name "Net-(PARAM_LED_7-C)") (class "Default")
      (node (ref "PARAM_LED_7") (pin "K") (pinfunction "C_K") (pintype "passive"))
      (node (ref "R74") (pin "1") (pinfunction "1_1") (pintype "passive"))
    )
    (net (code "296") (name "Net-(PARAM_LED_8-C)") (class "Default")
      (node (ref "PARAM_LED_8") (pin "K") (pinfunction "C_K") (pintype "passive"))
      (node (ref "R75") (pin "1") (pinfunction "1_1") (pintype "passive"))
    )
    (net (code "297") (name "Net-(PC_1-C)") (class "Default")
      (node (ref "PC_1") (pin "K") (pinfunction "C_K") (pintype "passive"))
      (node (ref "R16") (pin "1") (pinfunction "1_1") (pintype "passive"))
    )
    (net (code "298") (name "Net-(PC_2-C)") (class "Default")
      (node (ref "PC_2") (pin "K") (pinfunction "C_K") (pintype "passive"))
      (node (ref "R17") (pin "1") (pinfunction "1_1") (pintype "passive"))
    )
    (net (code "299") (name "Net-(PC_3-C)") (class "Default")
      (node (ref "PC_3") (pin "K") (pinfunction "C_K") (pintype "passive"))
      (node (ref "R18") (pin "1") (pinfunction "1_1") (pintype "passive"))
    )
    (net (code "300") (name "Net-(PC_4-C)") (class "Default")
      (node (ref "PC_4") (pin "K") (pinfunction "C_K") (pintype "passive"))
      (node (ref "R19") (pin "1") (pinfunction "1_1") (pintype "passive"))
    )
    (net (code "301") (name "Net-(PC_5-C)") (class "Default")
      (node (ref "PC_5") (pin "K") (pinfunction "C_K") (pintype "passive"))
      (node (ref "R20") (pin "1") (pinfunction "1_1") (pintype "passive"))
    )
    (net (code "302") (name "Net-(PC_6-C)") (class "Default")
      (node (ref "PC_6") (pin "K") (pinfunction "C_K") (pintype "passive"))
      (node (ref "R21") (pin "1") (pinfunction "1_1") (pintype "passive"))
    )
    (net (code "303") (name "Net-(PC_7-C)") (class "Default")
      (node (ref "PC_7") (pin "K") (pinfunction "C_K") (pintype "passive"))
      (node (ref "R22") (pin "1") (pinfunction "1_1") (pintype "passive"))
    )
    (net (code "304") (name "Net-(PC_8-C)") (class "Default")
      (node (ref "PC_8") (pin "K") (pinfunction "C_K") (pintype "passive"))
      (node (ref "R23") (pin "1") (pinfunction "1_1") (pintype "passive"))
    )
    (net (code "305") (name "Net-(POSITIVE_FLAG-C)") (class "Default")
      (node (ref "POSITIVE_FLAG") (pin "K") (pinfunction "C_K") (pintype "passive"))
      (node (ref "R12") (pin "2") (pinfunction "2_2") (pintype "passive"))
    )
    (net (code "306") (name "Net-(PROGRAM_COUNTER_LOWER-Pad15)") (class "Default")
      (node (ref "PROGRAM_COUNTER_LOWER") (pin "15") (pinfunction "15_15") (pintype "passive"))
      (node (ref "PROGRAM_COUNTER_UPPER") (pin "10") (pinfunction "10_10") (pintype "passive"))
    )
    (net (code "307") (name "Net-(RAM_ADDR_LOWERA-Q1)") (class "Default")
      (node (ref "RAM") (pin "10") (pinfunction "10_10") (pintype "passive"))
      (node (ref "RAM_ADDR_LOWER") (pin "3") (pinfunction "Q1_3") (pintype "tri_state"))
    )
    (net (code "308") (name "Net-(RAM_ADDR_LOWERA-Q2)") (class "Default")
      (node (ref "RAM") (pin "9") (pinfunction "9_9") (pintype "passive"))
      (node (ref "RAM_ADDR_LOWER") (pin "4") (pinfunction "Q2_4") (pintype "tri_state"))
    )
    (net (code "309") (name "Net-(RAM_ADDR_LOWERA-Q3)") (class "Default")
      (node (ref "RAM") (pin "8") (pinfunction "8_8") (pintype "passive"))
      (node (ref "RAM_ADDR_LOWER") (pin "5") (pinfunction "Q3_5") (pintype "tri_state"))
    )
    (net (code "310") (name "Net-(RAM_ADDR_LOWERA-Q4)") (class "Default")
      (node (ref "RAM") (pin "7") (pinfunction "7_7") (pintype "passive"))
      (node (ref "RAM_ADDR_LOWER") (pin "6") (pinfunction "Q4_6") (pintype "tri_state"))
    )
    (net (code "311") (name "Net-(RAM_ADDR_UPPERA-Q1)") (class "Default")
      (node (ref "RAM") (pin "6") (pinfunction "6_6") (pintype "passive"))
      (node (ref "RAM_ADDR_UPPER") (pin "3") (pinfunction "Q1_3") (pintype "tri_state"))
    )
    (net (code "312") (name "Net-(RAM_ADDR_UPPERA-Q2)") (class "Default")
      (node (ref "RAM") (pin "5") (pinfunction "5_5") (pintype "passive"))
      (node (ref "RAM_ADDR_UPPER") (pin "4") (pinfunction "Q2_4") (pintype "tri_state"))
    )
    (net (code "313") (name "Net-(RAM_ADDR_UPPERA-Q3)") (class "Default")
      (node (ref "RAM") (pin "4") (pinfunction "4_4") (pintype "passive"))
      (node (ref "RAM_ADDR_UPPER") (pin "5") (pinfunction "Q3_5") (pintype "tri_state"))
    )
    (net (code "314") (name "Net-(RAM_ADDR_UPPERA-Q4)") (class "Default")
      (node (ref "RAM") (pin "3") (pinfunction "3_3") (pintype "passive"))
      (node (ref "RAM_ADDR_UPPER") (pin "6") (pinfunction "Q4_6") (pintype "tri_state"))
    )
    (net (code "315") (name "Net-(RAM_LED_1-C)") (class "Default")
      (node (ref "R32") (pin "1") (pinfunction "1_1") (pintype "passive"))
      (node (ref "RAM_LED_1") (pin "K") (pinfunction "C_K") (pintype "passive"))
    )
    (net (code "316") (name "Net-(RAM_LED_2-C)") (class "Default")
      (node (ref "R33") (pin "1") (pinfunction "1_1") (pintype "passive"))
      (node (ref "RAM_LED_2") (pin "K") (pinfunction "C_K") (pintype "passive"))
    )
    (net (code "317") (name "Net-(RAM_LED_3-C)") (class "Default")
      (node (ref "R34") (pin "1") (pinfunction "1_1") (pintype "passive"))
      (node (ref "RAM_LED_3") (pin "K") (pinfunction "C_K") (pintype "passive"))
    )
    (net (code "318") (name "Net-(RAM_LED_4-C)") (class "Default")
      (node (ref "R35") (pin "1") (pinfunction "1_1") (pintype "passive"))
      (node (ref "RAM_LED_4") (pin "K") (pinfunction "C_K") (pintype "passive"))
    )
    (net (code "319") (name "Net-(RAM_LED_5-C)") (class "Default")
      (node (ref "R36") (pin "1") (pinfunction "1_1") (pintype "passive"))
      (node (ref "RAM_LED_5") (pin "K") (pinfunction "C_K") (pintype "passive"))
    )
    (net (code "320") (name "Net-(RAM_LED_6-C)") (class "Default")
      (node (ref "R37") (pin "1") (pinfunction "1_1") (pintype "passive"))
      (node (ref "RAM_LED_6") (pin "K") (pinfunction "C_K") (pintype "passive"))
    )
    (net (code "321") (name "Net-(RAM_LED_7-C)") (class "Default")
      (node (ref "R38") (pin "1") (pinfunction "1_1") (pintype "passive"))
      (node (ref "RAM_LED_7") (pin "K") (pinfunction "C_K") (pintype "passive"))
    )
    (net (code "322") (name "Net-(RAM_LED_8-C)") (class "Default")
      (node (ref "R39") (pin "1") (pinfunction "1_1") (pintype "passive"))
      (node (ref "RAM_LED_8") (pin "K") (pinfunction "C_K") (pintype "passive"))
    )
    (net (code "323") (name "Net-(SELECTOR_LOGIC2_A-A)") (class "Default")
      (node (ref "INSTRUCTION_MEMORY_UPPER") (pin "18") (pinfunction "18_18") (pintype "passive"))
      (node (ref "SELECTOR_LOGIC2_") (pin "2") (pinfunction "A_2") (pintype "input"))
    )
    (net (code "324") (name "Net-(SELECTOR_LOGIC2_A-B)") (class "Default")
      (node (ref "INSTRUCTION_MEMORY_UPPER") (pin "19") (pinfunction "19_19") (pintype "passive"))
      (node (ref "SELECTOR_LOGIC2_") (pin "3") (pinfunction "B_3") (pintype "input"))
    )
    (net (code "325") (name "Net-(SELECTOR_LOGIC2_B-A)") (class "Default")
      (node (ref "INSTRUCTION_MEMORY_UPPER") (pin "12") (pinfunction "12_12") (pintype "passive"))
      (node (ref "SELECTOR_LOGIC2_") (pin "14") (pinfunction "A_14") (pintype "input"))
    )
    (net (code "326") (name "Net-(SELECTOR_LOGIC2_B-B)") (class "Default")
      (node (ref "INSTRUCTION_MEMORY_UPPER") (pin "11") (pinfunction "11_11") (pintype "passive"))
      (node (ref "SELECTOR_LOGIC2_") (pin "13") (pinfunction "B_13") (pintype "input"))
    )
    (net (code "327") (name "Net-(SELECTOR_LOGIC_A-B)") (class "Default")
      (node (ref "INSTRUCTION_MEMORY_UPPER2") (pin "13") (pinfunction "13_13") (pintype "passive"))
      (node (ref "SELECTOR_LOGIC_") (pin "3") (pinfunction "B_3") (pintype "input"))
    )
    (net (code "328") (name "Net-(STEPPER_CLOCK-DIS)") (class "Default")
      (node (ref "C2") (pin "+") (pinfunction "+_+") (pintype "passive"))
      (node (ref "R3") (pin "1") (pinfunction "1_1") (pintype "passive"))
      (node (ref "STEPPER_CLOCK") (pin "6") (pinfunction "THR_6") (pintype "input"))
      (node (ref "STEPPER_CLOCK") (pin "7") (pinfunction "DIS_7") (pintype "input"))
    )
    (net (code "329") (name "Net-(USTEP_1-C)") (class "Default")
      (node (ref "R40") (pin "2") (pinfunction "2_2") (pintype "passive"))
      (node (ref "USTEP_1") (pin "K") (pinfunction "C_K") (pintype "passive"))
    )
    (net (code "330") (name "Net-(USTEP_2-C)") (class "Default")
      (node (ref "R41") (pin "2") (pinfunction "2_2") (pintype "passive"))
      (node (ref "USTEP_2") (pin "K") (pinfunction "C_K") (pintype "passive"))
    )
    (net (code "331") (name "Net-(USTEP_3-C)") (class "Default")
      (node (ref "R42") (pin "2") (pinfunction "2_2") (pintype "passive"))
      (node (ref "USTEP_3") (pin "K") (pinfunction "C_K") (pintype "passive"))
    )
    (net (code "332") (name "Net-(USTEP_4-C)") (class "Default")
      (node (ref "R43") (pin "2") (pinfunction "2_2") (pintype "passive"))
      (node (ref "USTEP_4") (pin "K") (pinfunction "C_K") (pintype "passive"))
    )
    (net (code "333") (name "Net-(USTEP_5-C)") (class "Default")
      (node (ref "R44") (pin "2") (pinfunction "2_2") (pintype "passive"))
      (node (ref "USTEP_5") (pin "K") (pinfunction "C_K") (pintype "passive"))
    )
    (net (code "334") (name "Net-(ZERO_FLAG-C)") (class "Default")
      (node (ref "R14") (pin "2") (pinfunction "2_2") (pintype "passive"))
      (node (ref "ZERO_FLAG") (pin "K") (pinfunction "C_K") (pintype "passive"))
    )
    (net (code "335") (name "VCC") (class "Default")
      (node (ref "4_INP_OR_GATE") (pin "14") (pinfunction "VDD_14") (pintype "power_in"))
      (node (ref "ADDR_REG_A_LOWER") (pin "15") (pinfunction "CLR_15") (pintype "input"))
      (node (ref "ADDR_REG_A_UPPER") (pin "15") (pinfunction "CLR_15") (pintype "input"))
      (node (ref "ADDR_REG_CALC_LOWER") (pin "15") (pinfunction "CLR_15") (pintype "input"))
      (node (ref "ADDR_REG_CALC_LOWER1") (pin "15") (pinfunction "CLR_15") (pintype "input"))
      (node (ref "ADDR_REG_CALC_UPPER") (pin "15") (pinfunction "CLR_15") (pintype "input"))
      (node (ref "ADDR_REG_PARAM_UPPER") (pin "15") (pinfunction "CLR_15") (pintype "input"))
      (node (ref "AUTO_CLOCK") (pin "4") (pinfunction "R_4") (pintype "input"))
      (node (ref "AUTO_CLOCK") (pin "8") (pinfunction "V+_8") (pintype "power_in"))
      (node (ref "C3") (pin "+") (pinfunction "+_+") (pintype "passive"))
      (node (ref "CLK_MODE") (pin "2") (pinfunction "2_2") (pintype "passive"))
      (node (ref "EXTENTION") (pin "10") (pinfunction "1_10") (pintype "passive"))
      (node (ref "INSTRUCTIONS_EXTENSION") (pin "14") (pinfunction "1_14") (pintype "passive"))
      (node (ref "INSTRUCTION_MEMORY_LOWER") (pin "27") (pinfunction "27_27") (pintype "passive"))
      (node (ref "INSTRUCTION_MEMORY_LOWER") (pin "28") (pinfunction "28_28") (pintype "passive"))
      (node (ref "INSTRUCTION_MEMORY_UPPER") (pin "27") (pinfunction "27_27") (pintype "passive"))
      (node (ref "INSTRUCTION_MEMORY_UPPER") (pin "28") (pinfunction "28_28") (pintype "passive"))
      (node (ref "INSTRUCTION_MEMORY_UPPER2") (pin "27") (pinfunction "27_27") (pintype "passive"))
      (node (ref "INSTRUCTION_MEMORY_UPPER2") (pin "28") (pinfunction "28_28") (pintype "passive"))
      (node (ref "INSTRUC_REGISTER_LOWER") (pin "15") (pinfunction "CLR_15") (pintype "input"))
      (node (ref "INSTRUC_REGISTER_UPPER") (pin "15") (pinfunction "CLR_15") (pintype "input"))
      (node (ref "KILL_SWITCH") (pin "1") (pinfunction "1_1") (pintype "passive"))
      (node (ref "MEMORY") (pin "27") (pinfunction "27_27") (pintype "passive"))
      (node (ref "MEMORY") (pin "28") (pinfunction "28_28") (pintype "passive"))
      (node (ref "MICRO_COUNTER_LOWER") (pin "10") (pinfunction "10_10") (pintype "passive"))
      (node (ref "MICRO_COUNTER_LOWER") (pin "16") (pinfunction "16_16") (pintype "passive"))
      (node (ref "MICRO_COUNTER_LOWER") (pin "7") (pinfunction "7_7") (pintype "passive"))
      (node (ref "MICRO_COUNTER_UPPER") (pin "16") (pinfunction "16_16") (pintype "passive"))
      (node (ref "MICRO_COUNTER_UPPER") (pin "7") (pinfunction "7_7") (pintype "passive"))
      (node (ref "OUTPUT_BUFFER_CALC_REG") (pin "1") (pinfunction "DIR_1") (pintype "input"))
      (node (ref "OUTPUT_BUFFER_INSTRUCTION") (pin "1") (pinfunction "DIR_1") (pintype "input"))
      (node (ref "OUTPUT_BUFFER_LOGIC") (pin "1") (pinfunction "DIR_1") (pintype "input"))
      (node (ref "OUTPUT_BUFFER_MEMORY") (pin "1") (pinfunction "DIR_1") (pintype "input"))
      (node (ref "OUTPUT_BUFFER_PARAM_REG") (pin "1") (pinfunction "DIR_1") (pintype "input"))
      (node (ref "OUTPUT_BUFFER_PC") (pin "1") (pinfunction "DIR_1") (pintype "input"))
      (node (ref "OUTPUT_BUFFER_REG_A") (pin "1") (pinfunction "DIR_1") (pintype "input"))
      (node (ref "PROGRAM_COUNTER_LOWER") (pin "16") (pinfunction "16_16") (pintype "passive"))
      (node (ref "PROGRAM_COUNTER_LOWER") (pin "7") (pinfunction "7_7") (pintype "passive"))
      (node (ref "PROGRAM_COUNTER_UPPER") (pin "16") (pinfunction "16_16") (pintype "passive"))
      (node (ref "PROGRAM_COUNTER_UPPER") (pin "7") (pinfunction "7_7") (pintype "passive"))
      (node (ref "R1") (pin "1") (pinfunction "1_1") (pintype "passive"))
      (node (ref "R2") (pin "1") (pinfunction "1_1") (pintype "passive"))
      (node (ref "R3") (pin "2") (pinfunction "2_2") (pintype "passive"))
      (node (ref "RAM") (pin "28") (pinfunction "28_28") (pintype "passive"))
      (node (ref "STEPPER_CLOCK") (pin "8") (pinfunction "V+_8") (pintype "power_in"))
      (node (ref "X1") (pin "2") (pinfunction "1_2") (pintype "passive"))
      (node (ref "ZERO_POS_FLAG_IDENTIFIER") (pin "14") (pinfunction "+UB_14") (pintype "power_in"))
    )
    (net (code "336") (name "unconnected-(AUTO_CLOCK-CV-Pad5)") (class "Default")
      (node (ref "AUTO_CLOCK") (pin "5") (pinfunction "CV_5") (pintype "input"))
    )
    (net (code "337") (name "unconnected-(BRANCH_SELECTORB-Y0-Pad12)") (class "Default")
      (node (ref "BRANCH_SELECTOR") (pin "12") (pinfunction "Y0_12") (pintype "output"))
    )
    (net (code "338") (name "unconnected-(CLK_TRIGGER-P1-Pad4)") (class "Default")
      (node (ref "CLK_TRIGGER") (pin "4") (pinfunction "P1_4") (pintype "passive"))
    )
    (net (code "339") (name "unconnected-(FREQUENCY-PadA)") (class "Default")
      (node (ref "FREQUENCY") (pin "A") (pinfunction "A_A") (pintype "passive"))
    )
    (net (code "340") (name "unconnected-(INSTRUCTION_MEMORY_LOWER-Pad1)") (class "Default")
      (node (ref "INSTRUCTION_MEMORY_LOWER") (pin "1") (pinfunction "1_1") (pintype "passive"))
    )
    (net (code "341") (name "unconnected-(INSTRUCTION_MEMORY_LOWER-Pad26)") (class "Default")
      (node (ref "INSTRUCTION_MEMORY_LOWER") (pin "26") (pinfunction "26_26") (pintype "passive"))
    )
    (net (code "342") (name "unconnected-(INSTRUCTION_MEMORY_UPPER-Pad1)") (class "Default")
      (node (ref "INSTRUCTION_MEMORY_UPPER") (pin "1") (pinfunction "1_1") (pintype "passive"))
    )
    (net (code "343") (name "unconnected-(INSTRUCTION_MEMORY_UPPER-Pad26)") (class "Default")
      (node (ref "INSTRUCTION_MEMORY_UPPER") (pin "26") (pinfunction "26_26") (pintype "passive"))
    )
    (net (code "344") (name "unconnected-(INSTRUCTION_MEMORY_UPPER2-Pad1)") (class "Default")
      (node (ref "INSTRUCTION_MEMORY_UPPER2") (pin "1") (pinfunction "1_1") (pintype "passive"))
    )
    (net (code "345") (name "unconnected-(INSTRUCTION_MEMORY_UPPER2-Pad26)") (class "Default")
      (node (ref "INSTRUCTION_MEMORY_UPPER2") (pin "26") (pinfunction "26_26") (pintype "passive"))
    )
    (net (code "346") (name "unconnected-(MEMORY-Pad1)") (class "Default")
      (node (ref "MEMORY") (pin "1") (pinfunction "1_1") (pintype "passive"))
    )
    (net (code "347") (name "unconnected-(MEMORY-Pad26)") (class "Default")
      (node (ref "MEMORY") (pin "26") (pinfunction "26_26") (pintype "passive"))
    )
    (net (code "348") (name "unconnected-(MICRO_COUNTER_UPPER-Pad4)") (class "Default")
      (node (ref "MICRO_COUNTER_UPPER") (pin "4") (pinfunction "4_4") (pintype "passive"))
    )
    (net (code "349") (name "unconnected-(MICRO_COUNTER_UPPER-Pad5)") (class "Default")
      (node (ref "MICRO_COUNTER_UPPER") (pin "5") (pinfunction "5_5") (pintype "passive"))
    )
    (net (code "350") (name "unconnected-(MICRO_COUNTER_UPPER-Pad6)") (class "Default")
      (node (ref "MICRO_COUNTER_UPPER") (pin "6") (pinfunction "6_6") (pintype "passive"))
    )
    (net (code "351") (name "unconnected-(MICRO_COUNTER_UPPER-Pad11)") (class "Default")
      (node (ref "MICRO_COUNTER_UPPER") (pin "11") (pinfunction "11_11") (pintype "passive"))
    )
    (net (code "352") (name "unconnected-(MICRO_COUNTER_UPPER-Pad12)") (class "Default")
      (node (ref "MICRO_COUNTER_UPPER") (pin "12") (pinfunction "12_12") (pintype "passive"))
    )
    (net (code "353") (name "unconnected-(MICRO_COUNTER_UPPER-Pad13)") (class "Default")
      (node (ref "MICRO_COUNTER_UPPER") (pin "13") (pinfunction "13_13") (pintype "passive"))
    )
    (net (code "354") (name "unconnected-(MICRO_COUNTER_UPPER-Pad15)") (class "Default")
      (node (ref "MICRO_COUNTER_UPPER") (pin "15") (pinfunction "15_15") (pintype "passive"))
    )
    (net (code "355") (name "unconnected-(PROGRAM_COUNTER_UPPER-Pad15)") (class "Default")
      (node (ref "PROGRAM_COUNTER_UPPER") (pin "15") (pinfunction "15_15") (pintype "passive"))
    )
    (net (code "356") (name "unconnected-(SELECTOR_LOGIC2_A-Y0-Pad4)") (class "Default")
      (node (ref "SELECTOR_LOGIC2_") (pin "4") (pinfunction "Y0_4") (pintype "output"))
    )
    (net (code "357") (name "unconnected-(SELECTOR_LOGIC2_B-Y0-Pad12)") (class "Default")
      (node (ref "SELECTOR_LOGIC2_") (pin "12") (pinfunction "Y0_12") (pintype "output"))
    )
    (net (code "358") (name "unconnected-(SELECTOR_LOGIC_B-Y0-Pad12)") (class "Default")
      (node (ref "SELECTOR_LOGIC_") (pin "12") (pinfunction "Y0_12") (pintype "output"))
    )
    (net (code "359") (name "unconnected-(STEPPER_CLOCK-CV-Pad5)") (class "Default")
      (node (ref "STEPPER_CLOCK") (pin "5") (pinfunction "CV_5") (pintype "input"))
    )
    (net (code "360") (name "unconnected-(STEPPER_CLOCK-R-Pad4)") (class "Default")
      (node (ref "STEPPER_CLOCK") (pin "4") (pinfunction "R_4") (pintype "input"))
    )
    (net (code "361") (name "unconnected-(X1C-1-Pad3)") (class "Default")
      (node (ref "X1") (pin "3") (pinfunction "1_3") (pintype "passive"))
    )
  )
)
